# Hackerboat_Control_Board.net
KiCad netlist of a schematic drawn in EAGLE
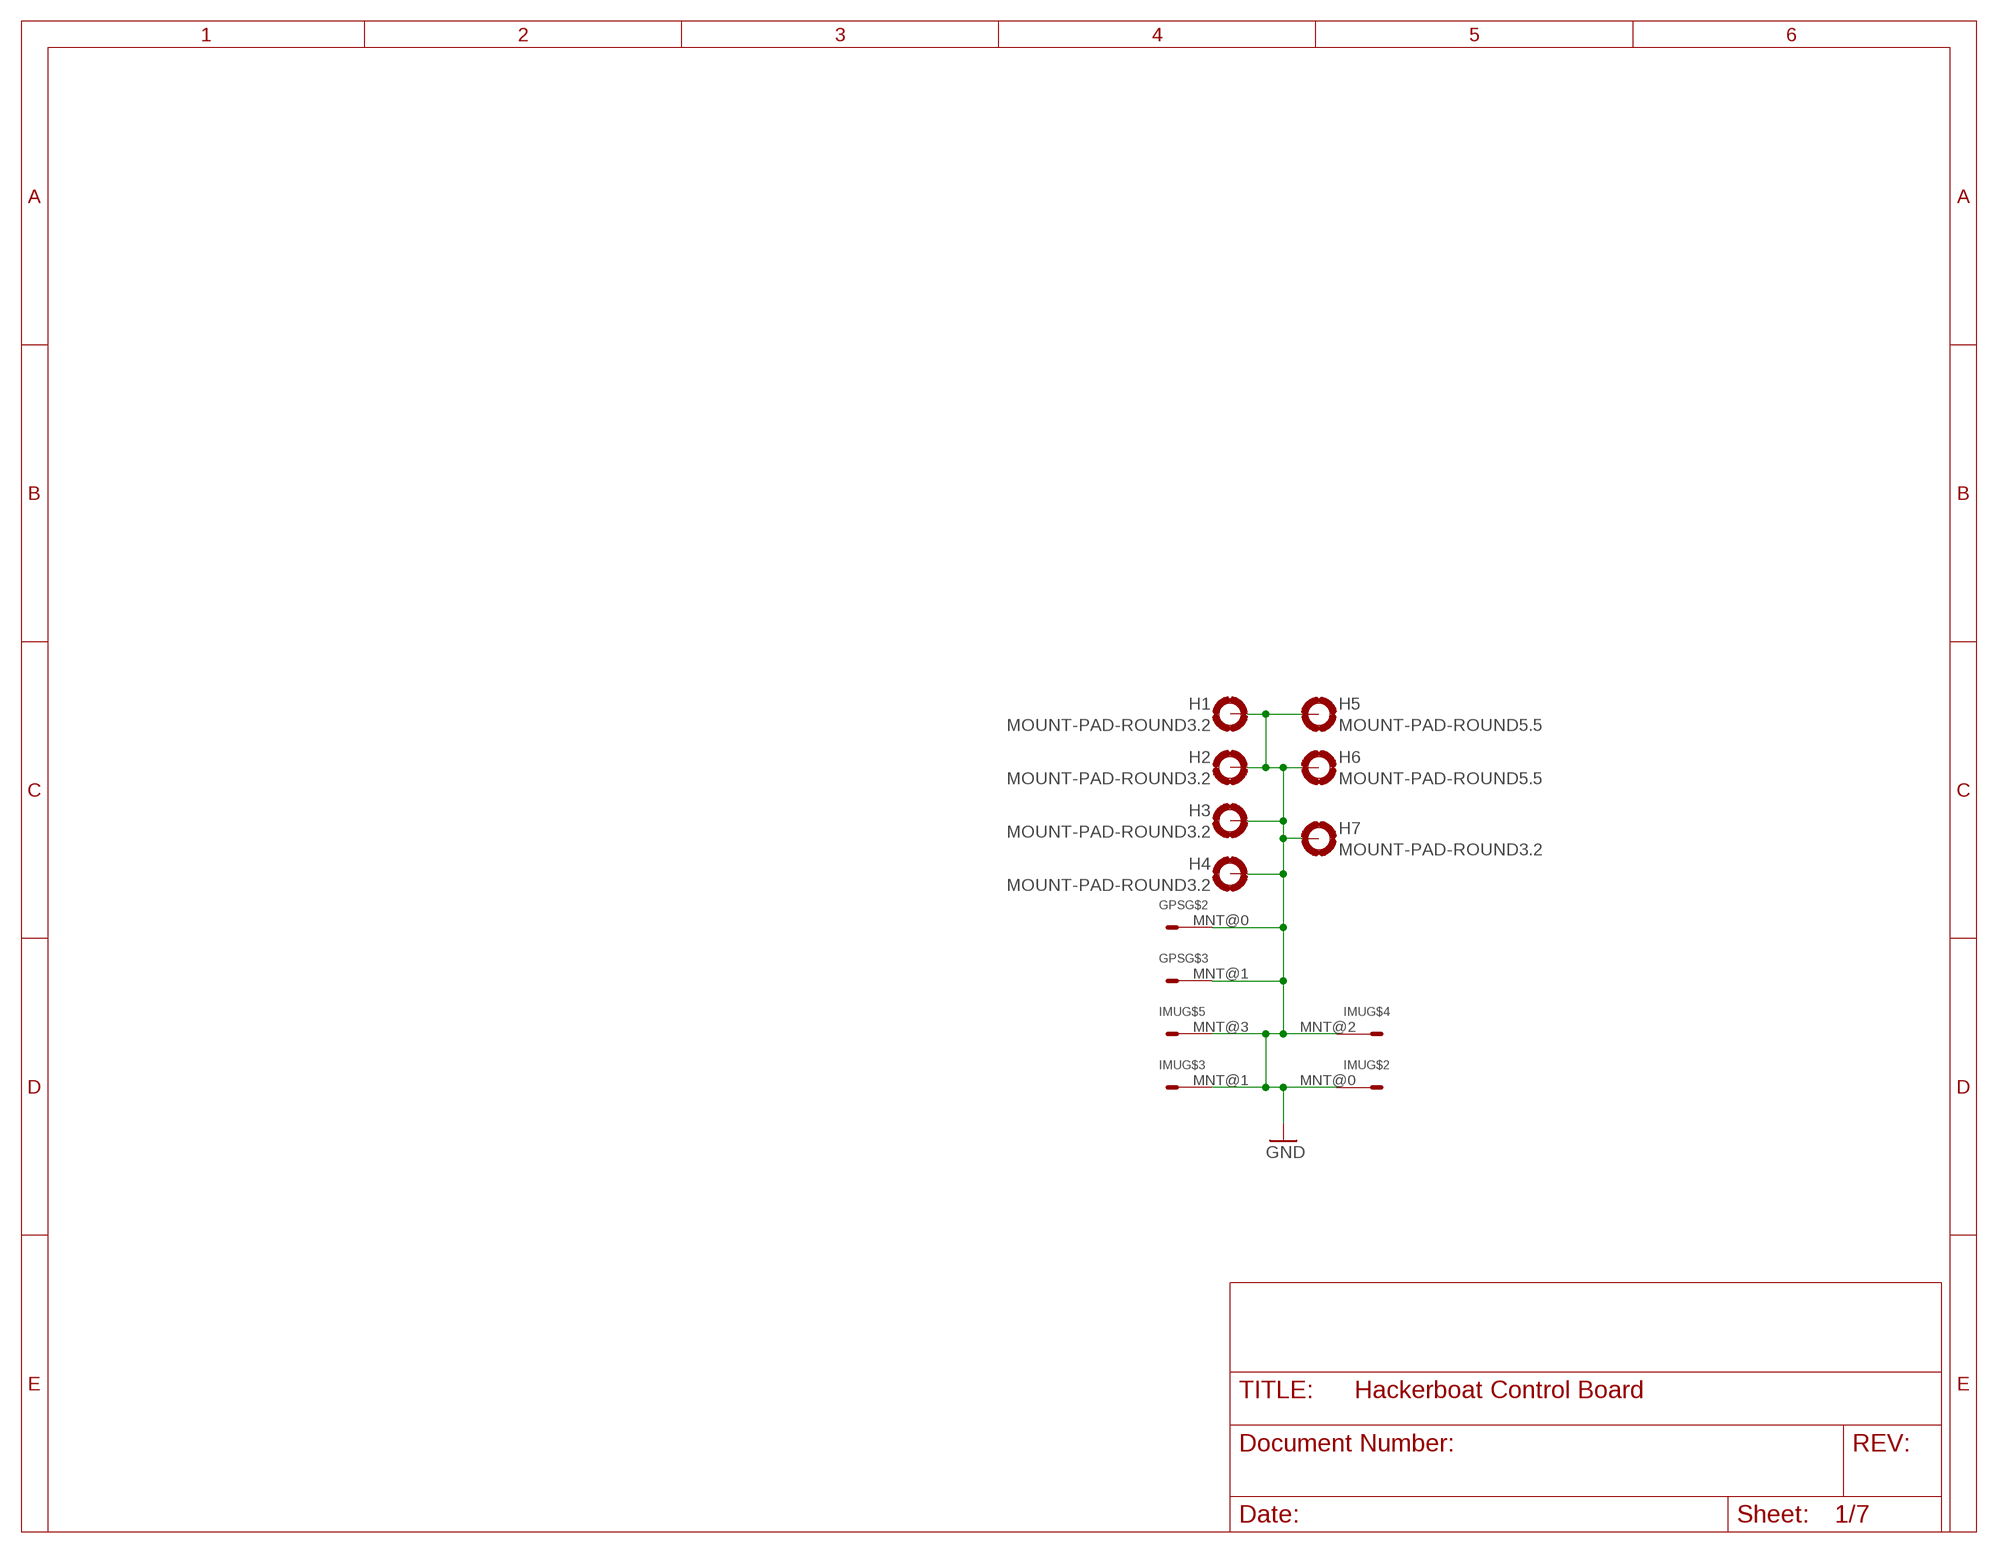
[diagram p0: schematic, sheet 1]
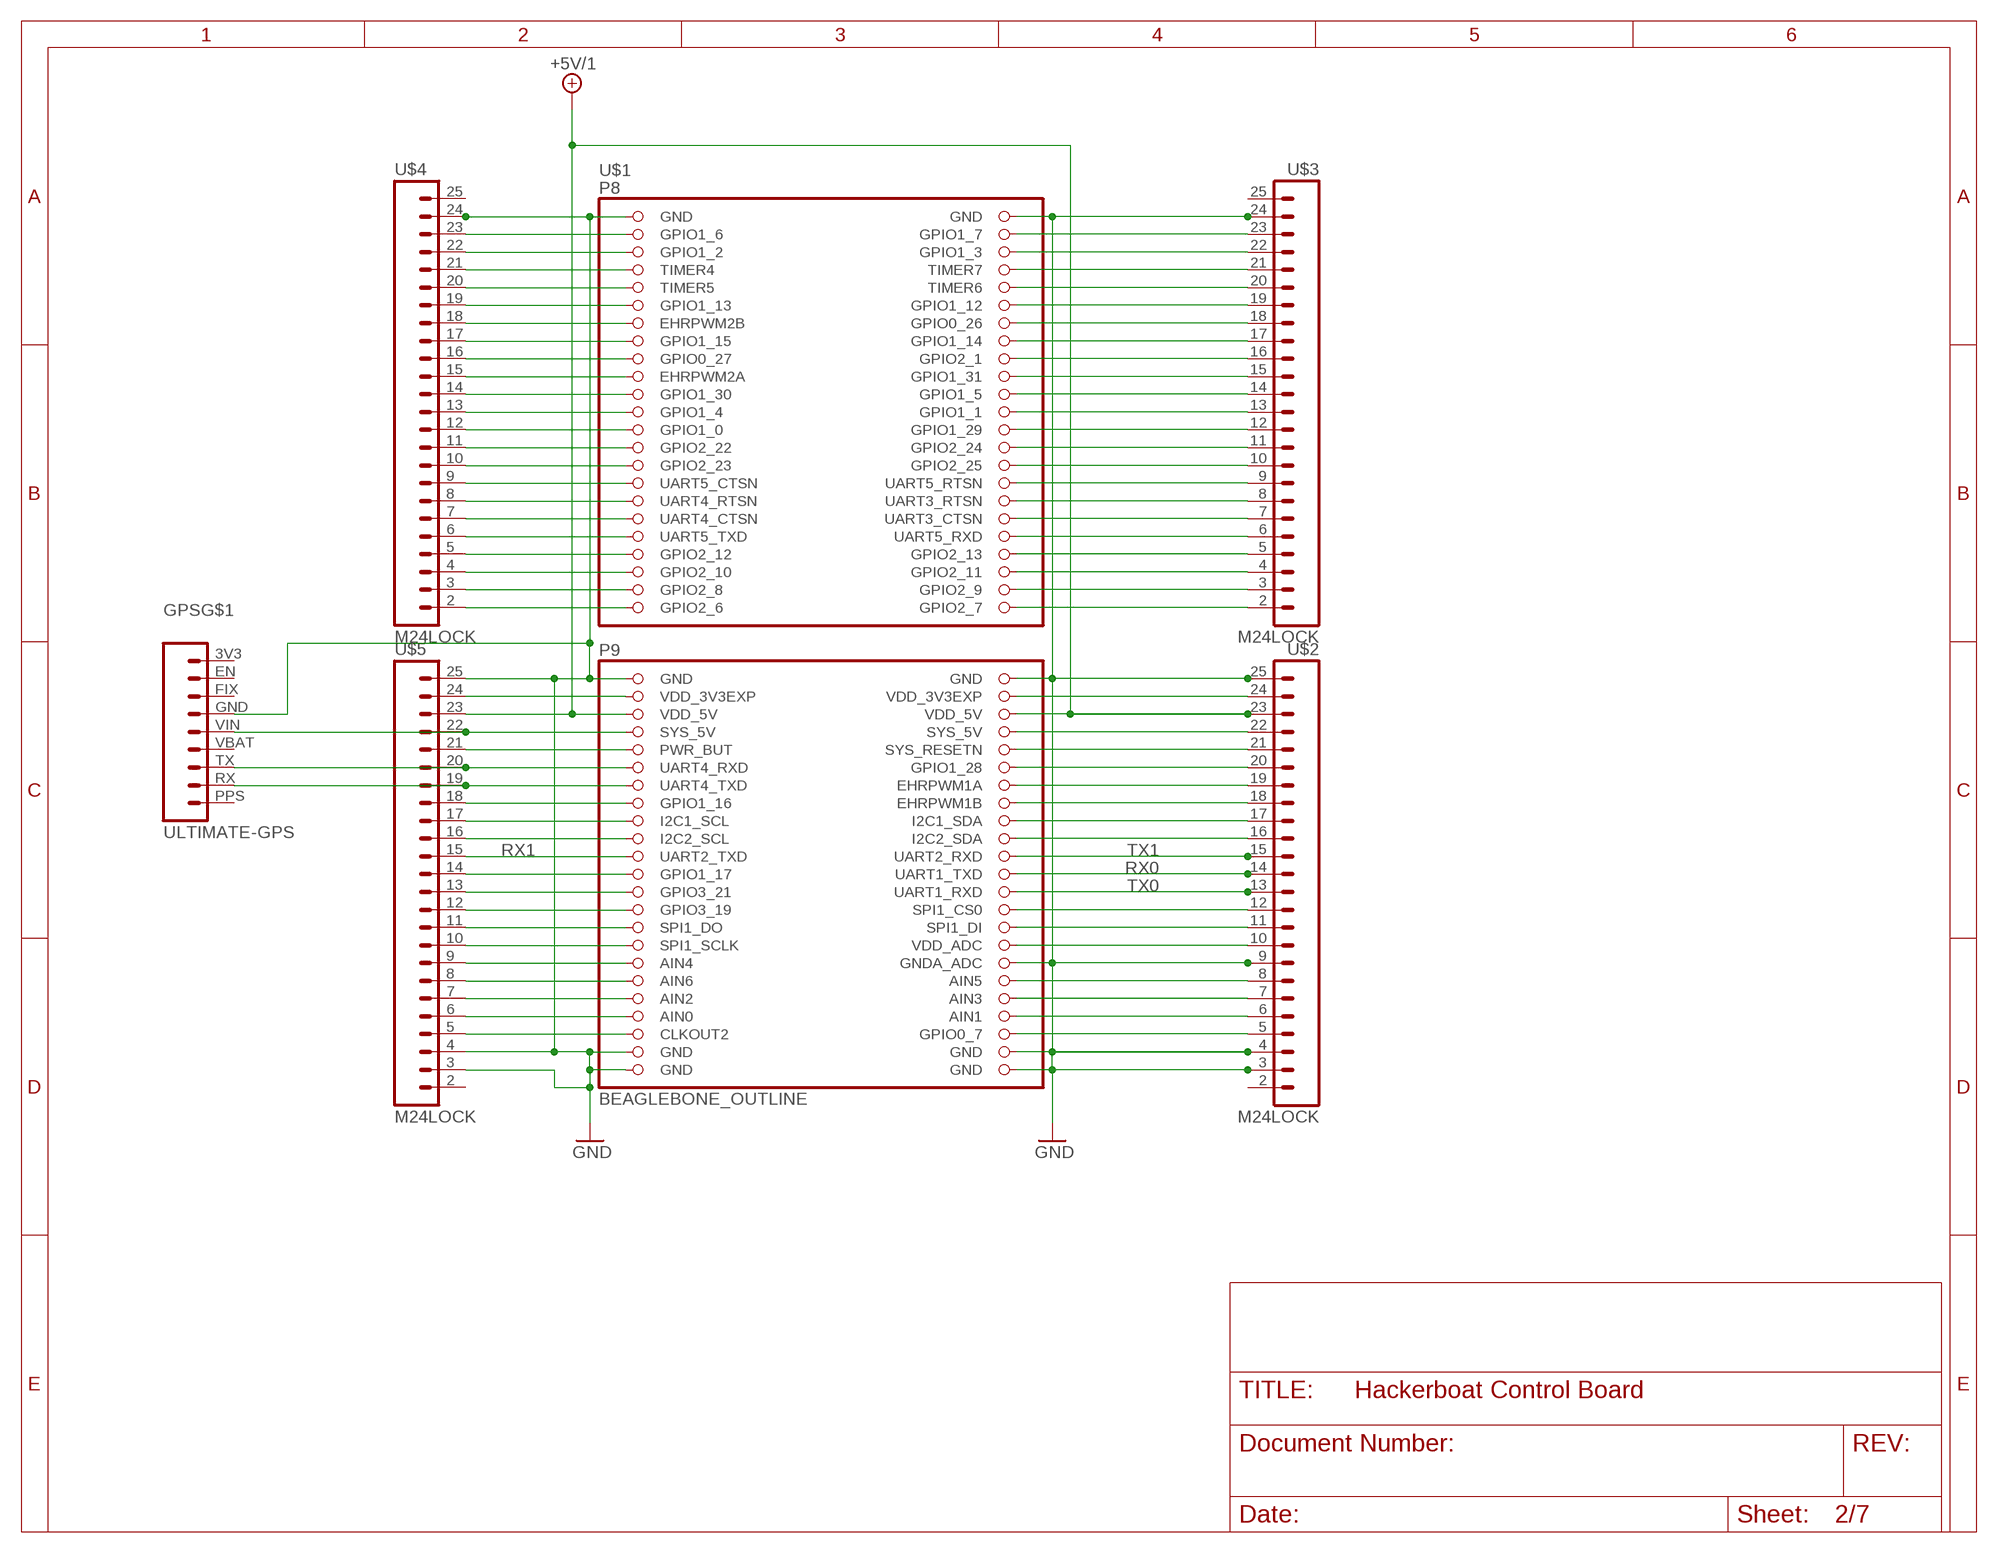
[diagram p1: schematic, sheet 2]
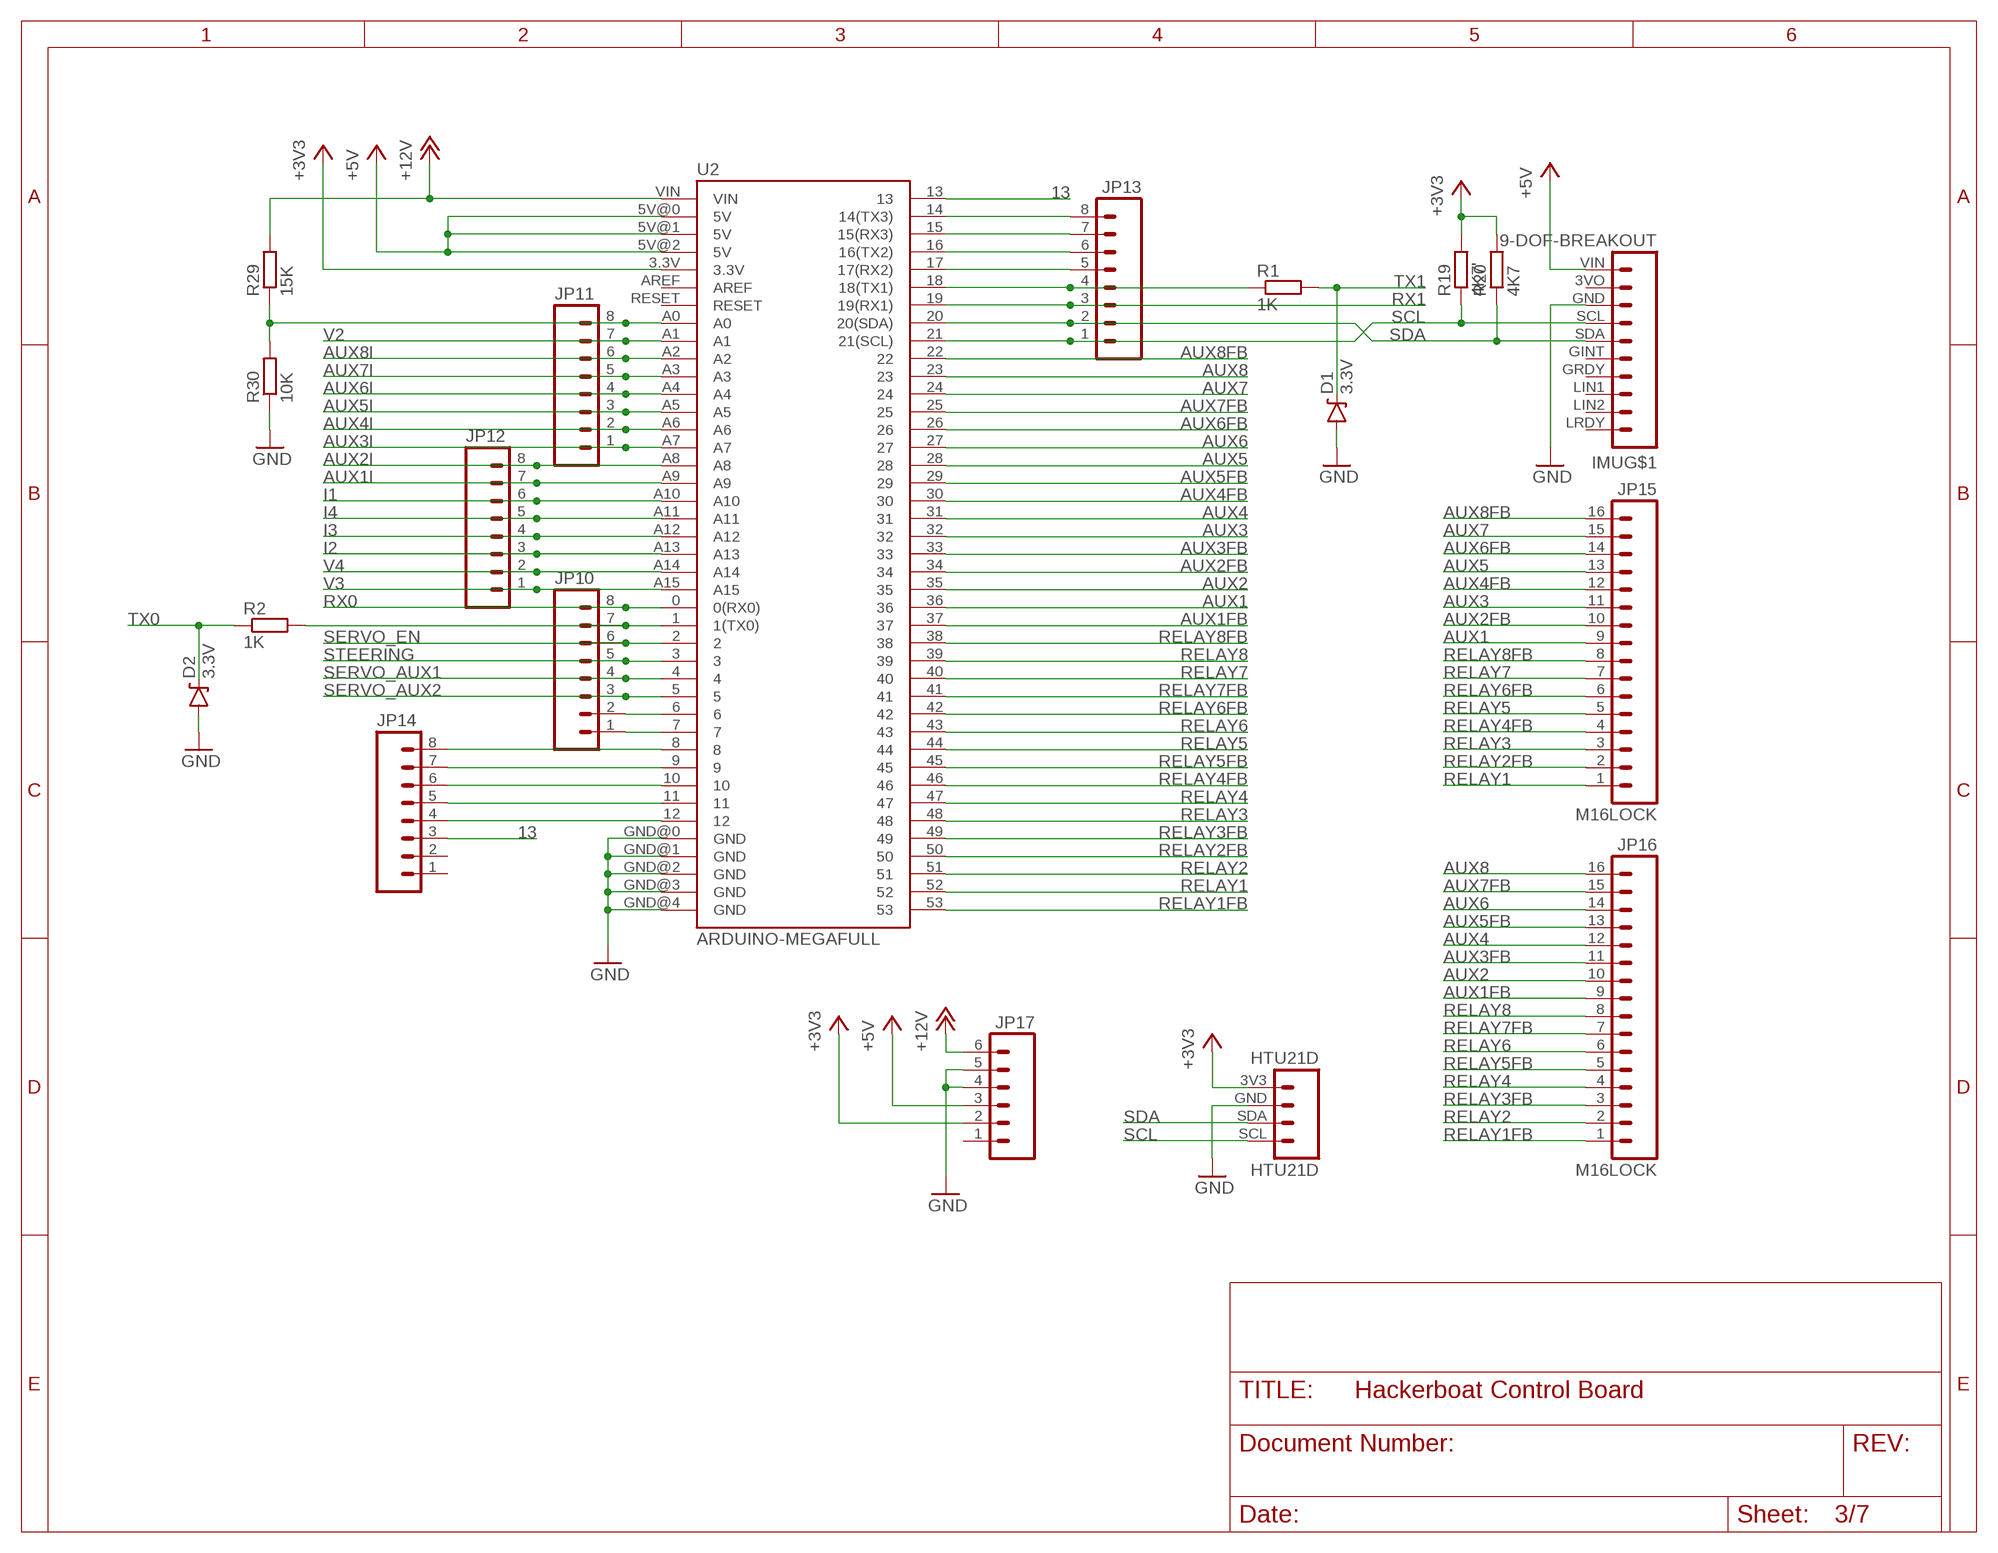
[diagram p2: schematic, sheet 3]
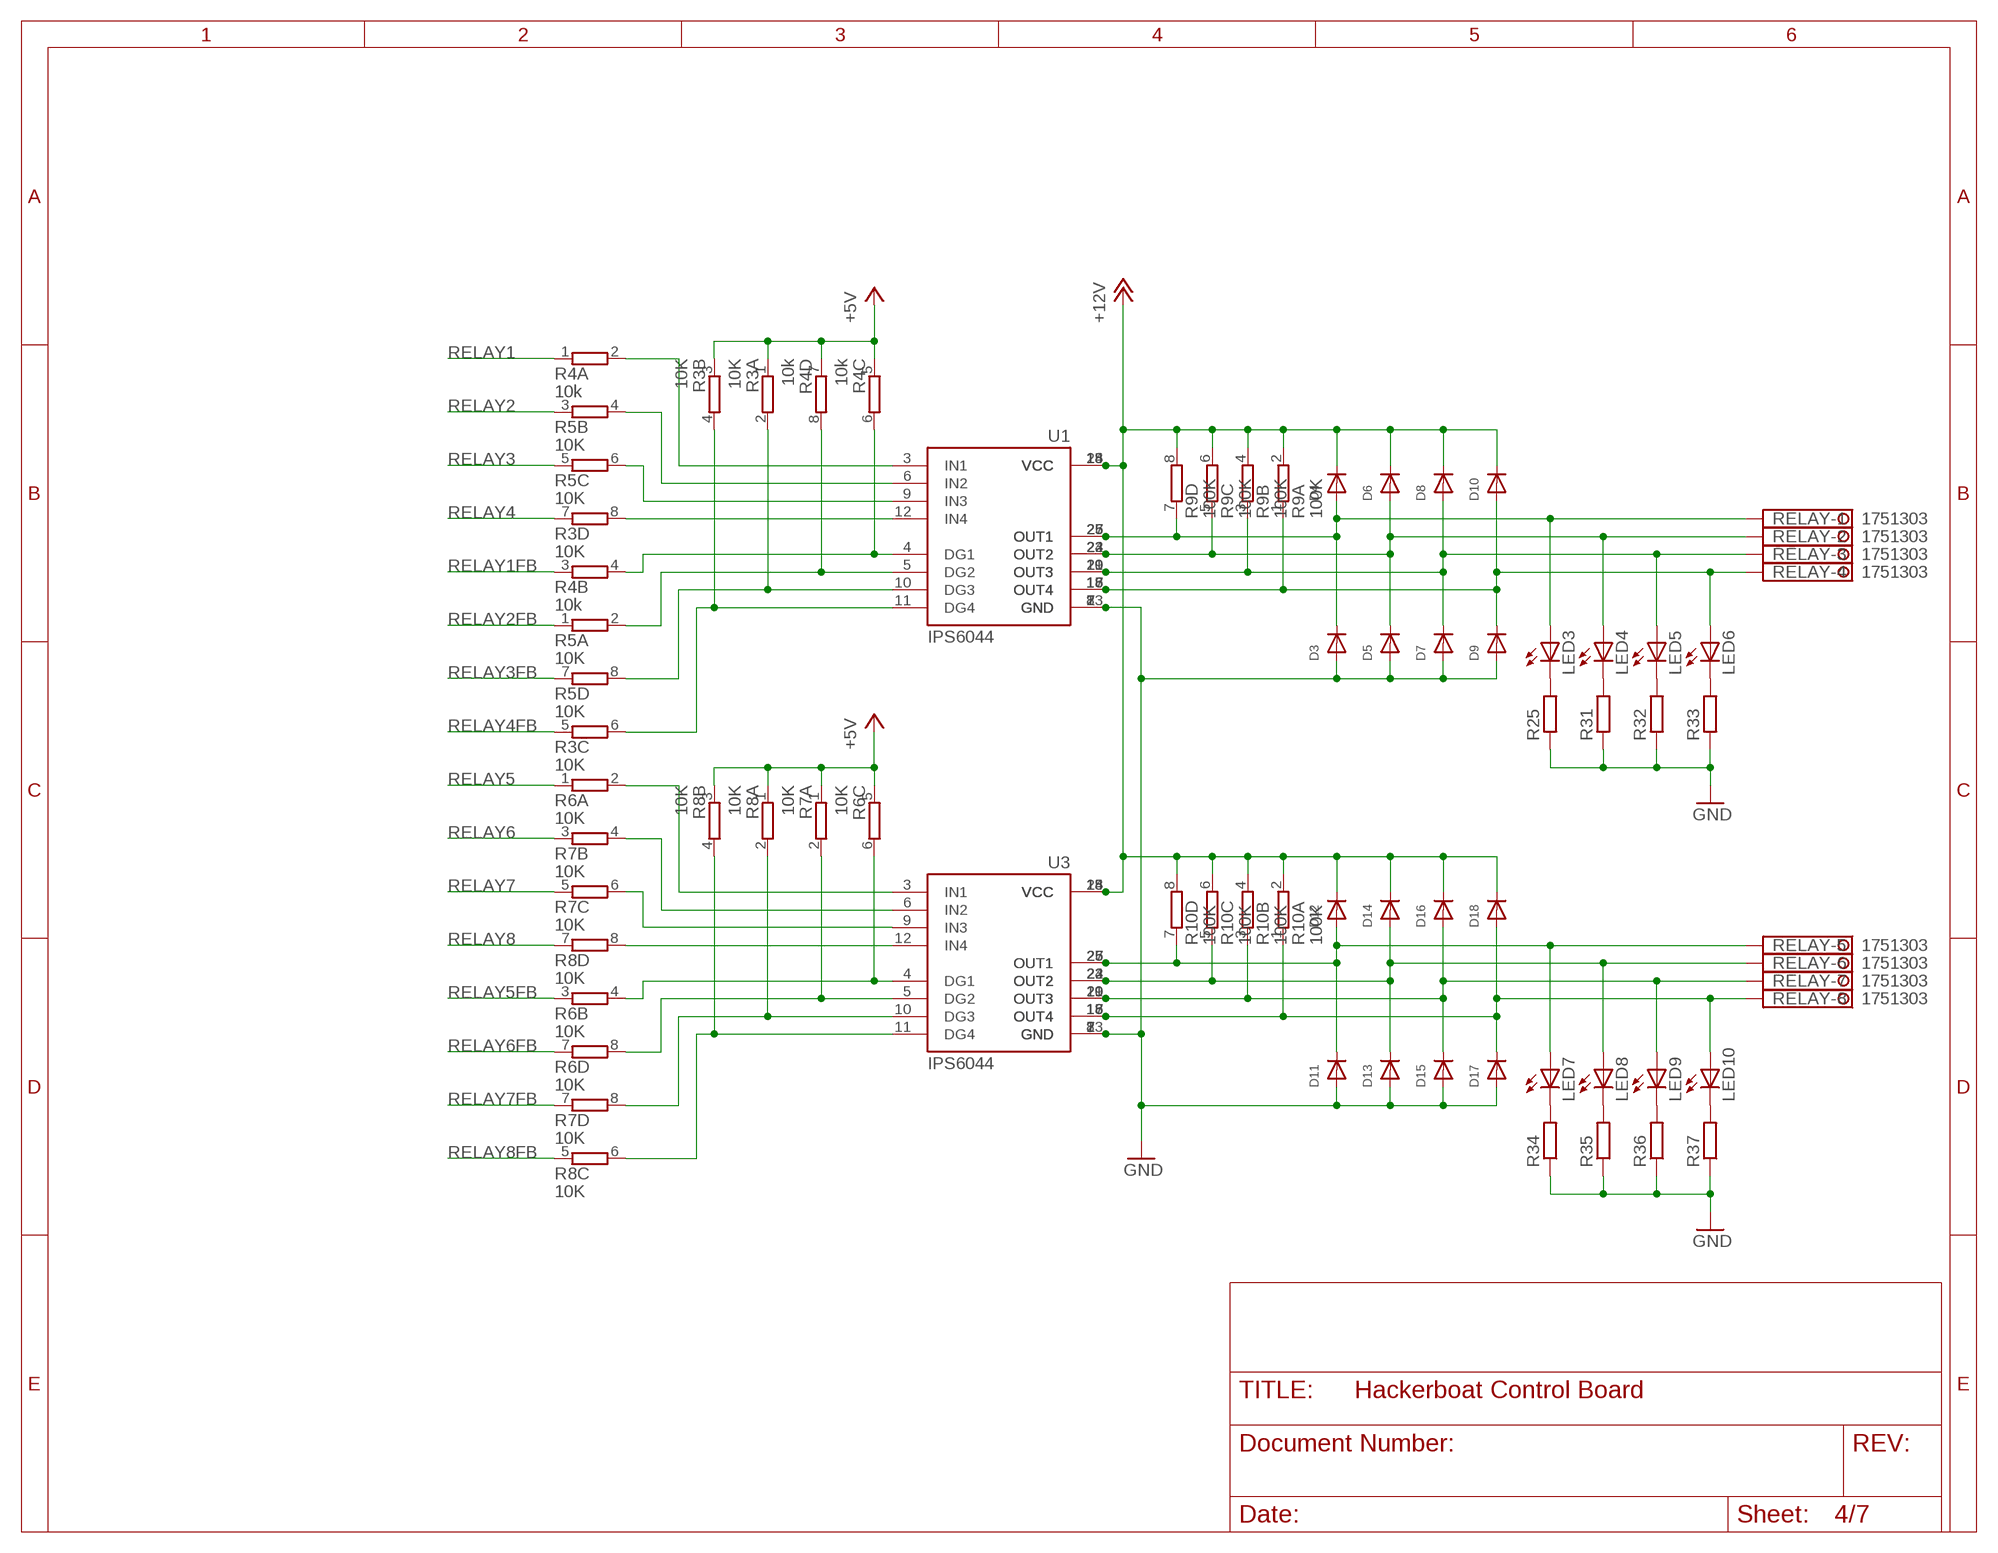
[diagram p3: schematic, sheet 4]
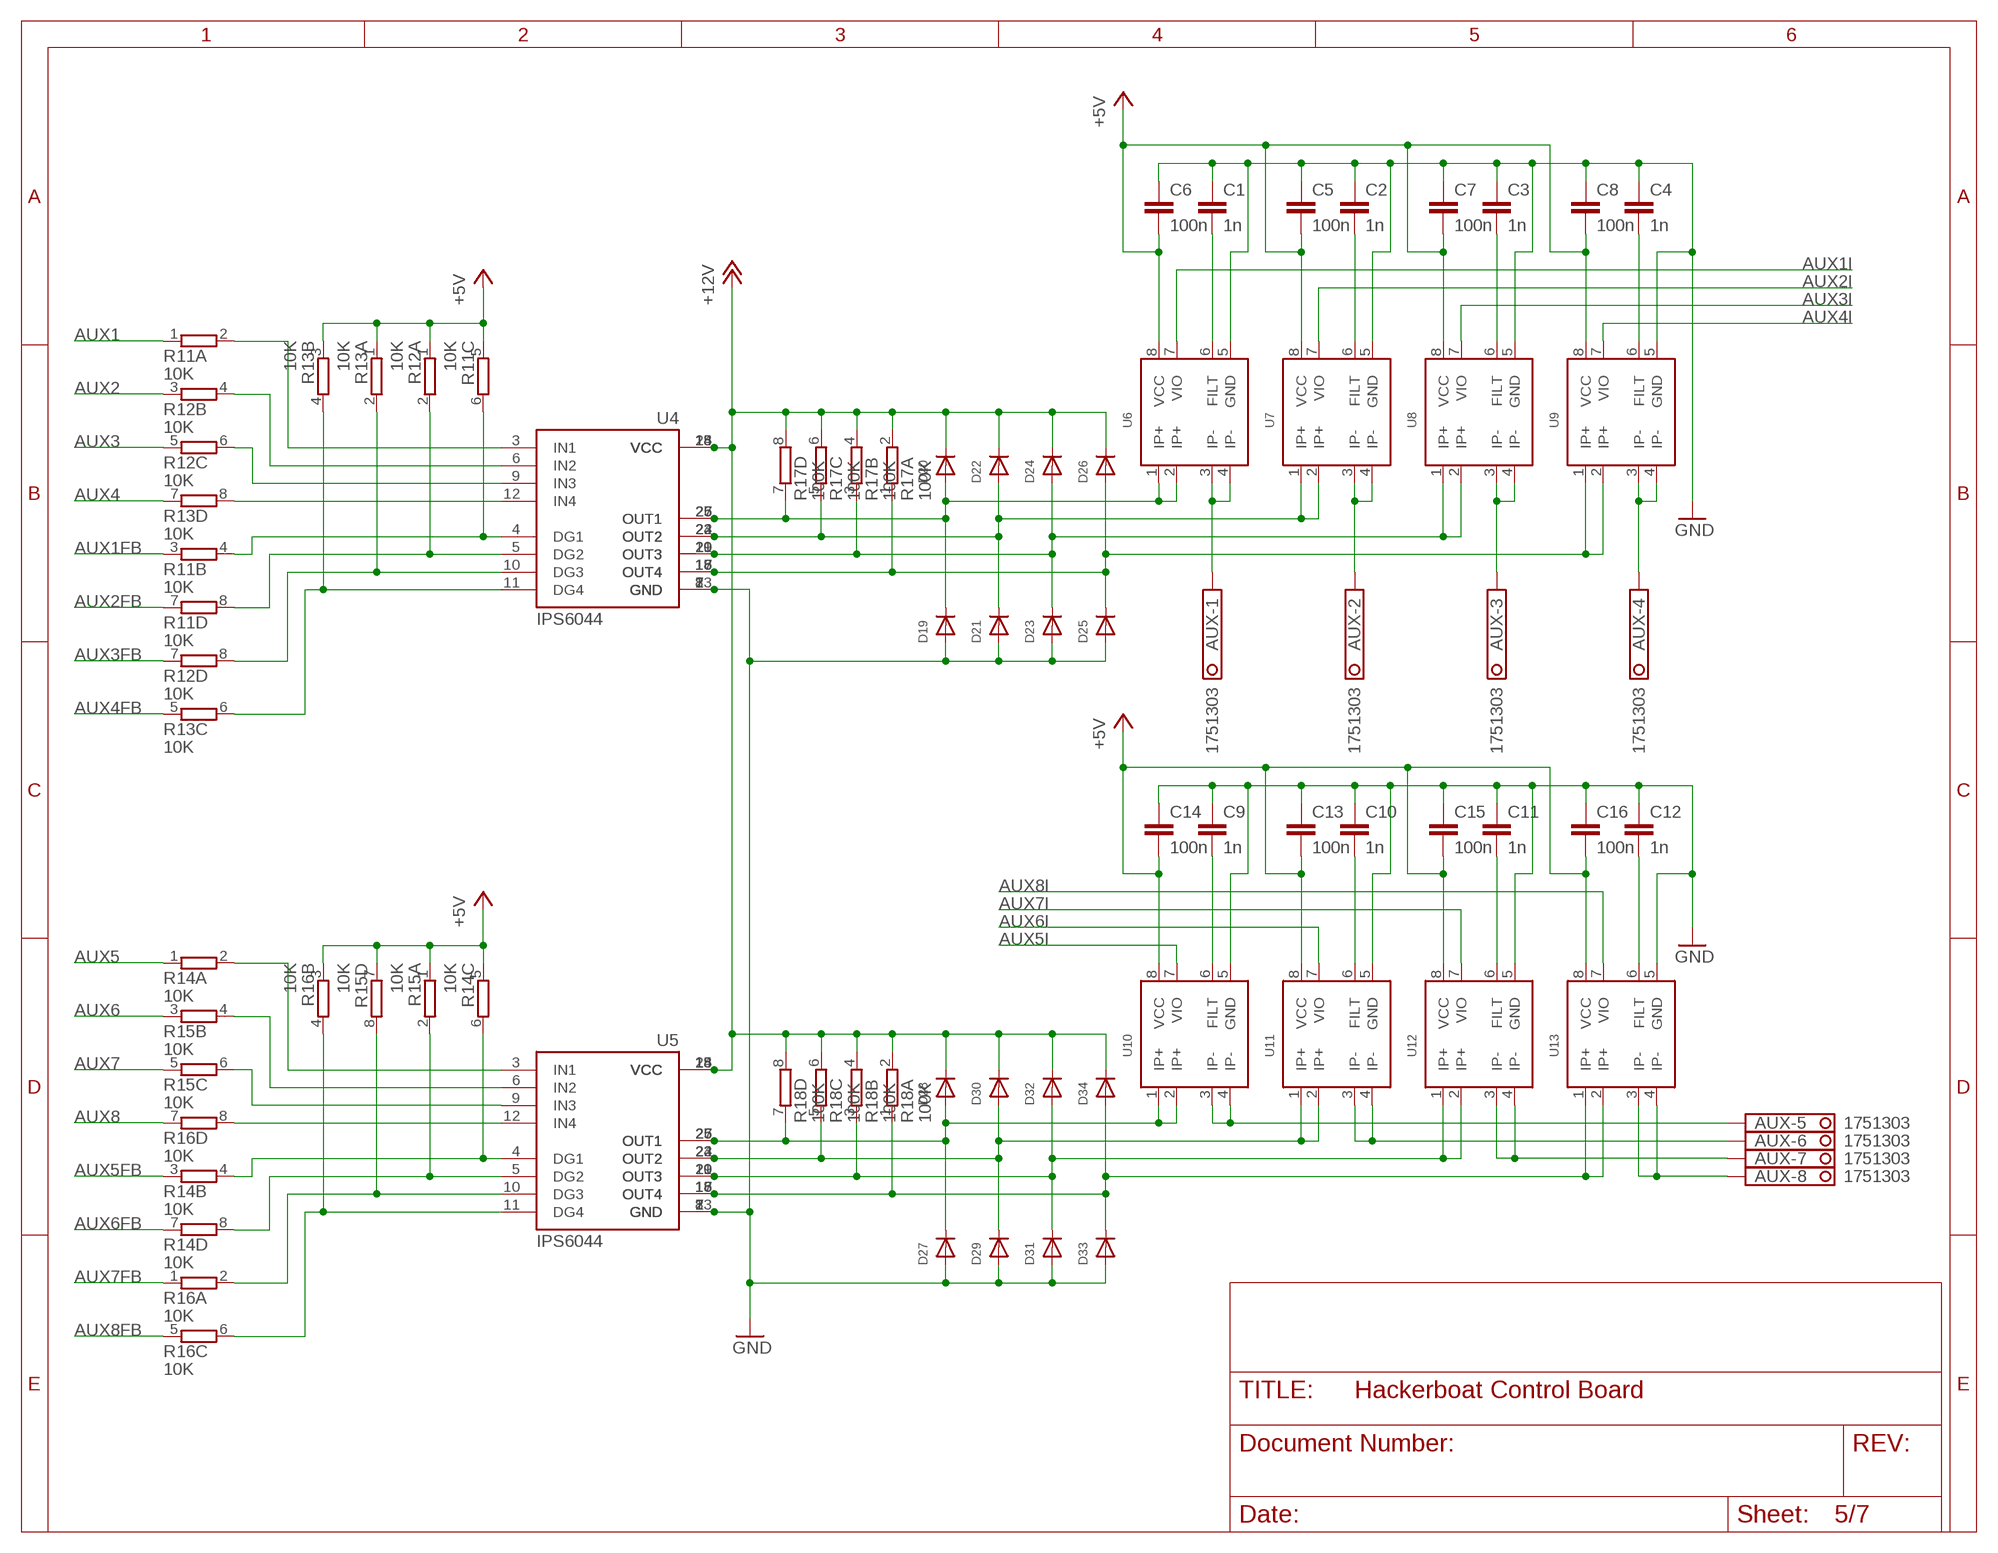
[diagram p4: schematic, sheet 5]
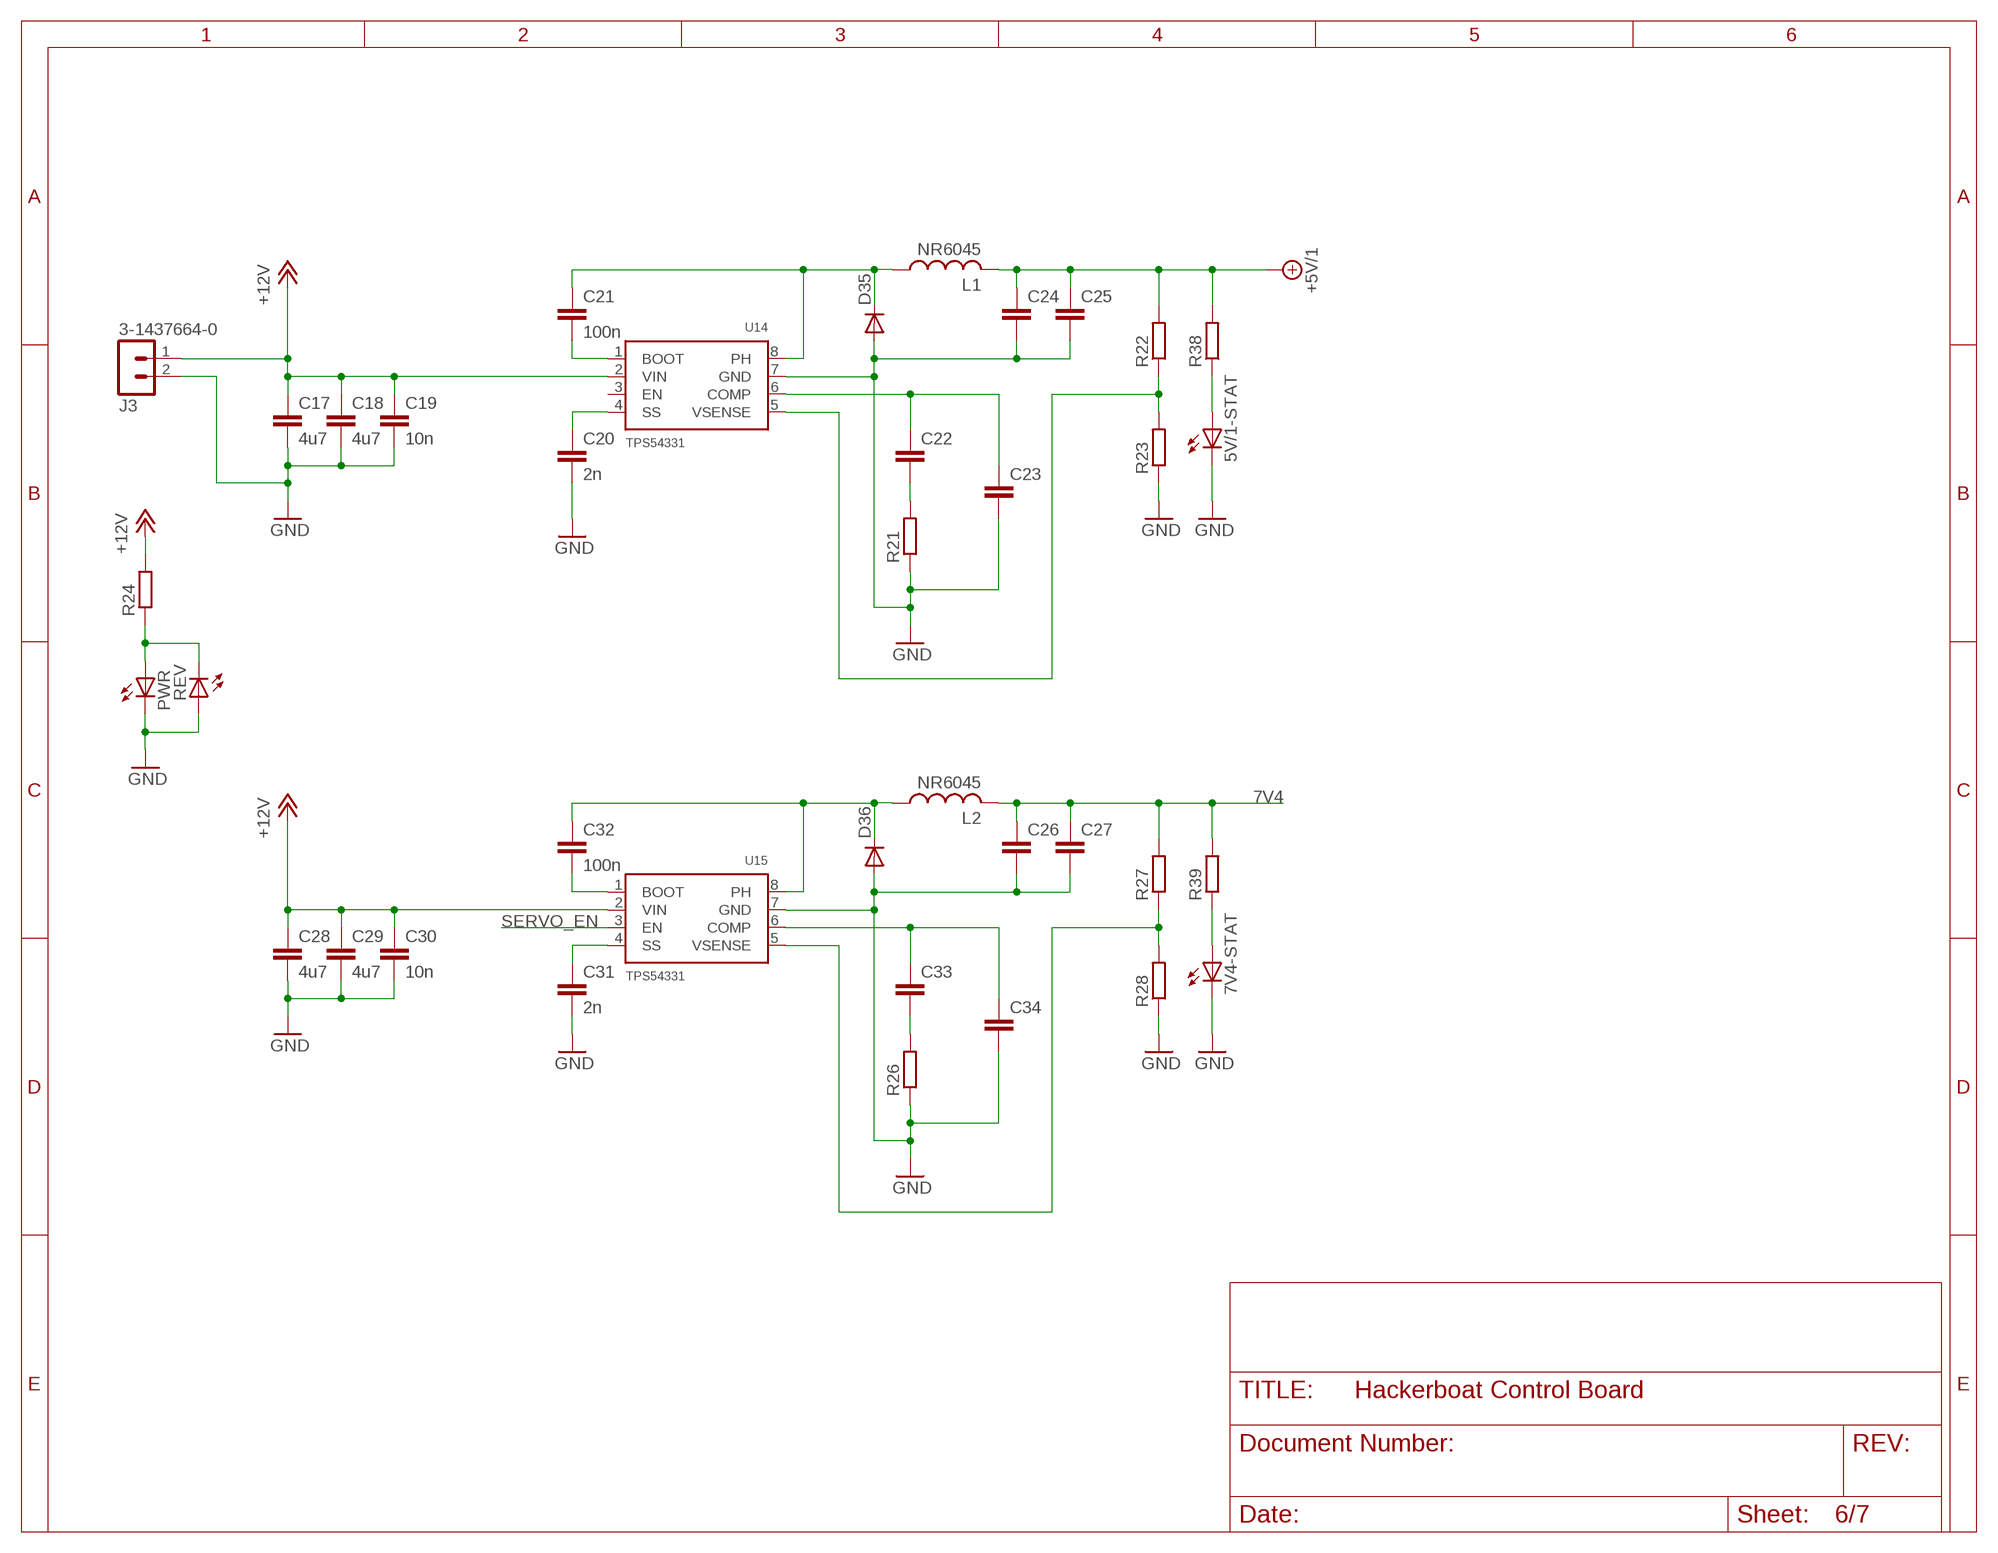
[diagram p5: schematic, sheet 6]
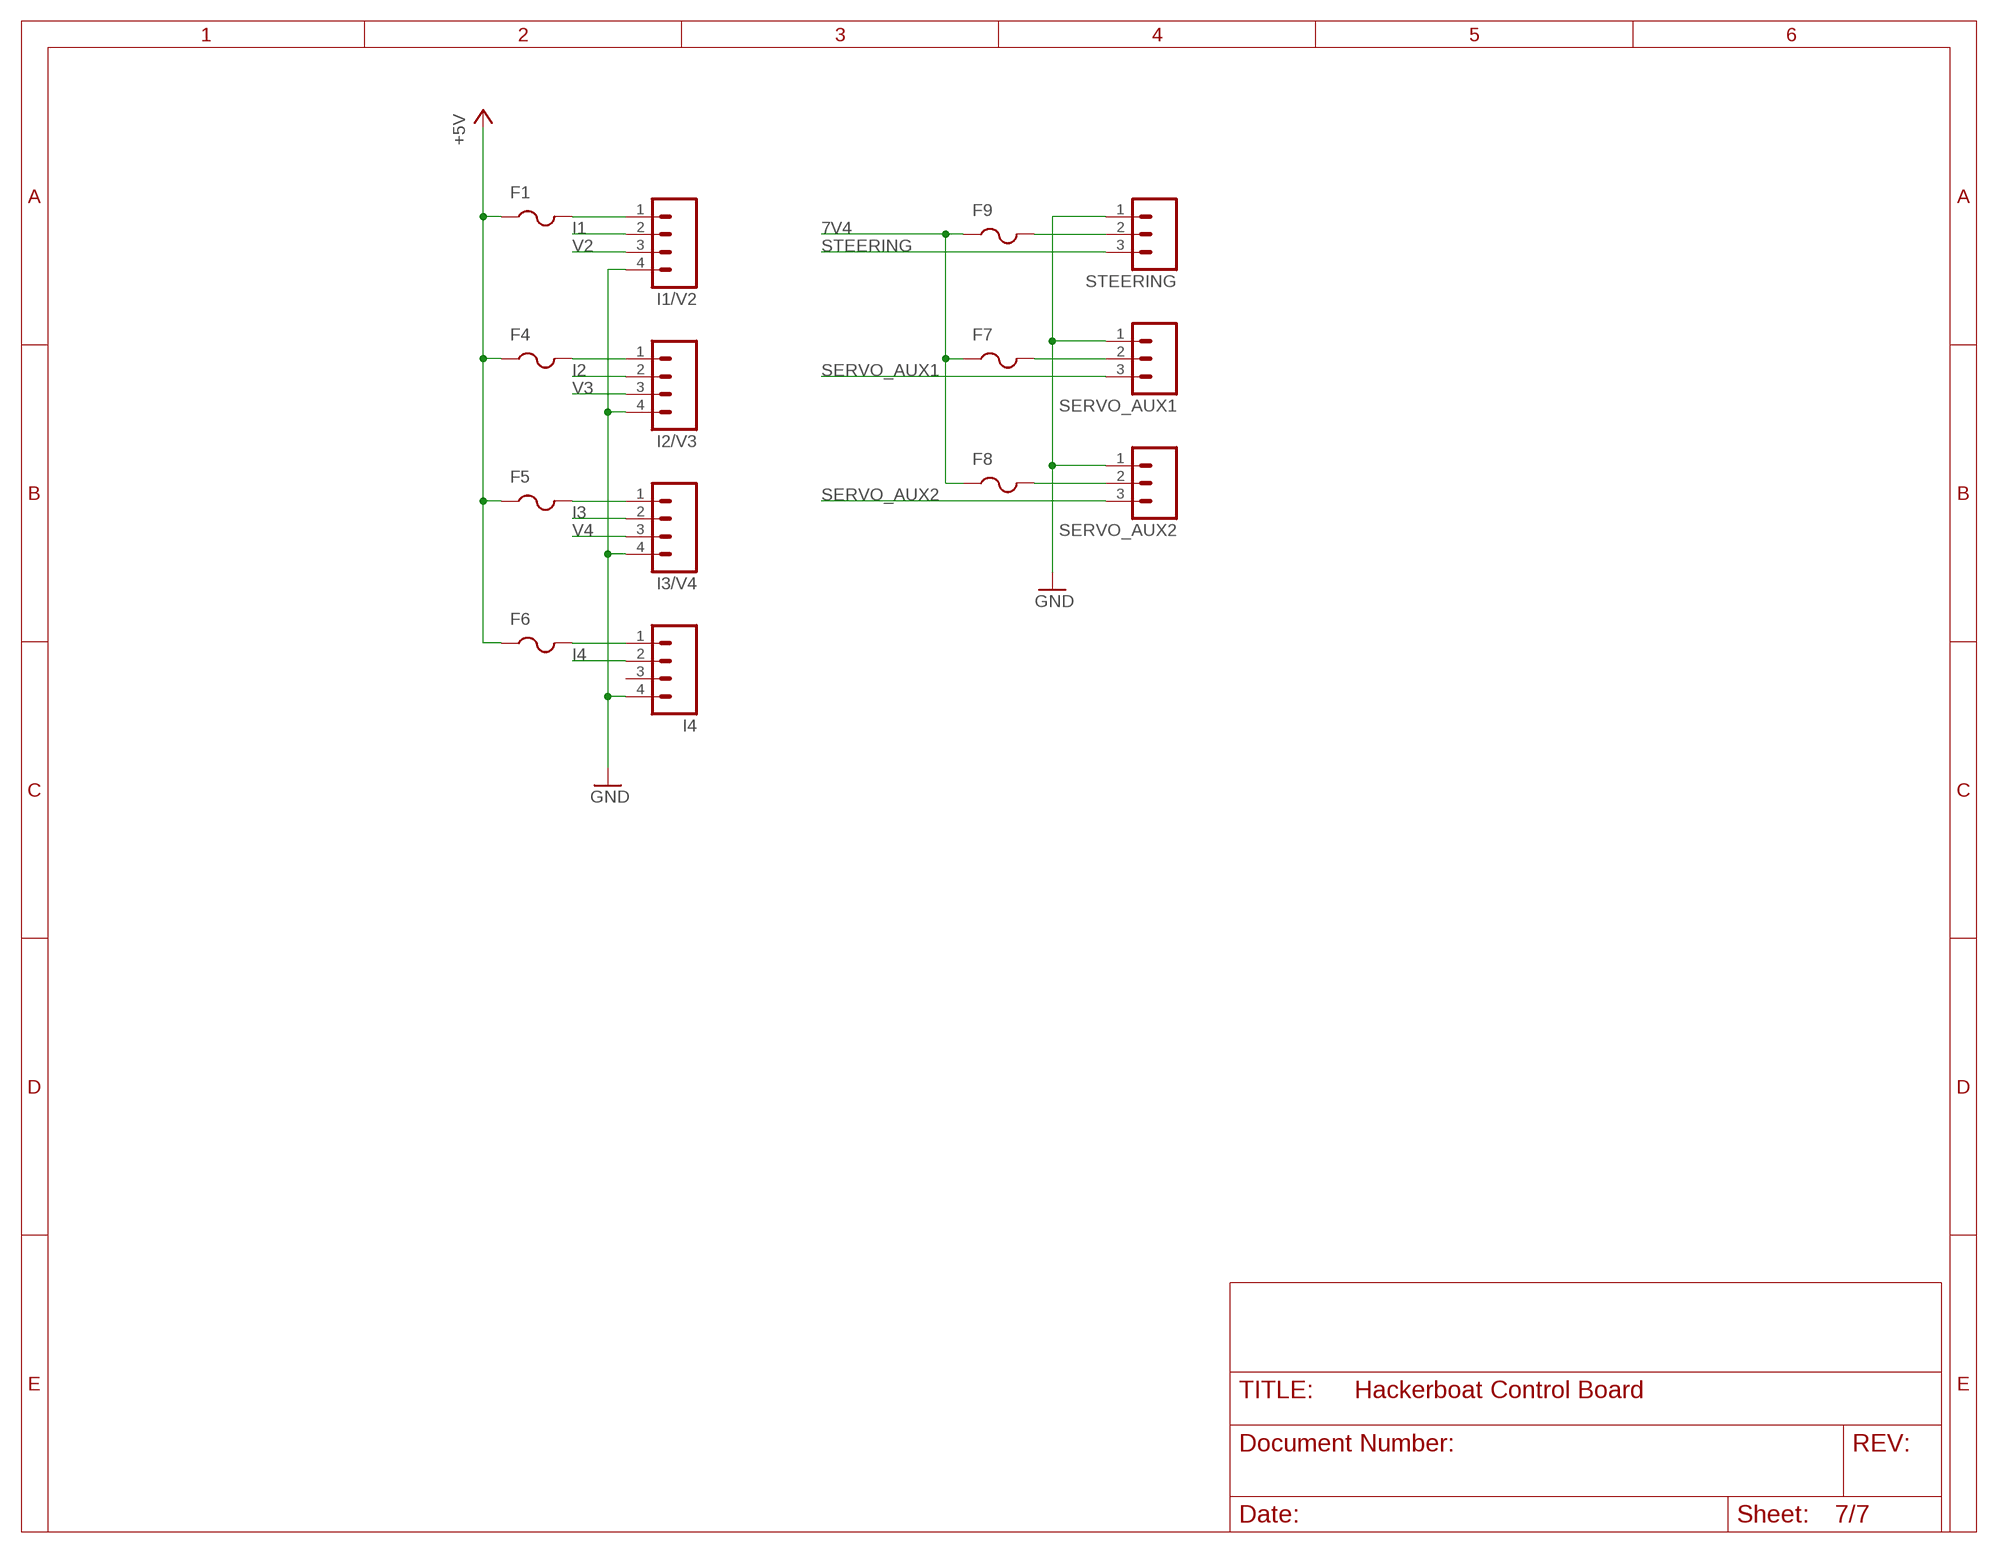
[diagram p6: schematic, sheet 7]

(export (version "E")
  (design (tool "Eeschema 10.0.6"))
  (components
    (comp (ref "F1")
      (value "PTCFUSE-1206")
      (footprint "eagle-import:R1206")
      (libsource (lib "eagle-import") (part "PTCFUSE-1206"))
    )
    (comp (ref "F4")
      (value "PTCFUSE-1206")
      (footprint "eagle-import:R1206")
      (libsource (lib "eagle-import") (part "PTCFUSE-1206"))
    )
    (comp (ref "F5")
      (value "PTCFUSE-1206")
      (footprint "eagle-import:R1206")
      (libsource (lib "eagle-import") (part "PTCFUSE-1206"))
    )
    (comp (ref "F6")
      (value "PTCFUSE-1206")
      (footprint "eagle-import:R1206")
      (libsource (lib "eagle-import") (part "PTCFUSE-1206"))
    )
    (comp (ref "F7")
      (value "PTCFUSE-1206")
      (footprint "eagle-import:R1206")
      (libsource (lib "eagle-import") (part "PTCFUSE-1206"))
    )
    (comp (ref "F8")
      (value "PTCFUSE-1206")
      (footprint "eagle-import:R1206")
      (libsource (lib "eagle-import") (part "PTCFUSE-1206"))
    )
    (comp (ref "F9")
      (value "PTCFUSE-1206")
      (footprint "eagle-import:R1206")
      (libsource (lib "eagle-import") (part "PTCFUSE-1206"))
    )
    (comp (ref "I1/V2")
      (value "M04LOCK_LONGPADS")
      (footprint "eagle-import:1X04_LOCK_LONGPADS")
      (libsource (lib "eagle-import") (part "M04LOCK_LONGPADS"))
    )
    (comp (ref "I2/V3")
      (value "M04LOCK_LONGPADS")
      (footprint "eagle-import:1X04_LOCK_LONGPADS")
      (libsource (lib "eagle-import") (part "M04LOCK_LONGPADS"))
    )
    (comp (ref "I3/V4")
      (value "M04LOCK_LONGPADS")
      (footprint "eagle-import:1X04_LOCK_LONGPADS")
      (libsource (lib "eagle-import") (part "M04LOCK_LONGPADS"))
    )
    (comp (ref "I4")
      (value "M04LOCK_LONGPADS")
      (footprint "eagle-import:1X04_LOCK_LONGPADS")
      (libsource (lib "eagle-import") (part "M04LOCK_LONGPADS"))
    )
    (comp (ref "SERVO_AUX1")
      (value "M03LOCK_LONGPADS")
      (footprint "eagle-import:1X03_LOCK_LONGPADS")
      (libsource (lib "eagle-import") (part "M03LOCK_LONGPADS"))
    )
    (comp (ref "SERVO_AUX2")
      (value "M03LOCK_LONGPADS")
      (footprint "eagle-import:1X03_LOCK_LONGPADS")
      (libsource (lib "eagle-import") (part "M03LOCK_LONGPADS"))
    )
    (comp (ref "STEERING")
      (value "M03LOCK_LONGPADS")
      (footprint "eagle-import:1X03_LOCK_LONGPADS")
      (libsource (lib "eagle-import") (part "M03LOCK_LONGPADS"))
    )
    (comp (ref "5V/1-STAT")
      (value "LEDCHIPLED_0805")
      (footprint "eagle-import:CHIPLED_0805")
      (libsource (lib "eagle-import") (part "LEDCHIPLED_0805"))
    )
    (comp (ref "7V4-STAT")
      (value "LEDCHIPLED_0805")
      (footprint "eagle-import:CHIPLED_0805")
      (libsource (lib "eagle-import") (part "LEDCHIPLED_0805"))
    )
    (comp (ref "C17")
      (value "4u7")
      (footprint "eagle-import:C1210")
      (libsource (lib "eagle-import") (part "C-EUC1210"))
    )
    (comp (ref "C18")
      (value "4u7")
      (footprint "eagle-import:C1210")
      (libsource (lib "eagle-import") (part "C-EUC1210"))
    )
    (comp (ref "C19")
      (value "10n")
      (footprint "eagle-import:C0603")
      (libsource (lib "eagle-import") (part "C-EUC0603"))
    )
    (comp (ref "C20")
      (value "2n")
      (footprint "eagle-import:C0603")
      (libsource (lib "eagle-import") (part "C-EUC0603"))
    )
    (comp (ref "C21")
      (value "100n")
      (footprint "eagle-import:C0603")
      (libsource (lib "eagle-import") (part "C-EUC0603"))
    )
    (comp (ref "C22")
      (value "C-EUC0603")
      (footprint "eagle-import:C0603")
      (libsource (lib "eagle-import") (part "C-EUC0603"))
    )
    (comp (ref "C23")
      (value "C-EUC0603")
      (footprint "eagle-import:C0603")
      (libsource (lib "eagle-import") (part "C-EUC0603"))
    )
    (comp (ref "C24")
      (value "C-EUC1210")
      (footprint "eagle-import:C1210")
      (libsource (lib "eagle-import") (part "C-EUC1210"))
    )
    (comp (ref "C25")
      (value "C-EUC1210")
      (footprint "eagle-import:C1210")
      (libsource (lib "eagle-import") (part "C-EUC1210"))
    )
    (comp (ref "C26")
      (value "C-EUC1210")
      (footprint "eagle-import:C1210")
      (libsource (lib "eagle-import") (part "C-EUC1210"))
    )
    (comp (ref "C27")
      (value "C-EUC1210")
      (footprint "eagle-import:C1210")
      (libsource (lib "eagle-import") (part "C-EUC1210"))
    )
    (comp (ref "C28")
      (value "4u7")
      (footprint "eagle-import:C1210")
      (libsource (lib "eagle-import") (part "C-EUC1210"))
    )
    (comp (ref "C29")
      (value "4u7")
      (footprint "eagle-import:C1210")
      (libsource (lib "eagle-import") (part "C-EUC1210"))
    )
    (comp (ref "C30")
      (value "10n")
      (footprint "eagle-import:C0603")
      (libsource (lib "eagle-import") (part "C-EUC0603"))
    )
    (comp (ref "C31")
      (value "2n")
      (footprint "eagle-import:C0603")
      (libsource (lib "eagle-import") (part "C-EUC0603"))
    )
    (comp (ref "C32")
      (value "100n")
      (footprint "eagle-import:C0603")
      (libsource (lib "eagle-import") (part "C-EUC0603"))
    )
    (comp (ref "C33")
      (value "C-EUC0603")
      (footprint "eagle-import:C0603")
      (libsource (lib "eagle-import") (part "C-EUC0603"))
    )
    (comp (ref "C34")
      (value "C-EUC0603")
      (footprint "eagle-import:C0603")
      (libsource (lib "eagle-import") (part "C-EUC0603"))
    )
    (comp (ref "D35")
      (value "SPARKFUN_DIODESMA")
      (footprint "eagle-import:SPARKFUN_SMA-DIODE")
      (libsource (lib "eagle-import") (part "SPARKFUN_DIODESMA"))
    )
    (comp (ref "D36")
      (value "SPARKFUN_DIODESMA")
      (footprint "eagle-import:SPARKFUN_SMA-DIODE")
      (libsource (lib "eagle-import") (part "SPARKFUN_DIODESMA"))
    )
    (comp (ref "J3")
      (value "3-1437664-0")
      (footprint "eagle-import:CONN-2")
      (libsource (lib "eagle-import") (part "3-1437664-0"))
    )
    (comp (ref "L1")
      (value "NR6045")
      (footprint "eagle-import:NR60XX")
      (libsource (lib "eagle-import") (part "NR6045"))
    )
    (comp (ref "L2")
      (value "NR6045")
      (footprint "eagle-import:NR60XX")
      (libsource (lib "eagle-import") (part "NR6045"))
    )
    (comp (ref "PWR")
      (value "LEDCHIPLED_0805")
      (footprint "eagle-import:CHIPLED_0805")
      (libsource (lib "eagle-import") (part "LEDCHIPLED_0805"))
    )
    (comp (ref "R21")
      (value "R-EU_R0603")
      (footprint "eagle-import:R0603")
      (libsource (lib "eagle-import") (part "R-EU_R0603"))
    )
    (comp (ref "R22")
      (value "R-EU_R0603")
      (footprint "eagle-import:R0603")
      (libsource (lib "eagle-import") (part "R-EU_R0603"))
    )
    (comp (ref "R23")
      (value "R-EU_R0603")
      (footprint "eagle-import:R0603")
      (libsource (lib "eagle-import") (part "R-EU_R0603"))
    )
    (comp (ref "R24")
      (value "R-EU_R0603")
      (footprint "eagle-import:R0603")
      (libsource (lib "eagle-import") (part "R-EU_R0603"))
    )
    (comp (ref "R26")
      (value "R-EU_R0603")
      (footprint "eagle-import:R0603")
      (libsource (lib "eagle-import") (part "R-EU_R0603"))
    )
    (comp (ref "R27")
      (value "R-EU_R0603")
      (footprint "eagle-import:R0603")
      (libsource (lib "eagle-import") (part "R-EU_R0603"))
    )
    (comp (ref "R28")
      (value "R-EU_R0603")
      (footprint "eagle-import:R0603")
      (libsource (lib "eagle-import") (part "R-EU_R0603"))
    )
    (comp (ref "R38")
      (value "R-EU_R0603")
      (footprint "eagle-import:R0603")
      (libsource (lib "eagle-import") (part "R-EU_R0603"))
    )
    (comp (ref "R39")
      (value "R-EU_R0603")
      (footprint "eagle-import:R0603")
      (libsource (lib "eagle-import") (part "R-EU_R0603"))
    )
    (comp (ref "REV")
      (value "LEDCHIPLED_0805")
      (footprint "eagle-import:CHIPLED_0805")
      (libsource (lib "eagle-import") (part "LEDCHIPLED_0805"))
    )
    (comp (ref "U14")
      (value "TPS54331")
      (footprint "eagle-import:SO08")
      (libsource (lib "eagle-import") (part "TPS54331"))
    )
    (comp (ref "U15")
      (value "TPS54331")
      (footprint "eagle-import:SO08")
      (libsource (lib "eagle-import") (part "TPS54331"))
    )
    (comp (ref "D1")
      (value "3.3V")
      (footprint "eagle-import:SOD-323")
      (libsource (lib "eagle-import") (part "DIODE-ZENER3.3V"))
    )
    (comp (ref "D2")
      (value "3.3V")
      (footprint "eagle-import:SOD-323")
      (libsource (lib "eagle-import") (part "DIODE-ZENER3.3V"))
    )
    (comp (ref "HTU21D")
      (value "HTU21D")
      (footprint "eagle-import:HTU21D")
      (libsource (lib "eagle-import") (part "HTU21D"))
    )
    (comp (ref "IMU")
      (value "9-DOF-BREAKOUT")
      (footprint "eagle-import:9-DOF-BREAKOUT")
      (libsource (lib "eagle-import") (part "9-DOF-BREAKOUT"))
    )
    (comp (ref "JP10")
      (value "M08LOCK")
      (footprint "eagle-import:1X08_LOCK")
      (libsource (lib "eagle-import") (part "M08LOCK"))
    )
    (comp (ref "JP11")
      (value "M08LOCK")
      (footprint "eagle-import:1X08_LOCK")
      (libsource (lib "eagle-import") (part "M08LOCK"))
    )
    (comp (ref "JP12")
      (value "M08LOCK")
      (footprint "eagle-import:1X08_LOCK")
      (libsource (lib "eagle-import") (part "M08LOCK"))
    )
    (comp (ref "JP13")
      (value "M08LOCK")
      (footprint "eagle-import:1X08_LOCK")
      (libsource (lib "eagle-import") (part "M08LOCK"))
    )
    (comp (ref "JP14")
      (value "M08LOCK")
      (footprint "eagle-import:1X08_LOCK")
      (libsource (lib "eagle-import") (part "M08LOCK"))
    )
    (comp (ref "JP15")
      (value "M16LOCK")
      (footprint "eagle-import:1X16_LOCK")
      (libsource (lib "eagle-import") (part "M16LOCK"))
    )
    (comp (ref "JP16")
      (value "M16LOCK")
      (footprint "eagle-import:1X16_LOCK")
      (libsource (lib "eagle-import") (part "M16LOCK"))
    )
    (comp (ref "JP17")
      (value "M06LOCK")
      (footprint "eagle-import:1X06_LOCK")
      (libsource (lib "eagle-import") (part "M06LOCK"))
    )
    (comp (ref "R1")
      (value "1K")
      (footprint "eagle-import:R0603")
      (libsource (lib "eagle-import") (part "R-EU_R0603"))
    )
    (comp (ref "R2")
      (value "1K")
      (footprint "eagle-import:R0603")
      (libsource (lib "eagle-import") (part "R-EU_R0603"))
    )
    (comp (ref "R19")
      (value "4K7'")
      (footprint "eagle-import:R0603")
      (libsource (lib "eagle-import") (part "R-EU_R0603"))
    )
    (comp (ref "R20")
      (value "4K7")
      (footprint "eagle-import:R0603")
      (libsource (lib "eagle-import") (part "R-EU_R0603"))
    )
    (comp (ref "R29")
      (value "15K")
      (footprint "eagle-import:R0603")
      (libsource (lib "eagle-import") (part "R-EU_R0603"))
    )
    (comp (ref "R30")
      (value "10K")
      (footprint "eagle-import:R0603")
      (libsource (lib "eagle-import") (part "R-EU_R0603"))
    )
    (comp (ref "U2")
      (value "ARDUINO-MEGAFULL")
      (footprint "eagle-import:ARDUINO_MEGA")
      (libsource (lib "eagle-import") (part "ARDUINO-MEGAFULL"))
    )
    (comp (ref "D3")
      (value "DIODESOD-123")
      (footprint "eagle-import:SOD-123")
      (libsource (lib "eagle-import") (part "DIODESOD-123"))
    )
    (comp (ref "D4")
      (value "DIODESOD-123")
      (footprint "eagle-import:SOD-123")
      (libsource (lib "eagle-import") (part "DIODESOD-123"))
    )
    (comp (ref "D5")
      (value "DIODESOD-123")
      (footprint "eagle-import:SOD-123")
      (libsource (lib "eagle-import") (part "DIODESOD-123"))
    )
    (comp (ref "D6")
      (value "DIODESOD-123")
      (footprint "eagle-import:SOD-123")
      (libsource (lib "eagle-import") (part "DIODESOD-123"))
    )
    (comp (ref "D7")
      (value "DIODESOD-123")
      (footprint "eagle-import:SOD-123")
      (libsource (lib "eagle-import") (part "DIODESOD-123"))
    )
    (comp (ref "D8")
      (value "DIODESOD-123")
      (footprint "eagle-import:SOD-123")
      (libsource (lib "eagle-import") (part "DIODESOD-123"))
    )
    (comp (ref "D9")
      (value "DIODESOD-123")
      (footprint "eagle-import:SOD-123")
      (libsource (lib "eagle-import") (part "DIODESOD-123"))
    )
    (comp (ref "D10")
      (value "DIODESOD-123")
      (footprint "eagle-import:SOD-123")
      (libsource (lib "eagle-import") (part "DIODESOD-123"))
    )
    (comp (ref "D11")
      (value "DIODESOD-123")
      (footprint "eagle-import:SOD-123")
      (libsource (lib "eagle-import") (part "DIODESOD-123"))
    )
    (comp (ref "D12")
      (value "DIODESOD-123")
      (footprint "eagle-import:SOD-123")
      (libsource (lib "eagle-import") (part "DIODESOD-123"))
    )
    (comp (ref "D13")
      (value "DIODESOD-123")
      (footprint "eagle-import:SOD-123")
      (libsource (lib "eagle-import") (part "DIODESOD-123"))
    )
    (comp (ref "D14")
      (value "DIODESOD-123")
      (footprint "eagle-import:SOD-123")
      (libsource (lib "eagle-import") (part "DIODESOD-123"))
    )
    (comp (ref "D15")
      (value "DIODESOD-123")
      (footprint "eagle-import:SOD-123")
      (libsource (lib "eagle-import") (part "DIODESOD-123"))
    )
    (comp (ref "D16")
      (value "DIODESOD-123")
      (footprint "eagle-import:SOD-123")
      (libsource (lib "eagle-import") (part "DIODESOD-123"))
    )
    (comp (ref "D17")
      (value "DIODESOD-123")
      (footprint "eagle-import:SOD-123")
      (libsource (lib "eagle-import") (part "DIODESOD-123"))
    )
    (comp (ref "D18")
      (value "DIODESOD-123")
      (footprint "eagle-import:SOD-123")
      (libsource (lib "eagle-import") (part "DIODESOD-123"))
    )
    (comp (ref "LED3")
      (value "LEDCHIPLED_0805")
      (footprint "eagle-import:CHIPLED_0805")
      (libsource (lib "eagle-import") (part "LEDCHIPLED_0805"))
    )
    (comp (ref "LED4")
      (value "LEDCHIPLED_0805")
      (footprint "eagle-import:CHIPLED_0805")
      (libsource (lib "eagle-import") (part "LEDCHIPLED_0805"))
    )
    (comp (ref "LED5")
      (value "LEDCHIPLED_0805")
      (footprint "eagle-import:CHIPLED_0805")
      (libsource (lib "eagle-import") (part "LEDCHIPLED_0805"))
    )
    (comp (ref "LED6")
      (value "LEDCHIPLED_0805")
      (footprint "eagle-import:CHIPLED_0805")
      (libsource (lib "eagle-import") (part "LEDCHIPLED_0805"))
    )
    (comp (ref "LED7")
      (value "LEDCHIPLED_0805")
      (footprint "eagle-import:CHIPLED_0805")
      (libsource (lib "eagle-import") (part "LEDCHIPLED_0805"))
    )
    (comp (ref "LED8")
      (value "LEDCHIPLED_0805")
      (footprint "eagle-import:CHIPLED_0805")
      (libsource (lib "eagle-import") (part "LEDCHIPLED_0805"))
    )
    (comp (ref "LED9")
      (value "LEDCHIPLED_0805")
      (footprint "eagle-import:CHIPLED_0805")
      (libsource (lib "eagle-import") (part "LEDCHIPLED_0805"))
    )
    (comp (ref "LED10")
      (value "LEDCHIPLED_0805")
      (footprint "eagle-import:CHIPLED_0805")
      (libsource (lib "eagle-import") (part "LEDCHIPLED_0805"))
    )
    (comp (ref "R3")
      (value "10K")
      (footprint "eagle-import:CTS742C083-RES")
      (libsource (lib "eagle-import") (part "4R-NCTS742C083"))
    )
    (comp (ref "R4")
      (value "10k")
      (footprint "eagle-import:CTS742C083-RES")
      (libsource (lib "eagle-import") (part "4R-NCTS742C083"))
    )
    (comp (ref "R5")
      (value "10K")
      (footprint "eagle-import:CTS742C083-RES")
      (libsource (lib "eagle-import") (part "4R-NCTS742C083"))
    )
    (comp (ref "R6")
      (value "10K")
      (footprint "eagle-import:CTS742C083-RES")
      (libsource (lib "eagle-import") (part "4R-NCTS742C083"))
    )
    (comp (ref "R7")
      (value "10K")
      (footprint "eagle-import:CTS742C083-RES")
      (libsource (lib "eagle-import") (part "4R-NCTS742C083"))
    )
    (comp (ref "R8")
      (value "10K")
      (footprint "eagle-import:CTS742C083-RES")
      (libsource (lib "eagle-import") (part "4R-NCTS742C083"))
    )
    (comp (ref "R9")
      (value "100K")
      (footprint "eagle-import:CTS742C083-RES")
      (libsource (lib "eagle-import") (part "4R-NCTS742C083"))
    )
    (comp (ref "R10")
      (value "100K")
      (footprint "eagle-import:CTS742C083-RES")
      (libsource (lib "eagle-import") (part "4R-NCTS742C083"))
    )
    (comp (ref "R25")
      (value "R-EU_R0603")
      (footprint "eagle-import:R0603")
      (libsource (lib "eagle-import") (part "R-EU_R0603"))
    )
    (comp (ref "R31")
      (value "R-EU_R0603")
      (footprint "eagle-import:R0603")
      (libsource (lib "eagle-import") (part "R-EU_R0603"))
    )
    (comp (ref "R32")
      (value "R-EU_R0603")
      (footprint "eagle-import:R0603")
      (libsource (lib "eagle-import") (part "R-EU_R0603"))
    )
    (comp (ref "R33")
      (value "R-EU_R0603")
      (footprint "eagle-import:R0603")
      (libsource (lib "eagle-import") (part "R-EU_R0603"))
    )
    (comp (ref "R34")
      (value "R-EU_R0603")
      (footprint "eagle-import:R0603")
      (libsource (lib "eagle-import") (part "R-EU_R0603"))
    )
    (comp (ref "R35")
      (value "R-EU_R0603")
      (footprint "eagle-import:R0603")
      (libsource (lib "eagle-import") (part "R-EU_R0603"))
    )
    (comp (ref "R36")
      (value "R-EU_R0603")
      (footprint "eagle-import:R0603")
      (libsource (lib "eagle-import") (part "R-EU_R0603"))
    )
    (comp (ref "R37")
      (value "R-EU_R0603")
      (footprint "eagle-import:R0603")
      (libsource (lib "eagle-import") (part "R-EU_R0603"))
    )
    (comp (ref "RELAY")
      (value "1751303")
      (footprint "eagle-import:1751303")
      (libsource (lib "eagle-import") (part "1751303"))
    )
    (comp (ref "U1")
      (value "IPS6044")
      (footprint "eagle-import:SO-28L")
      (libsource (lib "eagle-import") (part "IPS6044"))
    )
    (comp (ref "U3")
      (value "IPS6044")
      (footprint "eagle-import:SO-28L")
      (libsource (lib "eagle-import") (part "IPS6044"))
    )
    (comp (ref "GPS")
      (value "ULTIMATE-GPS")
      (footprint "eagle-import:ULTIMATE-GPS")
      (libsource (lib "eagle-import") (part "ULTIMATE-GPS"))
    )
    (comp (ref "U$1")
      (value "BEAGLEBONE_OUTLINE")
      (footprint "eagle-import:BEAGLEBONE_SHIELD")
      (libsource (lib "eagle-import") (part "BEAGLEBONE_OUTLINE"))
    )
    (comp (ref "U$2")
      (value "M24LOCK")
      (footprint "eagle-import:1X24_LOCK")
      (libsource (lib "eagle-import") (part "M24LOCK"))
    )
    (comp (ref "U$3")
      (value "M24LOCK")
      (footprint "eagle-import:1X24_LOCK")
      (libsource (lib "eagle-import") (part "M24LOCK"))
    )
    (comp (ref "U$4")
      (value "M24LOCK")
      (footprint "eagle-import:1X24_LOCK")
      (libsource (lib "eagle-import") (part "M24LOCK"))
    )
    (comp (ref "U$5")
      (value "M24LOCK")
      (footprint "eagle-import:1X24_LOCK")
      (libsource (lib "eagle-import") (part "M24LOCK"))
    )
    (comp (ref "H1")
      (value "MOUNT-PAD-ROUND3.2")
      (footprint "eagle-import:3,2-PAD")
      (libsource (lib "eagle-import") (part "MOUNT-PAD-ROUND3.2"))
    )
    (comp (ref "H2")
      (value "MOUNT-PAD-ROUND3.2")
      (footprint "eagle-import:3,2-PAD")
      (libsource (lib "eagle-import") (part "MOUNT-PAD-ROUND3.2"))
    )
    (comp (ref "H3")
      (value "MOUNT-PAD-ROUND3.2")
      (footprint "eagle-import:3,2-PAD")
      (libsource (lib "eagle-import") (part "MOUNT-PAD-ROUND3.2"))
    )
    (comp (ref "H4")
      (value "MOUNT-PAD-ROUND3.2")
      (footprint "eagle-import:3,2-PAD")
      (libsource (lib "eagle-import") (part "MOUNT-PAD-ROUND3.2"))
    )
    (comp (ref "H5")
      (value "MOUNT-PAD-ROUND5.5")
      (footprint "eagle-import:5,5-PAD")
      (libsource (lib "eagle-import") (part "MOUNT-PAD-ROUND5.5"))
    )
    (comp (ref "H6")
      (value "MOUNT-PAD-ROUND5.5")
      (footprint "eagle-import:5,5-PAD")
      (libsource (lib "eagle-import") (part "MOUNT-PAD-ROUND5.5"))
    )
    (comp (ref "H7")
      (value "MOUNT-PAD-ROUND3.2")
      (footprint "eagle-import:3,2-PAD")
      (libsource (lib "eagle-import") (part "MOUNT-PAD-ROUND3.2"))
    )
    (comp (ref "AUX")
      (value "1751303")
      (footprint "eagle-import:1751303")
      (libsource (lib "eagle-import") (part "1751303"))
    )
    (comp (ref "C1")
      (value "1n")
      (footprint "eagle-import:C0603")
      (libsource (lib "eagle-import") (part "C-EUC0603"))
    )
    (comp (ref "C2")
      (value "1n")
      (footprint "eagle-import:C0603")
      (libsource (lib "eagle-import") (part "C-EUC0603"))
    )
    (comp (ref "C3")
      (value "1n")
      (footprint "eagle-import:C0603")
      (libsource (lib "eagle-import") (part "C-EUC0603"))
    )
    (comp (ref "C4")
      (value "1n")
      (footprint "eagle-import:C0603")
      (libsource (lib "eagle-import") (part "C-EUC0603"))
    )
    (comp (ref "C5")
      (value "100n")
      (footprint "eagle-import:C0603")
      (libsource (lib "eagle-import") (part "C-EUC0603"))
    )
    (comp (ref "C6")
      (value "100n")
      (footprint "eagle-import:C0603")
      (libsource (lib "eagle-import") (part "C-EUC0603"))
    )
    (comp (ref "C7")
      (value "100n")
      (footprint "eagle-import:C0603")
      (libsource (lib "eagle-import") (part "C-EUC0603"))
    )
    (comp (ref "C8")
      (value "100n")
      (footprint "eagle-import:C0603")
      (libsource (lib "eagle-import") (part "C-EUC0603"))
    )
    (comp (ref "C9")
      (value "1n")
      (footprint "eagle-import:C0603")
      (libsource (lib "eagle-import") (part "C-EUC0603"))
    )
    (comp (ref "C10")
      (value "1n")
      (footprint "eagle-import:C0603")
      (libsource (lib "eagle-import") (part "C-EUC0603"))
    )
    (comp (ref "C11")
      (value "1n")
      (footprint "eagle-import:C0603")
      (libsource (lib "eagle-import") (part "C-EUC0603"))
    )
    (comp (ref "C12")
      (value "1n")
      (footprint "eagle-import:C0603")
      (libsource (lib "eagle-import") (part "C-EUC0603"))
    )
    (comp (ref "C13")
      (value "100n")
      (footprint "eagle-import:C0603")
      (libsource (lib "eagle-import") (part "C-EUC0603"))
    )
    (comp (ref "C14")
      (value "100n")
      (footprint "eagle-import:C0603")
      (libsource (lib "eagle-import") (part "C-EUC0603"))
    )
    (comp (ref "C15")
      (value "100n")
      (footprint "eagle-import:C0603")
      (libsource (lib "eagle-import") (part "C-EUC0603"))
    )
    (comp (ref "C16")
      (value "100n")
      (footprint "eagle-import:C0603")
      (libsource (lib "eagle-import") (part "C-EUC0603"))
    )
    (comp (ref "D19")
      (value "DIODESOD-123")
      (footprint "eagle-import:SOD-123")
      (libsource (lib "eagle-import") (part "DIODESOD-123"))
    )
    (comp (ref "D20")
      (value "DIODESOD-123")
      (footprint "eagle-import:SOD-123")
      (libsource (lib "eagle-import") (part "DIODESOD-123"))
    )
    (comp (ref "D21")
      (value "DIODESOD-123")
      (footprint "eagle-import:SOD-123")
      (libsource (lib "eagle-import") (part "DIODESOD-123"))
    )
    (comp (ref "D22")
      (value "DIODESOD-123")
      (footprint "eagle-import:SOD-123")
      (libsource (lib "eagle-import") (part "DIODESOD-123"))
    )
    (comp (ref "D23")
      (value "DIODESOD-123")
      (footprint "eagle-import:SOD-123")
      (libsource (lib "eagle-import") (part "DIODESOD-123"))
    )
    (comp (ref "D24")
      (value "DIODESOD-123")
      (footprint "eagle-import:SOD-123")
      (libsource (lib "eagle-import") (part "DIODESOD-123"))
    )
    (comp (ref "D25")
      (value "DIODESOD-123")
      (footprint "eagle-import:SOD-123")
      (libsource (lib "eagle-import") (part "DIODESOD-123"))
    )
    (comp (ref "D26")
      (value "DIODESOD-123")
      (footprint "eagle-import:SOD-123")
      (libsource (lib "eagle-import") (part "DIODESOD-123"))
    )
    (comp (ref "D27")
      (value "DIODESOD-123")
      (footprint "eagle-import:SOD-123")
      (libsource (lib "eagle-import") (part "DIODESOD-123"))
    )
    (comp (ref "D28")
      (value "DIODESOD-123")
      (footprint "eagle-import:SOD-123")
      (libsource (lib "eagle-import") (part "DIODESOD-123"))
    )
    (comp (ref "D29")
      (value "DIODESOD-123")
      (footprint "eagle-import:SOD-123")
      (libsource (lib "eagle-import") (part "DIODESOD-123"))
    )
    (comp (ref "D30")
      (value "DIODESOD-123")
      (footprint "eagle-import:SOD-123")
      (libsource (lib "eagle-import") (part "DIODESOD-123"))
    )
    (comp (ref "D31")
      (value "DIODESOD-123")
      (footprint "eagle-import:SOD-123")
      (libsource (lib "eagle-import") (part "DIODESOD-123"))
    )
    (comp (ref "D32")
      (value "DIODESOD-123")
      (footprint "eagle-import:SOD-123")
      (libsource (lib "eagle-import") (part "DIODESOD-123"))
    )
    (comp (ref "D33")
      (value "DIODESOD-123")
      (footprint "eagle-import:SOD-123")
      (libsource (lib "eagle-import") (part "DIODESOD-123"))
    )
    (comp (ref "D34")
      (value "DIODESOD-123")
      (footprint "eagle-import:SOD-123")
      (libsource (lib "eagle-import") (part "DIODESOD-123"))
    )
    (comp (ref "R11")
      (value "10K")
      (footprint "eagle-import:CTS742C083-RES")
      (libsource (lib "eagle-import") (part "4R-NCTS742C083"))
    )
    (comp (ref "R12")
      (value "10K")
      (footprint "eagle-import:CTS742C083-RES")
      (libsource (lib "eagle-import") (part "4R-NCTS742C083"))
    )
    (comp (ref "R13")
      (value "10K")
      (footprint "eagle-import:CTS742C083-RES")
      (libsource (lib "eagle-import") (part "4R-NCTS742C083"))
    )
    (comp (ref "R14")
      (value "10K")
      (footprint "eagle-import:CTS742C083-RES")
      (libsource (lib "eagle-import") (part "4R-NCTS742C083"))
    )
    (comp (ref "R15")
      (value "10K")
      (footprint "eagle-import:CTS742C083-RES")
      (libsource (lib "eagle-import") (part "4R-NCTS742C083"))
    )
    (comp (ref "R16")
      (value "10K")
      (footprint "eagle-import:CTS742C083-RES")
      (libsource (lib "eagle-import") (part "4R-NCTS742C083"))
    )
    (comp (ref "R17")
      (value "100K")
      (footprint "eagle-import:CTS742C083-RES")
      (libsource (lib "eagle-import") (part "4R-NCTS742C083"))
    )
    (comp (ref "R18")
      (value "100K")
      (footprint "eagle-import:CTS742C083-RES")
      (libsource (lib "eagle-import") (part "4R-NCTS742C083"))
    )
    (comp (ref "U4")
      (value "IPS6044")
      (footprint "eagle-import:SO-28L")
      (libsource (lib "eagle-import") (part "IPS6044"))
    )
    (comp (ref "U5")
      (value "IPS6044")
      (footprint "eagle-import:SO-28L")
      (libsource (lib "eagle-import") (part "IPS6044"))
    )
    (comp (ref "U6")
      (value "ACS712")
      (footprint "eagle-import:SO08")
      (libsource (lib "eagle-import") (part "ACS712"))
    )
    (comp (ref "U7")
      (value "ACS712")
      (footprint "eagle-import:SO08")
      (libsource (lib "eagle-import") (part "ACS712"))
    )
    (comp (ref "U8")
      (value "ACS712")
      (footprint "eagle-import:SO08")
      (libsource (lib "eagle-import") (part "ACS712"))
    )
    (comp (ref "U9")
      (value "ACS712")
      (footprint "eagle-import:SO08")
      (libsource (lib "eagle-import") (part "ACS712"))
    )
    (comp (ref "U10")
      (value "ACS712")
      (footprint "eagle-import:SO08")
      (libsource (lib "eagle-import") (part "ACS712"))
    )
    (comp (ref "U11")
      (value "ACS712")
      (footprint "eagle-import:SO08")
      (libsource (lib "eagle-import") (part "ACS712"))
    )
    (comp (ref "U12")
      (value "ACS712")
      (footprint "eagle-import:SO08")
      (libsource (lib "eagle-import") (part "ACS712"))
    )
    (comp (ref "U13")
      (value "ACS712")
      (footprint "eagle-import:SO08")
      (libsource (lib "eagle-import") (part "ACS712"))
    )
  )
  (nets
    (net (code "1") (name "+3V3") (class "Default")
      (node (ref "HTU21D") (pin "3V3") (pinfunction "1_3V3") (pintype "passive"))
      (node (ref "JP17") (pin "2") (pinfunction "2_2") (pintype "passive"))
      (node (ref "R19") (pin "2") (pinfunction "2_2") (pintype "passive"))
      (node (ref "R20") (pin "2") (pinfunction "2_2") (pintype "passive"))
      (node (ref "U2") (pin "3.3V") (pinfunction "3.3V_3.3V") (pintype "bidirectional"))
    )
    (net (code "2") (name "+5V") (class "Default")
      (node (ref "C13") (pin "2") (pinfunction "2_2") (pintype "passive"))
      (node (ref "C14") (pin "2") (pinfunction "2_2") (pintype "passive"))
      (node (ref "C15") (pin "2") (pinfunction "2_2") (pintype "passive"))
      (node (ref "C16") (pin "2") (pinfunction "2_2") (pintype "passive"))
      (node (ref "C5") (pin "2") (pinfunction "2_2") (pintype "passive"))
      (node (ref "C6") (pin "2") (pinfunction "2_2") (pintype "passive"))
      (node (ref "C7") (pin "2") (pinfunction "2_2") (pintype "passive"))
      (node (ref "C8") (pin "2") (pinfunction "2_2") (pintype "passive"))
      (node (ref "F1") (pin "1") (pinfunction "1_1") (pintype "passive"))
      (node (ref "F4") (pin "1") (pinfunction "1_1") (pintype "passive"))
      (node (ref "F5") (pin "1") (pinfunction "1_1") (pintype "passive"))
      (node (ref "F6") (pin "1") (pinfunction "1_1") (pintype "passive"))
      (node (ref "IMU") (pin "VIN") (pinfunction "1_VIN") (pintype "passive"))
      (node (ref "JP17") (pin "3") (pinfunction "3_3") (pintype "passive"))
      (node (ref "R11") (pin "5") (pinfunction "1_5") (pintype "passive"))
      (node (ref "R12") (pin "1") (pinfunction "1_1") (pintype "passive"))
      (node (ref "R13") (pin "1") (pinfunction "1_1") (pintype "passive"))
      (node (ref "R13") (pin "3") (pinfunction "1_3") (pintype "passive"))
      (node (ref "R14") (pin "5") (pinfunction "1_5") (pintype "passive"))
      (node (ref "R15") (pin "1") (pinfunction "1_1") (pintype "passive"))
      (node (ref "R15") (pin "7") (pinfunction "1_7") (pintype "passive"))
      (node (ref "R16") (pin "3") (pinfunction "1_3") (pintype "passive"))
      (node (ref "R3") (pin "1") (pinfunction "1_1") (pintype "passive"))
      (node (ref "R3") (pin "3") (pinfunction "1_3") (pintype "passive"))
      (node (ref "R4") (pin "5") (pinfunction "1_5") (pintype "passive"))
      (node (ref "R4") (pin "7") (pinfunction "1_7") (pintype "passive"))
      (node (ref "R6") (pin "5") (pinfunction "1_5") (pintype "passive"))
      (node (ref "R7") (pin "1") (pinfunction "1_1") (pintype "passive"))
      (node (ref "R8") (pin "1") (pinfunction "1_1") (pintype "passive"))
      (node (ref "R8") (pin "3") (pinfunction "1_3") (pintype "passive"))
      (node (ref "U10") (pin "8") (pinfunction "VCC_8") (pintype "bidirectional"))
      (node (ref "U11") (pin "8") (pinfunction "VCC_8") (pintype "bidirectional"))
      (node (ref "U12") (pin "8") (pinfunction "VCC_8") (pintype "bidirectional"))
      (node (ref "U13") (pin "8") (pinfunction "VCC_8") (pintype "bidirectional"))
      (node (ref "U2") (pin "5V@0") (pinfunction "5V_5V@0") (pintype "bidirectional"))
      (node (ref "U2") (pin "5V@1") (pinfunction "5V_5V@1") (pintype "bidirectional"))
      (node (ref "U2") (pin "5V@2") (pinfunction "5V_5V@2") (pintype "bidirectional"))
      (node (ref "U6") (pin "8") (pinfunction "VCC_8") (pintype "bidirectional"))
      (node (ref "U7") (pin "8") (pinfunction "VCC_8") (pintype "bidirectional"))
      (node (ref "U8") (pin "8") (pinfunction "VCC_8") (pintype "bidirectional"))
      (node (ref "U9") (pin "8") (pinfunction "VCC_8") (pintype "bidirectional"))
    )
    (net (code "3") (name "+5V{slash}1") (class "Default")
      (node (ref "C24") (pin "1") (pinfunction "1_1") (pintype "passive"))
      (node (ref "C25") (pin "1") (pinfunction "1_1") (pintype "passive"))
      (node (ref "L1") (pin "2") (pinfunction "2_2") (pintype "passive"))
      (node (ref "R22") (pin "2") (pinfunction "2_2") (pintype "passive"))
      (node (ref "R38") (pin "2") (pinfunction "2_2") (pintype "passive"))
      (node (ref "U$1") (pin "51") (pinfunction "VDD_5V_51") (pintype "power_in"))
      (node (ref "U$1") (pin "52") (pinfunction "VDD_5V_52") (pintype "power_in"))
      (node (ref "U$2") (pin "23") (pinfunction "23_23") (pintype "passive"))
      (node (ref "U$5") (pin "23") (pinfunction "23_23") (pintype "passive"))
    )
    (net (code "4") (name "+12V") (class "Default")
      (node (ref "C17") (pin "1") (pinfunction "1_1") (pintype "passive"))
      (node (ref "C18") (pin "1") (pinfunction "1_1") (pintype "passive"))
      (node (ref "C19") (pin "1") (pinfunction "1_1") (pintype "passive"))
      (node (ref "C28") (pin "1") (pinfunction "1_1") (pintype "passive"))
      (node (ref "C29") (pin "1") (pinfunction "1_1") (pintype "passive"))
      (node (ref "C30") (pin "1") (pinfunction "1_1") (pintype "passive"))
      (node (ref "D10") (pin "C") (pinfunction "C_C") (pintype "passive"))
      (node (ref "D12") (pin "C") (pinfunction "C_C") (pintype "passive"))
      (node (ref "D14") (pin "C") (pinfunction "C_C") (pintype "passive"))
      (node (ref "D16") (pin "C") (pinfunction "C_C") (pintype "passive"))
      (node (ref "D18") (pin "C") (pinfunction "C_C") (pintype "passive"))
      (node (ref "D20") (pin "C") (pinfunction "C_C") (pintype "passive"))
      (node (ref "D22") (pin "C") (pinfunction "C_C") (pintype "passive"))
      (node (ref "D24") (pin "C") (pinfunction "C_C") (pintype "passive"))
      (node (ref "D26") (pin "C") (pinfunction "C_C") (pintype "passive"))
      (node (ref "D28") (pin "C") (pinfunction "C_C") (pintype "passive"))
      (node (ref "D30") (pin "C") (pinfunction "C_C") (pintype "passive"))
      (node (ref "D32") (pin "C") (pinfunction "C_C") (pintype "passive"))
      (node (ref "D34") (pin "C") (pinfunction "C_C") (pintype "passive"))
      (node (ref "D4") (pin "C") (pinfunction "C_C") (pintype "passive"))
      (node (ref "D6") (pin "C") (pinfunction "C_C") (pintype "passive"))
      (node (ref "D8") (pin "C") (pinfunction "C_C") (pintype "passive"))
      (node (ref "J3") (pin "1") (pinfunction "1_1") (pintype "passive"))
      (node (ref "JP17") (pin "6") (pinfunction "6_6") (pintype "passive"))
      (node (ref "R10") (pin "2") (pinfunction "2_2") (pintype "passive"))
      (node (ref "R10") (pin "4") (pinfunction "2_4") (pintype "passive"))
      (node (ref "R10") (pin "6") (pinfunction "2_6") (pintype "passive"))
      (node (ref "R10") (pin "8") (pinfunction "2_8") (pintype "passive"))
      (node (ref "R17") (pin "2") (pinfunction "2_2") (pintype "passive"))
      (node (ref "R17") (pin "4") (pinfunction "2_4") (pintype "passive"))
      (node (ref "R17") (pin "6") (pinfunction "2_6") (pintype "passive"))
      (node (ref "R17") (pin "8") (pinfunction "2_8") (pintype "passive"))
      (node (ref "R18") (pin "2") (pinfunction "2_2") (pintype "passive"))
      (node (ref "R18") (pin "4") (pinfunction "2_4") (pintype "passive"))
      (node (ref "R18") (pin "6") (pinfunction "2_6") (pintype "passive"))
      (node (ref "R18") (pin "8") (pinfunction "2_8") (pintype "passive"))
      (node (ref "R24") (pin "2") (pinfunction "2_2") (pintype "passive"))
      (node (ref "R29") (pin "2") (pinfunction "2_2") (pintype "passive"))
      (node (ref "R9") (pin "2") (pinfunction "2_2") (pintype "passive"))
      (node (ref "R9") (pin "4") (pinfunction "2_4") (pintype "passive"))
      (node (ref "R9") (pin "6") (pinfunction "2_6") (pintype "passive"))
      (node (ref "R9") (pin "8") (pinfunction "2_8") (pintype "passive"))
      (node (ref "U1") (pin "1") (pinfunction "VCC_1") (pintype "bidirectional"))
      (node (ref "U1") (pin "14") (pinfunction "VCC_14") (pintype "bidirectional"))
      (node (ref "U1") (pin "15") (pinfunction "VCC_15") (pintype "bidirectional"))
      (node (ref "U1") (pin "28") (pinfunction "VCC_28") (pintype "bidirectional"))
      (node (ref "U14") (pin "2") (pinfunction "VIN_2") (pintype "bidirectional"))
      (node (ref "U15") (pin "2") (pinfunction "VIN_2") (pintype "bidirectional"))
      (node (ref "U2") (pin "VIN") (pinfunction "VIN_VIN") (pintype "bidirectional"))
      (node (ref "U3") (pin "1") (pinfunction "VCC_1") (pintype "bidirectional"))
      (node (ref "U3") (pin "14") (pinfunction "VCC_14") (pintype "bidirectional"))
      (node (ref "U3") (pin "15") (pinfunction "VCC_15") (pintype "bidirectional"))
      (node (ref "U3") (pin "28") (pinfunction "VCC_28") (pintype "bidirectional"))
      (node (ref "U4") (pin "1") (pinfunction "VCC_1") (pintype "bidirectional"))
      (node (ref "U4") (pin "14") (pinfunction "VCC_14") (pintype "bidirectional"))
      (node (ref "U4") (pin "15") (pinfunction "VCC_15") (pintype "bidirectional"))
      (node (ref "U4") (pin "28") (pinfunction "VCC_28") (pintype "bidirectional"))
      (node (ref "U5") (pin "1") (pinfunction "VCC_1") (pintype "bidirectional"))
      (node (ref "U5") (pin "14") (pinfunction "VCC_14") (pintype "bidirectional"))
      (node (ref "U5") (pin "15") (pinfunction "VCC_15") (pintype "bidirectional"))
      (node (ref "U5") (pin "28") (pinfunction "VCC_28") (pintype "bidirectional"))
    )
    (net (code "5") (name "7V4") (class "Default")
      (node (ref "C26") (pin "1") (pinfunction "1_1") (pintype "passive"))
      (node (ref "C27") (pin "1") (pinfunction "1_1") (pintype "passive"))
      (node (ref "F7") (pin "1") (pinfunction "1_1") (pintype "passive"))
      (node (ref "F8") (pin "1") (pinfunction "1_1") (pintype "passive"))
      (node (ref "F9") (pin "1") (pinfunction "1_1") (pintype "passive"))
      (node (ref "L2") (pin "2") (pinfunction "2_2") (pintype "passive"))
      (node (ref "R27") (pin "2") (pinfunction "2_2") (pintype "passive"))
      (node (ref "R39") (pin "2") (pinfunction "2_2") (pintype "passive"))
    )
    (net (code "6") (name "13") (class "Default")
      (node (ref "JP14") (pin "3") (pinfunction "3_3") (pintype "passive"))
      (node (ref "U2") (pin "13") (pinfunction "13_13") (pintype "bidirectional"))
    )
    (net (code "7") (name "AUX1") (class "Default")
      (node (ref "JP15") (pin "9") (pinfunction "9_9") (pintype "passive"))
      (node (ref "R11") (pin "1") (pinfunction "1_1") (pintype "passive"))
      (node (ref "U2") (pin "36") (pinfunction "36_36") (pintype "bidirectional"))
    )
    (net (code "8") (name "AUX1FB") (class "Default")
      (node (ref "JP16") (pin "9") (pinfunction "9_9") (pintype "passive"))
      (node (ref "R11") (pin "3") (pinfunction "1_3") (pintype "passive"))
      (node (ref "U2") (pin "37") (pinfunction "37_37") (pintype "bidirectional"))
    )
    (net (code "9") (name "AUX1I") (class "Default")
      (node (ref "JP12") (pin "7") (pinfunction "7_7") (pintype "passive"))
      (node (ref "U2") (pin "A9") (pinfunction "A9_A9") (pintype "bidirectional"))
      (node (ref "U6") (pin "7") (pinfunction "VIO_7") (pintype "bidirectional"))
    )
    (net (code "10") (name "AUX2") (class "Default")
      (node (ref "JP16") (pin "10") (pinfunction "10_10") (pintype "passive"))
      (node (ref "R12") (pin "3") (pinfunction "1_3") (pintype "passive"))
      (node (ref "U2") (pin "35") (pinfunction "35_35") (pintype "bidirectional"))
    )
    (net (code "11") (name "AUX2FB") (class "Default")
      (node (ref "JP15") (pin "10") (pinfunction "10_10") (pintype "passive"))
      (node (ref "R11") (pin "7") (pinfunction "1_7") (pintype "passive"))
      (node (ref "U2") (pin "34") (pinfunction "34_34") (pintype "bidirectional"))
    )
    (net (code "12") (name "AUX2I") (class "Default")
      (node (ref "JP12") (pin "8") (pinfunction "8_8") (pintype "passive"))
      (node (ref "U2") (pin "A8") (pinfunction "A8_A8") (pintype "bidirectional"))
      (node (ref "U7") (pin "7") (pinfunction "VIO_7") (pintype "bidirectional"))
    )
    (net (code "13") (name "AUX3") (class "Default")
      (node (ref "JP15") (pin "11") (pinfunction "11_11") (pintype "passive"))
      (node (ref "R12") (pin "5") (pinfunction "1_5") (pintype "passive"))
      (node (ref "U2") (pin "32") (pinfunction "32_32") (pintype "bidirectional"))
    )
    (net (code "14") (name "AUX3FB") (class "Default")
      (node (ref "JP16") (pin "11") (pinfunction "11_11") (pintype "passive"))
      (node (ref "R12") (pin "7") (pinfunction "1_7") (pintype "passive"))
      (node (ref "U2") (pin "33") (pinfunction "33_33") (pintype "bidirectional"))
    )
    (net (code "15") (name "AUX3I") (class "Default")
      (node (ref "JP11") (pin "1") (pinfunction "1_1") (pintype "passive"))
      (node (ref "U2") (pin "A7") (pinfunction "A7_A7") (pintype "bidirectional"))
      (node (ref "U8") (pin "7") (pinfunction "VIO_7") (pintype "bidirectional"))
    )
    (net (code "16") (name "AUX4") (class "Default")
      (node (ref "JP16") (pin "12") (pinfunction "12_12") (pintype "passive"))
      (node (ref "R13") (pin "7") (pinfunction "1_7") (pintype "passive"))
      (node (ref "U2") (pin "31") (pinfunction "31_31") (pintype "bidirectional"))
    )
    (net (code "17") (name "AUX4FB") (class "Default")
      (node (ref "JP15") (pin "12") (pinfunction "12_12") (pintype "passive"))
      (node (ref "R13") (pin "5") (pinfunction "1_5") (pintype "passive"))
      (node (ref "U2") (pin "30") (pinfunction "30_30") (pintype "bidirectional"))
    )
    (net (code "18") (name "AUX4I") (class "Default")
      (node (ref "JP11") (pin "2") (pinfunction "2_2") (pintype "passive"))
      (node (ref "U2") (pin "A6") (pinfunction "A6_A6") (pintype "bidirectional"))
      (node (ref "U9") (pin "7") (pinfunction "VIO_7") (pintype "bidirectional"))
    )
    (net (code "19") (name "AUX5") (class "Default")
      (node (ref "JP15") (pin "13") (pinfunction "13_13") (pintype "passive"))
      (node (ref "R14") (pin "1") (pinfunction "1_1") (pintype "passive"))
      (node (ref "U2") (pin "28") (pinfunction "28_28") (pintype "bidirectional"))
    )
    (net (code "20") (name "AUX5FB") (class "Default")
      (node (ref "JP16") (pin "13") (pinfunction "13_13") (pintype "passive"))
      (node (ref "R14") (pin "3") (pinfunction "1_3") (pintype "passive"))
      (node (ref "U2") (pin "29") (pinfunction "29_29") (pintype "bidirectional"))
    )
    (net (code "21") (name "AUX5I") (class "Default")
      (node (ref "JP11") (pin "3") (pinfunction "3_3") (pintype "passive"))
      (node (ref "U10") (pin "7") (pinfunction "VIO_7") (pintype "bidirectional"))
      (node (ref "U2") (pin "A5") (pinfunction "A5_A5") (pintype "bidirectional"))
    )
    (net (code "22") (name "AUX6") (class "Default")
      (node (ref "JP16") (pin "14") (pinfunction "14_14") (pintype "passive"))
      (node (ref "R15") (pin "3") (pinfunction "1_3") (pintype "passive"))
      (node (ref "U2") (pin "27") (pinfunction "27_27") (pintype "bidirectional"))
    )
    (net (code "23") (name "AUX6FB") (class "Default")
      (node (ref "JP15") (pin "14") (pinfunction "14_14") (pintype "passive"))
      (node (ref "R14") (pin "7") (pinfunction "1_7") (pintype "passive"))
      (node (ref "U2") (pin "26") (pinfunction "26_26") (pintype "bidirectional"))
    )
    (net (code "24") (name "AUX6I") (class "Default")
      (node (ref "JP11") (pin "4") (pinfunction "4_4") (pintype "passive"))
      (node (ref "U11") (pin "7") (pinfunction "VIO_7") (pintype "bidirectional"))
      (node (ref "U2") (pin "A4") (pinfunction "A4_A4") (pintype "bidirectional"))
    )
    (net (code "25") (name "AUX7") (class "Default")
      (node (ref "JP15") (pin "15") (pinfunction "15_15") (pintype "passive"))
      (node (ref "R15") (pin "5") (pinfunction "1_5") (pintype "passive"))
      (node (ref "U2") (pin "24") (pinfunction "24_24") (pintype "bidirectional"))
    )
    (net (code "26") (name "AUX7FB") (class "Default")
      (node (ref "JP16") (pin "15") (pinfunction "15_15") (pintype "passive"))
      (node (ref "R16") (pin "1") (pinfunction "1_1") (pintype "passive"))
      (node (ref "U2") (pin "25") (pinfunction "25_25") (pintype "bidirectional"))
    )
    (net (code "27") (name "AUX7I") (class "Default")
      (node (ref "JP11") (pin "5") (pinfunction "5_5") (pintype "passive"))
      (node (ref "U12") (pin "7") (pinfunction "VIO_7") (pintype "bidirectional"))
      (node (ref "U2") (pin "A3") (pinfunction "A3_A3") (pintype "bidirectional"))
    )
    (net (code "28") (name "AUX8") (class "Default")
      (node (ref "JP16") (pin "16") (pinfunction "16_16") (pintype "passive"))
      (node (ref "R16") (pin "7") (pinfunction "1_7") (pintype "passive"))
      (node (ref "U2") (pin "23") (pinfunction "23_23") (pintype "bidirectional"))
    )
    (net (code "29") (name "AUX8FB") (class "Default")
      (node (ref "JP15") (pin "16") (pinfunction "16_16") (pintype "passive"))
      (node (ref "R16") (pin "5") (pinfunction "1_5") (pintype "passive"))
      (node (ref "U2") (pin "22") (pinfunction "22_22") (pintype "bidirectional"))
    )
    (net (code "30") (name "AUX8I") (class "Default")
      (node (ref "JP11") (pin "6") (pinfunction "6_6") (pintype "passive"))
      (node (ref "U13") (pin "7") (pinfunction "VIO_7") (pintype "bidirectional"))
      (node (ref "U2") (pin "A2") (pinfunction "A2_A2") (pintype "bidirectional"))
    )
    (net (code "31") (name "GND") (class "Default")
      (node (ref "5V/1-STAT") (pin "C") (pinfunction "C_C") (pintype "passive"))
      (node (ref "7V4-STAT") (pin "C") (pinfunction "C_C") (pintype "passive"))
      (node (ref "C1") (pin "1") (pinfunction "1_1") (pintype "passive"))
      (node (ref "C10") (pin "1") (pinfunction "1_1") (pintype "passive"))
      (node (ref "C11") (pin "1") (pinfunction "1_1") (pintype "passive"))
      (node (ref "C12") (pin "1") (pinfunction "1_1") (pintype "passive"))
      (node (ref "C13") (pin "1") (pinfunction "1_1") (pintype "passive"))
      (node (ref "C14") (pin "1") (pinfunction "1_1") (pintype "passive"))
      (node (ref "C15") (pin "1") (pinfunction "1_1") (pintype "passive"))
      (node (ref "C16") (pin "1") (pinfunction "1_1") (pintype "passive"))
      (node (ref "C17") (pin "2") (pinfunction "2_2") (pintype "passive"))
      (node (ref "C18") (pin "2") (pinfunction "2_2") (pintype "passive"))
      (node (ref "C19") (pin "2") (pinfunction "2_2") (pintype "passive"))
      (node (ref "C2") (pin "1") (pinfunction "1_1") (pintype "passive"))
      (node (ref "C20") (pin "2") (pinfunction "2_2") (pintype "passive"))
      (node (ref "C23") (pin "2") (pinfunction "2_2") (pintype "passive"))
      (node (ref "C24") (pin "2") (pinfunction "2_2") (pintype "passive"))
      (node (ref "C25") (pin "2") (pinfunction "2_2") (pintype "passive"))
      (node (ref "C26") (pin "2") (pinfunction "2_2") (pintype "passive"))
      (node (ref "C27") (pin "2") (pinfunction "2_2") (pintype "passive"))
      (node (ref "C28") (pin "2") (pinfunction "2_2") (pintype "passive"))
      (node (ref "C29") (pin "2") (pinfunction "2_2") (pintype "passive"))
      (node (ref "C3") (pin "1") (pinfunction "1_1") (pintype "passive"))
      (node (ref "C30") (pin "2") (pinfunction "2_2") (pintype "passive"))
      (node (ref "C31") (pin "2") (pinfunction "2_2") (pintype "passive"))
      (node (ref "C34") (pin "2") (pinfunction "2_2") (pintype "passive"))
      (node (ref "C4") (pin "1") (pinfunction "1_1") (pintype "passive"))
      (node (ref "C5") (pin "1") (pinfunction "1_1") (pintype "passive"))
      (node (ref "C6") (pin "1") (pinfunction "1_1") (pintype "passive"))
      (node (ref "C7") (pin "1") (pinfunction "1_1") (pintype "passive"))
      (node (ref "C8") (pin "1") (pinfunction "1_1") (pintype "passive"))
      (node (ref "C9") (pin "1") (pinfunction "1_1") (pintype "passive"))
      (node (ref "D1") (pin "A") (pinfunction "A_A") (pintype "passive"))
      (node (ref "D11") (pin "A") (pinfunction "A_A") (pintype "passive"))
      (node (ref "D13") (pin "A") (pinfunction "A_A") (pintype "passive"))
      (node (ref "D15") (pin "A") (pinfunction "A_A") (pintype "passive"))
      (node (ref "D17") (pin "A") (pinfunction "A_A") (pintype "passive"))
      (node (ref "D19") (pin "A") (pinfunction "A_A") (pintype "passive"))
      (node (ref "D2") (pin "A") (pinfunction "A_A") (pintype "passive"))
      (node (ref "D21") (pin "A") (pinfunction "A_A") (pintype "passive"))
      (node (ref "D23") (pin "A") (pinfunction "A_A") (pintype "passive"))
      (node (ref "D25") (pin "A") (pinfunction "A_A") (pintype "passive"))
      (node (ref "D27") (pin "A") (pinfunction "A_A") (pintype "passive"))
      (node (ref "D29") (pin "A") (pinfunction "A_A") (pintype "passive"))
      (node (ref "D3") (pin "A") (pinfunction "A_A") (pintype "passive"))
      (node (ref "D31") (pin "A") (pinfunction "A_A") (pintype "passive"))
      (node (ref "D33") (pin "A") (pinfunction "A_A") (pintype "passive"))
      (node (ref "D35") (pin "A") (pinfunction "A_A") (pintype "passive"))
      (node (ref "D36") (pin "A") (pinfunction "A_A") (pintype "passive"))
      (node (ref "D5") (pin "A") (pinfunction "A_A") (pintype "passive"))
      (node (ref "D7") (pin "A") (pinfunction "A_A") (pintype "passive"))
      (node (ref "D9") (pin "A") (pinfunction "A_A") (pintype "passive"))
      (node (ref "GPS") (pin "GND") (pinfunction "6_GND") (pintype "passive"))
      (node (ref "GPS") (pin "MNT@0") (pinfunction "9_MNT@0") (pintype "passive"))
      (node (ref "GPS") (pin "MNT@1") (pinfunction "9_MNT@1") (pintype "passive"))
      (node (ref "H1") (pin "B3,2") (pinfunction "MOUNT_B3,2") (pintype "passive"))
      (node (ref "H2") (pin "B3,2") (pinfunction "MOUNT_B3,2") (pintype "passive"))
      (node (ref "H3") (pin "B3,2") (pinfunction "MOUNT_B3,2") (pintype "passive"))
      (node (ref "H4") (pin "B3,2") (pinfunction "MOUNT_B3,2") (pintype "passive"))
      (node (ref "H5") (pin "B5,5") (pinfunction "MOUNT_B5,5") (pintype "passive"))
      (node (ref "H6") (pin "B5,5") (pinfunction "MOUNT_B5,5") (pintype "passive"))
      (node (ref "H7") (pin "B3,2") (pinfunction "MOUNT_B3,2") (pintype "passive"))
      (node (ref "HTU21D") (pin "GND") (pinfunction "2_GND") (pintype "passive"))
      (node (ref "I1/V2") (pin "4") (pinfunction "4_4") (pintype "passive"))
      (node (ref "I2/V3") (pin "4") (pinfunction "4_4") (pintype "passive"))
      (node (ref "I3/V4") (pin "4") (pinfunction "4_4") (pintype "passive"))
      (node (ref "I4") (pin "4") (pinfunction "4_4") (pintype "passive"))
      (node (ref "IMU") (pin "GND") (pinfunction "3_GND") (pintype "passive"))
      (node (ref "IMU") (pin "MNT@0") (pinfunction "9_MNT@0") (pintype "passive"))
      (node (ref "IMU") (pin "MNT@1") (pinfunction "9_MNT@1") (pintype "passive"))
      (node (ref "IMU") (pin "MNT@2") (pinfunction "9_MNT@2") (pintype "passive"))
      (node (ref "IMU") (pin "MNT@3") (pinfunction "9_MNT@3") (pintype "passive"))
      (node (ref "J3") (pin "2") (pinfunction "2_2") (pintype "passive"))
      (node (ref "JP17") (pin "4") (pinfunction "4_4") (pintype "passive"))
      (node (ref "JP17") (pin "5") (pinfunction "5_5") (pintype "passive"))
      (node (ref "PWR") (pin "C") (pinfunction "C_C") (pintype "passive"))
      (node (ref "R21") (pin "1") (pinfunction "1_1") (pintype "passive"))
      (node (ref "R23") (pin "1") (pinfunction "1_1") (pintype "passive"))
      (node (ref "R25") (pin "1") (pinfunction "1_1") (pintype "passive"))
      (node (ref "R26") (pin "1") (pinfunction "1_1") (pintype "passive"))
      (node (ref "R28") (pin "1") (pinfunction "1_1") (pintype "passive"))
      (node (ref "R30") (pin "1") (pinfunction "1_1") (pintype "passive"))
      (node (ref "R31") (pin "1") (pinfunction "1_1") (pintype "passive"))
      (node (ref "R32") (pin "1") (pinfunction "1_1") (pintype "passive"))
      (node (ref "R33") (pin "1") (pinfunction "1_1") (pintype "passive"))
      (node (ref "R34") (pin "1") (pinfunction "1_1") (pintype "passive"))
      (node (ref "R35") (pin "1") (pinfunction "1_1") (pintype "passive"))
      (node (ref "R36") (pin "1") (pinfunction "1_1") (pintype "passive"))
      (node (ref "R37") (pin "1") (pinfunction "1_1") (pintype "passive"))
      (node (ref "REV") (pin "A") (pinfunction "A_A") (pintype "passive"))
      (node (ref "SERVO_AUX1") (pin "1") (pinfunction "1_1") (pintype "passive"))
      (node (ref "SERVO_AUX2") (pin "1") (pinfunction "1_1") (pintype "passive"))
      (node (ref "STEERING") (pin "1") (pinfunction "1_1") (pintype "passive"))
      (node (ref "U$1") (pin "1") (pinfunction "GND_1") (pintype "power_in"))
      (node (ref "U$1") (pin "2") (pinfunction "GND_2") (pintype "power_in"))
      (node (ref "U$1") (pin "47") (pinfunction "GND_47") (pintype "power_in"))
      (node (ref "U$1") (pin "48") (pinfunction "GND_48") (pintype "power_in"))
      (node (ref "U$1") (pin "80") (pinfunction "GNDA_ADC_80") (pintype "passive"))
      (node (ref "U$1") (pin "89") (pinfunction "GND_89") (pintype "power_in"))
      (node (ref "U$1") (pin "90") (pinfunction "GND_90") (pintype "power_in"))
      (node (ref "U$1") (pin "91") (pinfunction "GND_91") (pintype "power_in"))
      (node (ref "U$1") (pin "92") (pinfunction "GND_92") (pintype "power_in"))
      (node (ref "U$2") (pin "25") (pinfunction "25_25") (pintype "passive"))
      (node (ref "U$2") (pin "3") (pinfunction "3_3") (pintype "passive"))
      (node (ref "U$2") (pin "4") (pinfunction "4_4") (pintype "passive"))
      (node (ref "U$2") (pin "9") (pinfunction "9_9") (pintype "passive"))
      (node (ref "U$3") (pin "24") (pinfunction "24_24") (pintype "passive"))
      (node (ref "U$4") (pin "24") (pinfunction "24_24") (pintype "passive"))
      (node (ref "U$5") (pin "25") (pinfunction "25_25") (pintype "passive"))
      (node (ref "U$5") (pin "3") (pinfunction "3_3") (pintype "passive"))
      (node (ref "U$5") (pin "4") (pinfunction "4_4") (pintype "passive"))
      (node (ref "U1") (pin "13") (pinfunction "GND_13") (pintype "bidirectional"))
      (node (ref "U1") (pin "2") (pinfunction "GND_2") (pintype "bidirectional"))
      (node (ref "U1") (pin "7") (pinfunction "GND_7") (pintype "bidirectional"))
      (node (ref "U1") (pin "8") (pinfunction "GND_8") (pintype "bidirectional"))
      (node (ref "U10") (pin "5") (pinfunction "GND_5") (pintype "bidirectional"))
      (node (ref "U11") (pin "5") (pinfunction "GND_5") (pintype "bidirectional"))
      (node (ref "U12") (pin "5") (pinfunction "GND_5") (pintype "bidirectional"))
      (node (ref "U13") (pin "5") (pinfunction "GND_5") (pintype "bidirectional"))
      (node (ref "U14") (pin "7") (pinfunction "GND_7") (pintype "bidirectional"))
      (node (ref "U15") (pin "7") (pinfunction "GND_7") (pintype "bidirectional"))
      (node (ref "U2") (pin "GND@0") (pinfunction "GND_GND@0") (pintype "bidirectional"))
      (node (ref "U2") (pin "GND@1") (pinfunction "GND_GND@1") (pintype "bidirectional"))
      (node (ref "U2") (pin "GND@2") (pinfunction "GND_GND@2") (pintype "bidirectional"))
      (node (ref "U2") (pin "GND@3") (pinfunction "GND_GND@3") (pintype "bidirectional"))
      (node (ref "U2") (pin "GND@4") (pinfunction "GND_GND@4") (pintype "bidirectional"))
      (node (ref "U3") (pin "13") (pinfunction "GND_13") (pintype "bidirectional"))
      (node (ref "U3") (pin "2") (pinfunction "GND_2") (pintype "bidirectional"))
      (node (ref "U3") (pin "7") (pinfunction "GND_7") (pintype "bidirectional"))
      (node (ref "U3") (pin "8") (pinfunction "GND_8") (pintype "bidirectional"))
      (node (ref "U4") (pin "13") (pinfunction "GND_13") (pintype "bidirectional"))
      (node (ref "U4") (pin "2") (pinfunction "GND_2") (pintype "bidirectional"))
      (node (ref "U4") (pin "7") (pinfunction "GND_7") (pintype "bidirectional"))
      (node (ref "U4") (pin "8") (pinfunction "GND_8") (pintype "bidirectional"))
      (node (ref "U5") (pin "13") (pinfunction "GND_13") (pintype "bidirectional"))
      (node (ref "U5") (pin "2") (pinfunction "GND_2") (pintype "bidirectional"))
      (node (ref "U5") (pin "7") (pinfunction "GND_7") (pintype "bidirectional"))
      (node (ref "U5") (pin "8") (pinfunction "GND_8") (pintype "bidirectional"))
      (node (ref "U6") (pin "5") (pinfunction "GND_5") (pintype "bidirectional"))
      (node (ref "U7") (pin "5") (pinfunction "GND_5") (pintype "bidirectional"))
      (node (ref "U8") (pin "5") (pinfunction "GND_5") (pintype "bidirectional"))
      (node (ref "U9") (pin "5") (pinfunction "GND_5") (pintype "bidirectional"))
    )
    (net (code "32") (name "I1") (class "Default")
      (node (ref "I1/V2") (pin "2") (pinfunction "2_2") (pintype "passive"))
      (node (ref "JP12") (pin "6") (pinfunction "6_6") (pintype "passive"))
      (node (ref "U2") (pin "A10") (pinfunction "A10_A10") (pintype "bidirectional"))
    )
    (net (code "33") (name "I2") (class "Default")
      (node (ref "I2/V3") (pin "2") (pinfunction "2_2") (pintype "passive"))
      (node (ref "JP12") (pin "3") (pinfunction "3_3") (pintype "passive"))
      (node (ref "U2") (pin "A13") (pinfunction "A13_A13") (pintype "bidirectional"))
    )
    (net (code "34") (name "I3") (class "Default")
      (node (ref "I3/V4") (pin "2") (pinfunction "2_2") (pintype "passive"))
      (node (ref "JP12") (pin "4") (pinfunction "4_4") (pintype "passive"))
      (node (ref "U2") (pin "A12") (pinfunction "A12_A12") (pintype "bidirectional"))
    )
    (net (code "35") (name "I4") (class "Default")
      (node (ref "I4") (pin "2") (pinfunction "2_2") (pintype "passive"))
      (node (ref "JP12") (pin "5") (pinfunction "5_5") (pintype "passive"))
      (node (ref "U2") (pin "A11") (pinfunction "A11_A11") (pintype "bidirectional"))
    )
    (net (code "36") (name "Net-(5V/1-STAT-PadA)") (class "Default")
      (node (ref "5V/1-STAT") (pin "A") (pinfunction "A_A") (pintype "passive"))
      (node (ref "R38") (pin "1") (pinfunction "1_1") (pintype "passive"))
    )
    (net (code "37") (name "Net-(7V4-STAT-PadA)") (class "Default")
      (node (ref "7V4-STAT") (pin "A") (pinfunction "A_A") (pintype "passive"))
      (node (ref "R39") (pin "1") (pinfunction "1_1") (pintype "passive"))
    )
    (net (code "38") (name "Net-(AUXA-K)") (class "Default")
      (node (ref "AUX") (pin "1") (pinfunction "K_1") (pintype "passive"))
      (node (ref "U6") (pin "3") (pinfunction "IP-_3") (pintype "bidirectional"))
      (node (ref "U6") (pin "4") (pinfunction "IP-_4") (pintype "bidirectional"))
    )
    (net (code "39") (name "Net-(AUXB-K)") (class "Default")
      (node (ref "AUX") (pin "2") (pinfunction "K_2") (pintype "passive"))
      (node (ref "U7") (pin "3") (pinfunction "IP-_3") (pintype "bidirectional"))
      (node (ref "U7") (pin "4") (pinfunction "IP-_4") (pintype "bidirectional"))
    )
    (net (code "40") (name "Net-(AUXC-K)") (class "Default")
      (node (ref "AUX") (pin "3") (pinfunction "K_3") (pintype "passive"))
      (node (ref "U8") (pin "3") (pinfunction "IP-_3") (pintype "bidirectional"))
      (node (ref "U8") (pin "4") (pinfunction "IP-_4") (pintype "bidirectional"))
    )
    (net (code "41") (name "Net-(AUXD-K)") (class "Default")
      (node (ref "AUX") (pin "4") (pinfunction "K_4") (pintype "passive"))
      (node (ref "U9") (pin "3") (pinfunction "IP-_3") (pintype "bidirectional"))
      (node (ref "U9") (pin "4") (pinfunction "IP-_4") (pintype "bidirectional"))
    )
    (net (code "42") (name "Net-(AUXE-K)") (class "Default")
      (node (ref "AUX") (pin "5") (pinfunction "K_5") (pintype "passive"))
      (node (ref "U10") (pin "3") (pinfunction "IP-_3") (pintype "bidirectional"))
      (node (ref "U10") (pin "4") (pinfunction "IP-_4") (pintype "bidirectional"))
    )
    (net (code "43") (name "Net-(AUXF-K)") (class "Default")
      (node (ref "AUX") (pin "6") (pinfunction "K_6") (pintype "passive"))
      (node (ref "U11") (pin "3") (pinfunction "IP-_3") (pintype "bidirectional"))
      (node (ref "U11") (pin "4") (pinfunction "IP-_4") (pintype "bidirectional"))
    )
    (net (code "44") (name "Net-(AUXG-K)") (class "Default")
      (node (ref "AUX") (pin "7") (pinfunction "K_7") (pintype "passive"))
      (node (ref "U12") (pin "3") (pinfunction "IP-_3") (pintype "bidirectional"))
      (node (ref "U12") (pin "4") (pinfunction "IP-_4") (pintype "bidirectional"))
    )
    (net (code "45") (name "Net-(AUXH-K)") (class "Default")
      (node (ref "AUX") (pin "8") (pinfunction "K_8") (pintype "passive"))
      (node (ref "U13") (pin "3") (pinfunction "IP-_3") (pintype "bidirectional"))
      (node (ref "U13") (pin "4") (pinfunction "IP-_4") (pintype "bidirectional"))
    )
    (net (code "46") (name "Net-(C22-Pad2)") (class "Default")
      (node (ref "C22") (pin "2") (pinfunction "2_2") (pintype "passive"))
      (node (ref "R21") (pin "2") (pinfunction "2_2") (pintype "passive"))
    )
    (net (code "47") (name "Net-(C33-Pad2)") (class "Default")
      (node (ref "C33") (pin "2") (pinfunction "2_2") (pintype "passive"))
      (node (ref "R26") (pin "2") (pinfunction "2_2") (pintype "passive"))
    )
    (net (code "48") (name "Net-(D25-PadC)") (class "Default")
      (node (ref "D25") (pin "C") (pinfunction "C_C") (pintype "passive"))
      (node (ref "D26") (pin "A") (pinfunction "A_A") (pintype "passive"))
      (node (ref "R17") (pin "1") (pinfunction "1_1") (pintype "passive"))
      (node (ref "U4") (pin "16") (pinfunction "OUT4_16") (pintype "bidirectional"))
      (node (ref "U4") (pin "17") (pinfunction "OUT4_17") (pintype "bidirectional"))
      (node (ref "U4") (pin "18") (pinfunction "OUT4_18") (pintype "bidirectional"))
      (node (ref "U9") (pin "1") (pinfunction "IP+_1") (pintype "bidirectional"))
      (node (ref "U9") (pin "2") (pinfunction "IP+_2") (pintype "bidirectional"))
    )
    (net (code "49") (name "Net-(D33-PadC)") (class "Default")
      (node (ref "D33") (pin "C") (pinfunction "C_C") (pintype "passive"))
      (node (ref "D34") (pin "A") (pinfunction "A_A") (pintype "passive"))
      (node (ref "R18") (pin "1") (pinfunction "1_1") (pintype "passive"))
      (node (ref "U13") (pin "1") (pinfunction "IP+_1") (pintype "bidirectional"))
      (node (ref "U13") (pin "2") (pinfunction "IP+_2") (pintype "bidirectional"))
      (node (ref "U5") (pin "16") (pinfunction "OUT4_16") (pintype "bidirectional"))
      (node (ref "U5") (pin "17") (pinfunction "OUT4_17") (pintype "bidirectional"))
      (node (ref "U5") (pin "18") (pinfunction "OUT4_18") (pintype "bidirectional"))
    )
    (net (code "50") (name "Net-(F1-Pad2)") (class "Default")
      (node (ref "F1") (pin "2") (pinfunction "2_2") (pintype "passive"))
      (node (ref "I1/V2") (pin "1") (pinfunction "1_1") (pintype "passive"))
    )
    (net (code "51") (name "Net-(F4-Pad2)") (class "Default")
      (node (ref "F4") (pin "2") (pinfunction "2_2") (pintype "passive"))
      (node (ref "I2/V3") (pin "1") (pinfunction "1_1") (pintype "passive"))
    )
    (net (code "52") (name "Net-(F5-Pad2)") (class "Default")
      (node (ref "F5") (pin "2") (pinfunction "2_2") (pintype "passive"))
      (node (ref "I3/V4") (pin "1") (pinfunction "1_1") (pintype "passive"))
    )
    (net (code "53") (name "Net-(F6-Pad2)") (class "Default")
      (node (ref "F6") (pin "2") (pinfunction "2_2") (pintype "passive"))
      (node (ref "I4") (pin "1") (pinfunction "1_1") (pintype "passive"))
    )
    (net (code "54") (name "Net-(F7-Pad2)") (class "Default")
      (node (ref "F7") (pin "2") (pinfunction "2_2") (pintype "passive"))
      (node (ref "SERVO_AUX1") (pin "2") (pinfunction "2_2") (pintype "passive"))
    )
    (net (code "55") (name "Net-(F8-Pad2)") (class "Default")
      (node (ref "F8") (pin "2") (pinfunction "2_2") (pintype "passive"))
      (node (ref "SERVO_AUX2") (pin "2") (pinfunction "2_2") (pintype "passive"))
    )
    (net (code "56") (name "Net-(F9-Pad2)") (class "Default")
      (node (ref "F9") (pin "2") (pinfunction "2_2") (pintype "passive"))
      (node (ref "STEERING") (pin "2") (pinfunction "2_2") (pintype "passive"))
    )
    (net (code "57") (name "Net-(GPSA-2)") (class "Default")
      (node (ref "GPS") (pin "RX") (pinfunction "2_RX") (pintype "passive"))
      (node (ref "U$1") (pin "59") (pinfunction "UART4_TXD_59") (pintype "passive"))
      (node (ref "U$5") (pin "19") (pinfunction "19_19") (pintype "passive"))
    )
    (net (code "58") (name "Net-(GPSA-3)") (class "Default")
      (node (ref "GPS") (pin "TX") (pinfunction "3_TX") (pintype "passive"))
      (node (ref "U$1") (pin "57") (pinfunction "UART4_RXD_57") (pintype "passive"))
      (node (ref "U$5") (pin "20") (pinfunction "20_20") (pintype "passive"))
    )
    (net (code "59") (name "Net-(GPSA-5)") (class "Default")
      (node (ref "GPS") (pin "VIN") (pinfunction "5_VIN") (pintype "passive"))
      (node (ref "U$1") (pin "53") (pinfunction "SYS_5V_53") (pintype "power_in"))
      (node (ref "U$5") (pin "22") (pinfunction "22_22") (pintype "passive"))
    )
    (net (code "60") (name "Net-(JP10-Pad1)") (class "Default")
      (node (ref "JP10") (pin "1") (pinfunction "1_1") (pintype "passive"))
      (node (ref "U2") (pin "7") (pinfunction "7_7") (pintype "bidirectional"))
    )
    (net (code "61") (name "Net-(JP10-Pad2)") (class "Default")
      (node (ref "JP10") (pin "2") (pinfunction "2_2") (pintype "passive"))
      (node (ref "U2") (pin "6") (pinfunction "6_6") (pintype "bidirectional"))
    )
    (net (code "62") (name "Net-(JP11-Pad8)") (class "Default")
      (node (ref "JP11") (pin "8") (pinfunction "8_8") (pintype "passive"))
      (node (ref "R29") (pin "1") (pinfunction "1_1") (pintype "passive"))
      (node (ref "R30") (pin "2") (pinfunction "2_2") (pintype "passive"))
      (node (ref "U2") (pin "A0") (pinfunction "A0_A0") (pintype "bidirectional"))
    )
    (net (code "63") (name "Net-(JP14-Pad4)") (class "Default")
      (node (ref "JP14") (pin "4") (pinfunction "4_4") (pintype "passive"))
      (node (ref "U2") (pin "12") (pinfunction "12_12") (pintype "bidirectional"))
    )
    (net (code "64") (name "Net-(JP14-Pad5)") (class "Default")
      (node (ref "JP14") (pin "5") (pinfunction "5_5") (pintype "passive"))
      (node (ref "U2") (pin "11") (pinfunction "11_11") (pintype "bidirectional"))
    )
    (net (code "65") (name "Net-(JP14-Pad6)") (class "Default")
      (node (ref "JP14") (pin "6") (pinfunction "6_6") (pintype "passive"))
      (node (ref "U2") (pin "10") (pinfunction "10_10") (pintype "bidirectional"))
    )
    (net (code "66") (name "Net-(JP14-Pad7)") (class "Default")
      (node (ref "JP14") (pin "7") (pinfunction "7_7") (pintype "passive"))
      (node (ref "U2") (pin "9") (pinfunction "9_9") (pintype "bidirectional"))
    )
    (net (code "67") (name "Net-(JP14-Pad8)") (class "Default")
      (node (ref "JP14") (pin "8") (pinfunction "8_8") (pintype "passive"))
      (node (ref "U2") (pin "8") (pinfunction "8_8") (pintype "bidirectional"))
    )
    (net (code "68") (name "Net-(LED3-PadC)") (class "Default")
      (node (ref "LED3") (pin "C") (pinfunction "C_C") (pintype "passive"))
      (node (ref "R25") (pin "2") (pinfunction "2_2") (pintype "passive"))
    )
    (net (code "69") (name "Net-(LED4-PadC)") (class "Default")
      (node (ref "LED4") (pin "C") (pinfunction "C_C") (pintype "passive"))
      (node (ref "R31") (pin "2") (pinfunction "2_2") (pintype "passive"))
    )
    (net (code "70") (name "Net-(LED5-PadC)") (class "Default")
      (node (ref "LED5") (pin "C") (pinfunction "C_C") (pintype "passive"))
      (node (ref "R32") (pin "2") (pinfunction "2_2") (pintype "passive"))
    )
    (net (code "71") (name "Net-(LED6-PadC)") (class "Default")
      (node (ref "LED6") (pin "C") (pinfunction "C_C") (pintype "passive"))
      (node (ref "R33") (pin "2") (pinfunction "2_2") (pintype "passive"))
    )
    (net (code "72") (name "Net-(LED7-PadC)") (class "Default")
      (node (ref "LED7") (pin "C") (pinfunction "C_C") (pintype "passive"))
      (node (ref "R34") (pin "2") (pinfunction "2_2") (pintype "passive"))
    )
    (net (code "73") (name "Net-(LED8-PadC)") (class "Default")
      (node (ref "LED8") (pin "C") (pinfunction "C_C") (pintype "passive"))
      (node (ref "R35") (pin "2") (pinfunction "2_2") (pintype "passive"))
    )
    (net (code "74") (name "Net-(LED9-PadC)") (class "Default")
      (node (ref "LED9") (pin "C") (pinfunction "C_C") (pintype "passive"))
      (node (ref "R36") (pin "2") (pinfunction "2_2") (pintype "passive"))
    )
    (net (code "75") (name "Net-(LED10-PadC)") (class "Default")
      (node (ref "LED10") (pin "C") (pinfunction "C_C") (pintype "passive"))
      (node (ref "R37") (pin "2") (pinfunction "2_2") (pintype "passive"))
    )
    (net (code "76") (name "Net-(PWR-PadA)") (class "Default")
      (node (ref "PWR") (pin "A") (pinfunction "A_A") (pintype "passive"))
      (node (ref "R24") (pin "1") (pinfunction "1_1") (pintype "passive"))
      (node (ref "REV") (pin "C") (pinfunction "C_C") (pintype "passive"))
    )
    (net (code "77") (name "Net-(R3B-2)") (class "Default")
      (node (ref "R3") (pin "4") (pinfunction "2_4") (pintype "passive"))
      (node (ref "R3") (pin "6") (pinfunction "2_6") (pintype "passive"))
      (node (ref "U1") (pin "11") (pinfunction "DG4_11") (pintype "bidirectional"))
    )
    (net (code "78") (name "Net-(R3D-2)") (class "Default")
      (node (ref "R3") (pin "8") (pinfunction "2_8") (pintype "passive"))
      (node (ref "U1") (pin "12") (pinfunction "IN4_12") (pintype "bidirectional"))
    )
    (net (code "79") (name "Net-(R4B-2)") (class "Default")
      (node (ref "R4") (pin "4") (pinfunction "2_4") (pintype "passive"))
      (node (ref "R4") (pin "6") (pinfunction "2_6") (pintype "passive"))
      (node (ref "U1") (pin "4") (pinfunction "DG1_4") (pintype "bidirectional"))
    )
    (net (code "80") (name "Net-(R4D-2)") (class "Default")
      (node (ref "R4") (pin "8") (pinfunction "2_8") (pintype "passive"))
      (node (ref "R5") (pin "2") (pinfunction "2_2") (pintype "passive"))
      (node (ref "U1") (pin "5") (pinfunction "DG2_5") (pintype "bidirectional"))
    )
    (net (code "81") (name "Net-(R5B-2)") (class "Default")
      (node (ref "R5") (pin "4") (pinfunction "2_4") (pintype "passive"))
      (node (ref "U1") (pin "6") (pinfunction "IN2_6") (pintype "bidirectional"))
    )
    (net (code "82") (name "Net-(R5C-2)") (class "Default")
      (node (ref "R5") (pin "6") (pinfunction "2_6") (pintype "passive"))
      (node (ref "U1") (pin "9") (pinfunction "IN3_9") (pintype "bidirectional"))
    )
    (net (code "83") (name "Net-(R5D-2)") (class "Default")
      (node (ref "R3") (pin "2") (pinfunction "2_2") (pintype "passive"))
      (node (ref "R5") (pin "8") (pinfunction "2_8") (pintype "passive"))
      (node (ref "U1") (pin "10") (pinfunction "DG3_10") (pintype "bidirectional"))
    )
    (net (code "84") (name "Net-(R6B-2)") (class "Default")
      (node (ref "R6") (pin "4") (pinfunction "2_4") (pintype "passive"))
      (node (ref "R6") (pin "6") (pinfunction "2_6") (pintype "passive"))
      (node (ref "U3") (pin "4") (pinfunction "DG1_4") (pintype "bidirectional"))
    )
    (net (code "85") (name "Net-(R6D-2)") (class "Default")
      (node (ref "R6") (pin "8") (pinfunction "2_8") (pintype "passive"))
      (node (ref "R7") (pin "2") (pinfunction "2_2") (pintype "passive"))
      (node (ref "U3") (pin "5") (pinfunction "DG2_5") (pintype "bidirectional"))
    )
    (net (code "86") (name "Net-(R7B-2)") (class "Default")
      (node (ref "R7") (pin "4") (pinfunction "2_4") (pintype "passive"))
      (node (ref "U3") (pin "6") (pinfunction "IN2_6") (pintype "bidirectional"))
    )
    (net (code "87") (name "Net-(R7C-2)") (class "Default")
      (node (ref "R7") (pin "6") (pinfunction "2_6") (pintype "passive"))
      (node (ref "U3") (pin "9") (pinfunction "IN3_9") (pintype "bidirectional"))
    )
    (net (code "88") (name "Net-(R7D-2)") (class "Default")
      (node (ref "R7") (pin "8") (pinfunction "2_8") (pintype "passive"))
      (node (ref "R8") (pin "2") (pinfunction "2_2") (pintype "passive"))
      (node (ref "U3") (pin "10") (pinfunction "DG3_10") (pintype "bidirectional"))
    )
    (net (code "89") (name "Net-(R8B-2)") (class "Default")
      (node (ref "R8") (pin "4") (pinfunction "2_4") (pintype "passive"))
      (node (ref "R8") (pin "6") (pinfunction "2_6") (pintype "passive"))
      (node (ref "U3") (pin "11") (pinfunction "DG4_11") (pintype "bidirectional"))
    )
    (net (code "90") (name "Net-(R8D-2)") (class "Default")
      (node (ref "R8") (pin "8") (pinfunction "2_8") (pintype "passive"))
      (node (ref "U3") (pin "12") (pinfunction "IN4_12") (pintype "bidirectional"))
    )
    (net (code "91") (name "Net-(R9B-1)") (class "Default")
      (node (ref "D7") (pin "C") (pinfunction "C_C") (pintype "passive"))
      (node (ref "D8") (pin "A") (pinfunction "A_A") (pintype "passive"))
      (node (ref "LED5") (pin "A") (pinfunction "A_A") (pintype "passive"))
      (node (ref "R9") (pin "3") (pinfunction "1_3") (pintype "passive"))
      (node (ref "RELAY") (pin "3") (pinfunction "K_3") (pintype "passive"))
      (node (ref "U1") (pin "19") (pinfunction "OUT3_19") (pintype "bidirectional"))
      (node (ref "U1") (pin "20") (pinfunction "OUT3_20") (pintype "bidirectional"))
      (node (ref "U1") (pin "21") (pinfunction "OUT3_21") (pintype "bidirectional"))
    )
    (net (code "92") (name "Net-(R9C-1)") (class "Default")
      (node (ref "D5") (pin "C") (pinfunction "C_C") (pintype "passive"))
      (node (ref "D6") (pin "A") (pinfunction "A_A") (pintype "passive"))
      (node (ref "LED4") (pin "A") (pinfunction "A_A") (pintype "passive"))
      (node (ref "R9") (pin "5") (pinfunction "1_5") (pintype "passive"))
      (node (ref "RELAY") (pin "2") (pinfunction "K_2") (pintype "passive"))
      (node (ref "U1") (pin "22") (pinfunction "OUT2_22") (pintype "bidirectional"))
      (node (ref "U1") (pin "23") (pinfunction "OUT2_23") (pintype "bidirectional"))
      (node (ref "U1") (pin "24") (pinfunction "OUT2_24") (pintype "bidirectional"))
    )
    (net (code "93") (name "Net-(R9D-1)") (class "Default")
      (node (ref "D3") (pin "C") (pinfunction "C_C") (pintype "passive"))
      (node (ref "D4") (pin "A") (pinfunction "A_A") (pintype "passive"))
      (node (ref "LED3") (pin "A") (pinfunction "A_A") (pintype "passive"))
      (node (ref "R9") (pin "7") (pinfunction "1_7") (pintype "passive"))
      (node (ref "RELAY") (pin "1") (pinfunction "K_1") (pintype "passive"))
      (node (ref "U1") (pin "25") (pinfunction "OUT1_25") (pintype "bidirectional"))
      (node (ref "U1") (pin "26") (pinfunction "OUT1_26") (pintype "bidirectional"))
      (node (ref "U1") (pin "27") (pinfunction "OUT1_27") (pintype "bidirectional"))
    )
    (net (code "94") (name "Net-(R10B-1)") (class "Default")
      (node (ref "D15") (pin "C") (pinfunction "C_C") (pintype "passive"))
      (node (ref "D16") (pin "A") (pinfunction "A_A") (pintype "passive"))
      (node (ref "LED9") (pin "A") (pinfunction "A_A") (pintype "passive"))
      (node (ref "R10") (pin "3") (pinfunction "1_3") (pintype "passive"))
      (node (ref "RELAY") (pin "7") (pinfunction "K_7") (pintype "passive"))
      (node (ref "U3") (pin "19") (pinfunction "OUT3_19") (pintype "bidirectional"))
      (node (ref "U3") (pin "20") (pinfunction "OUT3_20") (pintype "bidirectional"))
      (node (ref "U3") (pin "21") (pinfunction "OUT3_21") (pintype "bidirectional"))
    )
    (net (code "95") (name "Net-(R10C-1)") (class "Default")
      (node (ref "D13") (pin "C") (pinfunction "C_C") (pintype "passive"))
      (node (ref "D14") (pin "A") (pinfunction "A_A") (pintype "passive"))
      (node (ref "LED8") (pin "A") (pinfunction "A_A") (pintype "passive"))
      (node (ref "R10") (pin "5") (pinfunction "1_5") (pintype "passive"))
      (node (ref "RELAY") (pin "6") (pinfunction "K_6") (pintype "passive"))
      (node (ref "U3") (pin "22") (pinfunction "OUT2_22") (pintype "bidirectional"))
      (node (ref "U3") (pin "23") (pinfunction "OUT2_23") (pintype "bidirectional"))
      (node (ref "U3") (pin "24") (pinfunction "OUT2_24") (pintype "bidirectional"))
    )
    (net (code "96") (name "Net-(R10D-1)") (class "Default")
      (node (ref "D11") (pin "C") (pinfunction "C_C") (pintype "passive"))
      (node (ref "D12") (pin "A") (pinfunction "A_A") (pintype "passive"))
      (node (ref "LED7") (pin "A") (pinfunction "A_A") (pintype "passive"))
      (node (ref "R10") (pin "7") (pinfunction "1_7") (pintype "passive"))
      (node (ref "RELAY") (pin "5") (pinfunction "K_5") (pintype "passive"))
      (node (ref "U3") (pin "25") (pinfunction "OUT1_25") (pintype "bidirectional"))
      (node (ref "U3") (pin "26") (pinfunction "OUT1_26") (pintype "bidirectional"))
      (node (ref "U3") (pin "27") (pinfunction "OUT1_27") (pintype "bidirectional"))
    )
    (net (code "97") (name "Net-(R11B-2)") (class "Default")
      (node (ref "R11") (pin "4") (pinfunction "2_4") (pintype "passive"))
      (node (ref "R11") (pin "6") (pinfunction "2_6") (pintype "passive"))
      (node (ref "U4") (pin "4") (pinfunction "DG1_4") (pintype "bidirectional"))
    )
    (net (code "98") (name "Net-(R11D-2)") (class "Default")
      (node (ref "R11") (pin "8") (pinfunction "2_8") (pintype "passive"))
      (node (ref "R12") (pin "2") (pinfunction "2_2") (pintype "passive"))
      (node (ref "U4") (pin "5") (pinfunction "DG2_5") (pintype "bidirectional"))
    )
    (net (code "99") (name "Net-(R12B-2)") (class "Default")
      (node (ref "R12") (pin "4") (pinfunction "2_4") (pintype "passive"))
      (node (ref "U4") (pin "6") (pinfunction "IN2_6") (pintype "bidirectional"))
    )
    (net (code "100") (name "Net-(R12C-2)") (class "Default")
      (node (ref "R12") (pin "6") (pinfunction "2_6") (pintype "passive"))
      (node (ref "U4") (pin "9") (pinfunction "IN3_9") (pintype "bidirectional"))
    )
    (net (code "101") (name "Net-(R12D-2)") (class "Default")
      (node (ref "R12") (pin "8") (pinfunction "2_8") (pintype "passive"))
      (node (ref "R13") (pin "2") (pinfunction "2_2") (pintype "passive"))
      (node (ref "U4") (pin "10") (pinfunction "DG3_10") (pintype "bidirectional"))
    )
    (net (code "102") (name "Net-(R13B-2)") (class "Default")
      (node (ref "R13") (pin "4") (pinfunction "2_4") (pintype "passive"))
      (node (ref "R13") (pin "6") (pinfunction "2_6") (pintype "passive"))
      (node (ref "U4") (pin "11") (pinfunction "DG4_11") (pintype "bidirectional"))
    )
    (net (code "103") (name "Net-(R13D-2)") (class "Default")
      (node (ref "R13") (pin "8") (pinfunction "2_8") (pintype "passive"))
      (node (ref "U4") (pin "12") (pinfunction "IN4_12") (pintype "bidirectional"))
    )
    (net (code "104") (name "Net-(R14B-2)") (class "Default")
      (node (ref "R14") (pin "4") (pinfunction "2_4") (pintype "passive"))
      (node (ref "R14") (pin "6") (pinfunction "2_6") (pintype "passive"))
      (node (ref "U5") (pin "4") (pinfunction "DG1_4") (pintype "bidirectional"))
    )
    (net (code "105") (name "Net-(R14D-2)") (class "Default")
      (node (ref "R14") (pin "8") (pinfunction "2_8") (pintype "passive"))
      (node (ref "R15") (pin "2") (pinfunction "2_2") (pintype "passive"))
      (node (ref "U5") (pin "5") (pinfunction "DG2_5") (pintype "bidirectional"))
    )
    (net (code "106") (name "Net-(R15B-2)") (class "Default")
      (node (ref "R15") (pin "4") (pinfunction "2_4") (pintype "passive"))
      (node (ref "U5") (pin "6") (pinfunction "IN2_6") (pintype "bidirectional"))
    )
    (net (code "107") (name "Net-(R15C-2)") (class "Default")
      (node (ref "R15") (pin "6") (pinfunction "2_6") (pintype "passive"))
      (node (ref "U5") (pin "9") (pinfunction "IN3_9") (pintype "bidirectional"))
    )
    (net (code "108") (name "Net-(R15D-2)") (class "Default")
      (node (ref "R15") (pin "8") (pinfunction "2_8") (pintype "passive"))
      (node (ref "R16") (pin "2") (pinfunction "2_2") (pintype "passive"))
      (node (ref "U5") (pin "10") (pinfunction "DG3_10") (pintype "bidirectional"))
    )
    (net (code "109") (name "Net-(R16B-2)") (class "Default")
      (node (ref "R16") (pin "4") (pinfunction "2_4") (pintype "passive"))
      (node (ref "R16") (pin "6") (pinfunction "2_6") (pintype "passive"))
      (node (ref "U5") (pin "11") (pinfunction "DG4_11") (pintype "bidirectional"))
    )
    (net (code "110") (name "Net-(R16D-2)") (class "Default")
      (node (ref "R16") (pin "8") (pinfunction "2_8") (pintype "passive"))
      (node (ref "U5") (pin "12") (pinfunction "IN4_12") (pintype "bidirectional"))
    )
    (net (code "111") (name "Net-(R17B-1)") (class "Default")
      (node (ref "D23") (pin "C") (pinfunction "C_C") (pintype "passive"))
      (node (ref "D24") (pin "A") (pinfunction "A_A") (pintype "passive"))
      (node (ref "R17") (pin "3") (pinfunction "1_3") (pintype "passive"))
      (node (ref "U4") (pin "19") (pinfunction "OUT3_19") (pintype "bidirectional"))
      (node (ref "U4") (pin "20") (pinfunction "OUT3_20") (pintype "bidirectional"))
      (node (ref "U4") (pin "21") (pinfunction "OUT3_21") (pintype "bidirectional"))
      (node (ref "U8") (pin "1") (pinfunction "IP+_1") (pintype "bidirectional"))
      (node (ref "U8") (pin "2") (pinfunction "IP+_2") (pintype "bidirectional"))
    )
    (net (code "112") (name "Net-(R17C-1)") (class "Default")
      (node (ref "D21") (pin "C") (pinfunction "C_C") (pintype "passive"))
      (node (ref "D22") (pin "A") (pinfunction "A_A") (pintype "passive"))
      (node (ref "R17") (pin "5") (pinfunction "1_5") (pintype "passive"))
      (node (ref "U4") (pin "22") (pinfunction "OUT2_22") (pintype "bidirectional"))
      (node (ref "U4") (pin "23") (pinfunction "OUT2_23") (pintype "bidirectional"))
      (node (ref "U4") (pin "24") (pinfunction "OUT2_24") (pintype "bidirectional"))
      (node (ref "U7") (pin "1") (pinfunction "IP+_1") (pintype "bidirectional"))
      (node (ref "U7") (pin "2") (pinfunction "IP+_2") (pintype "bidirectional"))
    )
    (net (code "113") (name "Net-(R17D-1)") (class "Default")
      (node (ref "D19") (pin "C") (pinfunction "C_C") (pintype "passive"))
      (node (ref "D20") (pin "A") (pinfunction "A_A") (pintype "passive"))
      (node (ref "R17") (pin "7") (pinfunction "1_7") (pintype "passive"))
      (node (ref "U4") (pin "25") (pinfunction "OUT1_25") (pintype "bidirectional"))
      (node (ref "U4") (pin "26") (pinfunction "OUT1_26") (pintype "bidirectional"))
      (node (ref "U4") (pin "27") (pinfunction "OUT1_27") (pintype "bidirectional"))
      (node (ref "U6") (pin "1") (pinfunction "IP+_1") (pintype "bidirectional"))
      (node (ref "U6") (pin "2") (pinfunction "IP+_2") (pintype "bidirectional"))
    )
    (net (code "114") (name "Net-(R18B-1)") (class "Default")
      (node (ref "D31") (pin "C") (pinfunction "C_C") (pintype "passive"))
      (node (ref "D32") (pin "A") (pinfunction "A_A") (pintype "passive"))
      (node (ref "R18") (pin "3") (pinfunction "1_3") (pintype "passive"))
      (node (ref "U12") (pin "1") (pinfunction "IP+_1") (pintype "bidirectional"))
      (node (ref "U12") (pin "2") (pinfunction "IP+_2") (pintype "bidirectional"))
      (node (ref "U5") (pin "19") (pinfunction "OUT3_19") (pintype "bidirectional"))
      (node (ref "U5") (pin "20") (pinfunction "OUT3_20") (pintype "bidirectional"))
      (node (ref "U5") (pin "21") (pinfunction "OUT3_21") (pintype "bidirectional"))
    )
    (net (code "115") (name "Net-(R18C-1)") (class "Default")
      (node (ref "D29") (pin "C") (pinfunction "C_C") (pintype "passive"))
      (node (ref "D30") (pin "A") (pinfunction "A_A") (pintype "passive"))
      (node (ref "R18") (pin "5") (pinfunction "1_5") (pintype "passive"))
      (node (ref "U11") (pin "1") (pinfunction "IP+_1") (pintype "bidirectional"))
      (node (ref "U11") (pin "2") (pinfunction "IP+_2") (pintype "bidirectional"))
      (node (ref "U5") (pin "22") (pinfunction "OUT2_22") (pintype "bidirectional"))
      (node (ref "U5") (pin "23") (pinfunction "OUT2_23") (pintype "bidirectional"))
      (node (ref "U5") (pin "24") (pinfunction "OUT2_24") (pintype "bidirectional"))
    )
    (net (code "116") (name "Net-(R18D-1)") (class "Default")
      (node (ref "D27") (pin "C") (pinfunction "C_C") (pintype "passive"))
      (node (ref "D28") (pin "A") (pinfunction "A_A") (pintype "passive"))
      (node (ref "R18") (pin "7") (pinfunction "1_7") (pintype "passive"))
      (node (ref "U10") (pin "1") (pinfunction "IP+_1") (pintype "bidirectional"))
      (node (ref "U10") (pin "2") (pinfunction "IP+_2") (pintype "bidirectional"))
      (node (ref "U5") (pin "25") (pinfunction "OUT1_25") (pintype "bidirectional"))
      (node (ref "U5") (pin "26") (pinfunction "OUT1_26") (pintype "bidirectional"))
      (node (ref "U5") (pin "27") (pinfunction "OUT1_27") (pintype "bidirectional"))
    )
    (net (code "117") (name "Net-(RELAYD-K)") (class "Default")
      (node (ref "D10") (pin "A") (pinfunction "A_A") (pintype "passive"))
      (node (ref "D9") (pin "C") (pinfunction "C_C") (pintype "passive"))
      (node (ref "LED6") (pin "A") (pinfunction "A_A") (pintype "passive"))
      (node (ref "R9") (pin "1") (pinfunction "1_1") (pintype "passive"))
      (node (ref "RELAY") (pin "4") (pinfunction "K_4") (pintype "passive"))
      (node (ref "U1") (pin "16") (pinfunction "OUT4_16") (pintype "bidirectional"))
      (node (ref "U1") (pin "17") (pinfunction "OUT4_17") (pintype "bidirectional"))
      (node (ref "U1") (pin "18") (pinfunction "OUT4_18") (pintype "bidirectional"))
    )
    (net (code "118") (name "Net-(RELAYH-K)") (class "Default")
      (node (ref "D17") (pin "C") (pinfunction "C_C") (pintype "passive"))
      (node (ref "D18") (pin "A") (pinfunction "A_A") (pintype "passive"))
      (node (ref "LED10") (pin "A") (pinfunction "A_A") (pintype "passive"))
      (node (ref "R10") (pin "1") (pinfunction "1_1") (pintype "passive"))
      (node (ref "RELAY") (pin "8") (pinfunction "K_8") (pintype "passive"))
      (node (ref "U3") (pin "16") (pinfunction "OUT4_16") (pintype "bidirectional"))
      (node (ref "U3") (pin "17") (pinfunction "OUT4_17") (pintype "bidirectional"))
      (node (ref "U3") (pin "18") (pinfunction "OUT4_18") (pintype "bidirectional"))
    )
    (net (code "119") (name "Net-(U$1-AIN0)") (class "Default")
      (node (ref "U$1") (pin "85") (pinfunction "AIN0_85") (pintype "power_in"))
      (node (ref "U$5") (pin "6") (pinfunction "6_6") (pintype "passive"))
    )
    (net (code "120") (name "Net-(U$1-AIN1)") (class "Default")
      (node (ref "U$1") (pin "86") (pinfunction "AIN1_86") (pintype "passive"))
      (node (ref "U$2") (pin "6") (pinfunction "6_6") (pintype "passive"))
    )
    (net (code "121") (name "Net-(U$1-AIN2)") (class "Default")
      (node (ref "U$1") (pin "83") (pinfunction "AIN2_83") (pintype "passive"))
      (node (ref "U$5") (pin "7") (pinfunction "7_7") (pintype "passive"))
    )
    (net (code "122") (name "Net-(U$1-AIN3)") (class "Default")
      (node (ref "U$1") (pin "84") (pinfunction "AIN3_84") (pintype "passive"))
      (node (ref "U$2") (pin "7") (pinfunction "7_7") (pintype "passive"))
    )
    (net (code "123") (name "Net-(U$1-AIN4)") (class "Default")
      (node (ref "U$1") (pin "79") (pinfunction "AIN4_79") (pintype "passive"))
      (node (ref "U$5") (pin "9") (pinfunction "9_9") (pintype "passive"))
    )
    (net (code "124") (name "Net-(U$1-AIN5)") (class "Default")
      (node (ref "U$1") (pin "82") (pinfunction "AIN5_82") (pintype "passive"))
      (node (ref "U$2") (pin "8") (pinfunction "8_8") (pintype "passive"))
    )
    (net (code "125") (name "Net-(U$1-AIN6)") (class "Default")
      (node (ref "U$1") (pin "81") (pinfunction "AIN6_81") (pintype "passive"))
      (node (ref "U$5") (pin "8") (pinfunction "8_8") (pintype "passive"))
    )
    (net (code "126") (name "Net-(U$1-CLKOUT2)") (class "Default")
      (node (ref "U$1") (pin "87") (pinfunction "CLKOUT2_87") (pintype "input"))
      (node (ref "U$5") (pin "5") (pinfunction "5_5") (pintype "passive"))
    )
    (net (code "127") (name "Net-(U$1-EHRPWM1A)") (class "Default")
      (node (ref "U$1") (pin "60") (pinfunction "EHRPWM1A_60") (pintype "passive"))
      (node (ref "U$2") (pin "19") (pinfunction "19_19") (pintype "passive"))
    )
    (net (code "128") (name "Net-(U$1-EHRPWM1B)") (class "Default")
      (node (ref "U$1") (pin "62") (pinfunction "EHRPWM1B_62") (pintype "passive"))
      (node (ref "U$2") (pin "18") (pinfunction "18_18") (pintype "passive"))
    )
    (net (code "129") (name "Net-(U$1-EHRPWM2A)") (class "Default")
      (node (ref "U$1") (pin "19") (pinfunction "EHRPWM2A_19") (pintype "passive"))
      (node (ref "U$4") (pin "15") (pinfunction "15_15") (pintype "passive"))
    )
    (net (code "130") (name "Net-(U$1-EHRPWM2B)") (class "Default")
      (node (ref "U$1") (pin "13") (pinfunction "EHRPWM2B_13") (pintype "passive"))
      (node (ref "U$4") (pin "18") (pinfunction "18_18") (pintype "passive"))
    )
    (net (code "131") (name "Net-(U$1-GPIO0_7)") (class "Default")
      (node (ref "U$1") (pin "88") (pinfunction "GPIO0_7_88") (pintype "passive"))
      (node (ref "U$2") (pin "5") (pinfunction "5_5") (pintype "passive"))
    )
    (net (code "132") (name "Net-(U$1-GPIO0_26)") (class "Default")
      (node (ref "U$1") (pin "14") (pinfunction "GPIO0_26_14") (pintype "passive"))
      (node (ref "U$3") (pin "18") (pinfunction "18_18") (pintype "passive"))
    )
    (net (code "133") (name "Net-(U$1-GPIO0_27)") (class "Default")
      (node (ref "U$1") (pin "17") (pinfunction "GPIO0_27_17") (pintype "passive"))
      (node (ref "U$4") (pin "16") (pinfunction "16_16") (pintype "passive"))
    )
    (net (code "134") (name "Net-(U$1-GPIO1_0)") (class "Default")
      (node (ref "U$1") (pin "25") (pinfunction "GPIO1_0_25") (pintype "passive"))
      (node (ref "U$4") (pin "12") (pinfunction "12_12") (pintype "passive"))
    )
    (net (code "135") (name "Net-(U$1-GPIO1_1)") (class "Default")
      (node (ref "U$1") (pin "24") (pinfunction "GPIO1_1_24") (pintype "passive"))
      (node (ref "U$3") (pin "13") (pinfunction "13_13") (pintype "passive"))
    )
    (net (code "136") (name "Net-(U$1-GPIO1_2)") (class "Default")
      (node (ref "U$1") (pin "5") (pinfunction "GPIO1_2_5") (pintype "passive"))
      (node (ref "U$4") (pin "22") (pinfunction "22_22") (pintype "passive"))
    )
    (net (code "137") (name "Net-(U$1-GPIO1_3)") (class "Default")
      (node (ref "U$1") (pin "6") (pinfunction "GPIO1_3_6") (pintype "passive"))
      (node (ref "U$3") (pin "22") (pinfunction "22_22") (pintype "passive"))
    )
    (net (code "138") (name "Net-(U$1-GPIO1_4)") (class "Default")
      (node (ref "U$1") (pin "23") (pinfunction "GPIO1_4_23") (pintype "passive"))
      (node (ref "U$4") (pin "13") (pinfunction "13_13") (pintype "passive"))
    )
    (net (code "139") (name "Net-(U$1-GPIO1_5)") (class "Default")
      (node (ref "U$1") (pin "22") (pinfunction "GPIO1_5_22") (pintype "passive"))
      (node (ref "U$3") (pin "14") (pinfunction "14_14") (pintype "passive"))
    )
    (net (code "140") (name "Net-(U$1-GPIO1_6)") (class "Default")
      (node (ref "U$1") (pin "3") (pinfunction "GPIO1_6_3") (pintype "passive"))
      (node (ref "U$4") (pin "23") (pinfunction "23_23") (pintype "passive"))
    )
    (net (code "141") (name "Net-(U$1-GPIO1_7)") (class "Default")
      (node (ref "U$1") (pin "4") (pinfunction "GPIO1_7_4") (pintype "passive"))
      (node (ref "U$3") (pin "23") (pinfunction "23_23") (pintype "passive"))
    )
    (net (code "142") (name "Net-(U$1-GPIO1_12)") (class "Default")
      (node (ref "U$1") (pin "12") (pinfunction "GPIO1_12_12") (pintype "passive"))
      (node (ref "U$3") (pin "19") (pinfunction "19_19") (pintype "passive"))
    )
    (net (code "143") (name "Net-(U$1-GPIO1_13)") (class "Default")
      (node (ref "U$1") (pin "11") (pinfunction "GPIO1_13_11") (pintype "passive"))
      (node (ref "U$4") (pin "19") (pinfunction "19_19") (pintype "passive"))
    )
    (net (code "144") (name "Net-(U$1-GPIO1_14)") (class "Default")
      (node (ref "U$1") (pin "16") (pinfunction "GPIO1_14_16") (pintype "passive"))
      (node (ref "U$3") (pin "17") (pinfunction "17_17") (pintype "passive"))
    )
    (net (code "145") (name "Net-(U$1-GPIO1_15)") (class "Default")
      (node (ref "U$1") (pin "15") (pinfunction "GPIO1_15_15") (pintype "passive"))
      (node (ref "U$4") (pin "17") (pinfunction "17_17") (pintype "passive"))
    )
    (net (code "146") (name "Net-(U$1-GPIO1_16)") (class "Default")
      (node (ref "U$1") (pin "61") (pinfunction "GPIO1_16_61") (pintype "passive"))
      (node (ref "U$5") (pin "18") (pinfunction "18_18") (pintype "passive"))
    )
    (net (code "147") (name "Net-(U$1-GPIO1_17)") (class "Default")
      (node (ref "U$1") (pin "69") (pinfunction "GPIO1_17_69") (pintype "passive"))
      (node (ref "U$5") (pin "14") (pinfunction "14_14") (pintype "passive"))
    )
    (net (code "148") (name "Net-(U$1-GPIO1_28)") (class "Default")
      (node (ref "U$1") (pin "58") (pinfunction "GPIO1_28_58") (pintype "passive"))
      (node (ref "U$2") (pin "20") (pinfunction "20_20") (pintype "passive"))
    )
    (net (code "149") (name "Net-(U$1-GPIO1_29)") (class "Default")
      (node (ref "U$1") (pin "26") (pinfunction "GPIO1_29_26") (pintype "passive"))
      (node (ref "U$3") (pin "12") (pinfunction "12_12") (pintype "passive"))
    )
    (net (code "150") (name "Net-(U$1-GPIO1_30)") (class "Default")
      (node (ref "U$1") (pin "21") (pinfunction "GPIO1_30_21") (pintype "passive"))
      (node (ref "U$4") (pin "14") (pinfunction "14_14") (pintype "passive"))
    )
    (net (code "151") (name "Net-(U$1-GPIO1_31)") (class "Default")
      (node (ref "U$1") (pin "20") (pinfunction "GPIO1_31_20") (pintype "passive"))
      (node (ref "U$3") (pin "15") (pinfunction "15_15") (pintype "passive"))
    )
    (net (code "152") (name "Net-(U$1-GPIO2_1)") (class "Default")
      (node (ref "U$1") (pin "18") (pinfunction "GPIO2_1_18") (pintype "passive"))
      (node (ref "U$3") (pin "16") (pinfunction "16_16") (pintype "passive"))
    )
    (net (code "153") (name "Net-(U$1-GPIO2_6)") (class "Default")
      (node (ref "U$1") (pin "45") (pinfunction "GPIO2_6_45") (pintype "passive"))
      (node (ref "U$4") (pin "2") (pinfunction "2_2") (pintype "passive"))
    )
    (net (code "154") (name "Net-(U$1-GPIO2_7)") (class "Default")
      (node (ref "U$1") (pin "46") (pinfunction "GPIO2_7_46") (pintype "passive"))
      (node (ref "U$3") (pin "2") (pinfunction "2_2") (pintype "passive"))
    )
    (net (code "155") (name "Net-(U$1-GPIO2_8)") (class "Default")
      (node (ref "U$1") (pin "43") (pinfunction "GPIO2_8_43") (pintype "passive"))
      (node (ref "U$4") (pin "3") (pinfunction "3_3") (pintype "passive"))
    )
    (net (code "156") (name "Net-(U$1-GPIO2_9)") (class "Default")
      (node (ref "U$1") (pin "44") (pinfunction "GPIO2_9_44") (pintype "passive"))
      (node (ref "U$3") (pin "3") (pinfunction "3_3") (pintype "passive"))
    )
    (net (code "157") (name "Net-(U$1-GPIO2_10)") (class "Default")
      (node (ref "U$1") (pin "41") (pinfunction "GPIO2_10_41") (pintype "passive"))
      (node (ref "U$4") (pin "4") (pinfunction "4_4") (pintype "passive"))
    )
    (net (code "158") (name "Net-(U$1-GPIO2_11)") (class "Default")
      (node (ref "U$1") (pin "42") (pinfunction "GPIO2_11_42") (pintype "passive"))
      (node (ref "U$3") (pin "4") (pinfunction "4_4") (pintype "passive"))
    )
    (net (code "159") (name "Net-(U$1-GPIO2_12)") (class "Default")
      (node (ref "U$1") (pin "39") (pinfunction "GPIO2_12_39") (pintype "passive"))
      (node (ref "U$4") (pin "5") (pinfunction "5_5") (pintype "passive"))
    )
    (net (code "160") (name "Net-(U$1-GPIO2_13)") (class "Default")
      (node (ref "U$1") (pin "40") (pinfunction "GPIO2_13_40") (pintype "passive"))
      (node (ref "U$3") (pin "5") (pinfunction "5_5") (pintype "passive"))
    )
    (net (code "161") (name "Net-(U$1-GPIO2_22)") (class "Default")
      (node (ref "U$1") (pin "27") (pinfunction "GPIO2_22_27") (pintype "passive"))
      (node (ref "U$4") (pin "11") (pinfunction "11_11") (pintype "passive"))
    )
    (net (code "162") (name "Net-(U$1-GPIO2_23)") (class "Default")
      (node (ref "U$1") (pin "29") (pinfunction "GPIO2_23_29") (pintype "passive"))
      (node (ref "U$4") (pin "10") (pinfunction "10_10") (pintype "passive"))
    )
    (net (code "163") (name "Net-(U$1-GPIO2_24)") (class "Default")
      (node (ref "U$1") (pin "28") (pinfunction "GPIO2_24_28") (pintype "passive"))
      (node (ref "U$3") (pin "11") (pinfunction "11_11") (pintype "passive"))
    )
    (net (code "164") (name "Net-(U$1-GPIO2_25)") (class "Default")
      (node (ref "U$1") (pin "30") (pinfunction "GPIO2_25_30") (pintype "passive"))
      (node (ref "U$3") (pin "10") (pinfunction "10_10") (pintype "passive"))
    )
    (net (code "165") (name "Net-(U$1-GPIO3_19)") (class "Default")
      (node (ref "U$1") (pin "73") (pinfunction "GPIO3_19_73") (pintype "passive"))
      (node (ref "U$5") (pin "12") (pinfunction "12_12") (pintype "passive"))
    )
    (net (code "166") (name "Net-(U$1-GPIO3_21)") (class "Default")
      (node (ref "U$1") (pin "71") (pinfunction "GPIO3_21_71") (pintype "passive"))
      (node (ref "U$5") (pin "13") (pinfunction "13_13") (pintype "passive"))
    )
    (net (code "167") (name "Net-(U$1-I2C1_SCL)") (class "Default")
      (node (ref "U$1") (pin "63") (pinfunction "I2C1_SCL_63") (pintype "passive"))
      (node (ref "U$5") (pin "17") (pinfunction "17_17") (pintype "passive"))
    )
    (net (code "168") (name "Net-(U$1-I2C1_SDA)") (class "Default")
      (node (ref "U$1") (pin "64") (pinfunction "I2C1_SDA_64") (pintype "passive"))
      (node (ref "U$2") (pin "17") (pinfunction "17_17") (pintype "passive"))
    )
    (net (code "169") (name "Net-(U$1-I2C2_SCL)") (class "Default")
      (node (ref "U$1") (pin "65") (pinfunction "I2C2_SCL_65") (pintype "passive"))
      (node (ref "U$5") (pin "16") (pinfunction "16_16") (pintype "passive"))
    )
    (net (code "170") (name "Net-(U$1-I2C2_SDA)") (class "Default")
      (node (ref "U$1") (pin "66") (pinfunction "I2C2_SDA_66") (pintype "passive"))
      (node (ref "U$2") (pin "16") (pinfunction "16_16") (pintype "passive"))
    )
    (net (code "171") (name "Net-(U$1-PWR_BUT)") (class "Default")
      (node (ref "U$1") (pin "55") (pinfunction "PWR_BUT_55") (pintype "passive"))
      (node (ref "U$5") (pin "21") (pinfunction "21_21") (pintype "passive"))
    )
    (net (code "172") (name "Net-(U$1-SPI1_CS0)") (class "Default")
      (node (ref "U$1") (pin "74") (pinfunction "SPI1_CS0_74") (pintype "passive"))
      (node (ref "U$2") (pin "12") (pinfunction "12_12") (pintype "passive"))
    )
    (net (code "173") (name "Net-(U$1-SPI1_DI)") (class "Default")
      (node (ref "U$1") (pin "76") (pinfunction "SPI1_DI_76") (pintype "passive"))
      (node (ref "U$2") (pin "11") (pinfunction "11_11") (pintype "passive"))
    )
    (net (code "174") (name "Net-(U$1-SPI1_DO)") (class "Default")
      (node (ref "U$1") (pin "75") (pinfunction "SPI1_DO_75") (pintype "passive"))
      (node (ref "U$5") (pin "11") (pinfunction "11_11") (pintype "passive"))
    )
    (net (code "175") (name "Net-(U$1-SPI1_SCLK)") (class "Default")
      (node (ref "U$1") (pin "77") (pinfunction "SPI1_SCLK_77") (pintype "passive"))
      (node (ref "U$5") (pin "10") (pinfunction "10_10") (pintype "passive"))
    )
    (net (code "176") (name "Net-(U$1-SYS_5V-Pad54)") (class "Default")
      (node (ref "U$1") (pin "54") (pinfunction "SYS_5V_54") (pintype "passive"))
      (node (ref "U$2") (pin "22") (pinfunction "22_22") (pintype "passive"))
    )
    (net (code "177") (name "Net-(U$1-SYS_RESETN)") (class "Default")
      (node (ref "U$1") (pin "56") (pinfunction "SYS_RESETN_56") (pintype "passive"))
      (node (ref "U$2") (pin "21") (pinfunction "21_21") (pintype "passive"))
    )
    (net (code "178") (name "Net-(U$1-TIMER4)") (class "Default")
      (node (ref "U$1") (pin "7") (pinfunction "TIMER4_7") (pintype "passive"))
      (node (ref "U$4") (pin "21") (pinfunction "21_21") (pintype "passive"))
    )
    (net (code "179") (name "Net-(U$1-TIMER5)") (class "Default")
      (node (ref "U$1") (pin "9") (pinfunction "TIMER5_9") (pintype "passive"))
      (node (ref "U$4") (pin "20") (pinfunction "20_20") (pintype "passive"))
    )
    (net (code "180") (name "Net-(U$1-TIMER6)") (class "Default")
      (node (ref "U$1") (pin "10") (pinfunction "TIMER6_10") (pintype "passive"))
      (node (ref "U$3") (pin "20") (pinfunction "20_20") (pintype "passive"))
    )
    (net (code "181") (name "Net-(U$1-TIMER7)") (class "Default")
      (node (ref "U$1") (pin "8") (pinfunction "TIMER7_8") (pintype "passive"))
      (node (ref "U$3") (pin "21") (pinfunction "21_21") (pintype "passive"))
    )
    (net (code "182") (name "Net-(U$1-UART3_CTSN)") (class "Default")
      (node (ref "U$1") (pin "36") (pinfunction "UART3_CTSN_36") (pintype "passive"))
      (node (ref "U$3") (pin "7") (pinfunction "7_7") (pintype "passive"))
    )
    (net (code "183") (name "Net-(U$1-UART3_RTSN)") (class "Default")
      (node (ref "U$1") (pin "34") (pinfunction "UART3_RTSN_34") (pintype "passive"))
      (node (ref "U$3") (pin "8") (pinfunction "8_8") (pintype "passive"))
    )
    (net (code "184") (name "Net-(U$1-UART4_CTSN)") (class "Default")
      (node (ref "U$1") (pin "35") (pinfunction "UART4_CTSN_35") (pintype "passive"))
      (node (ref "U$4") (pin "7") (pinfunction "7_7") (pintype "passive"))
    )
    (net (code "185") (name "Net-(U$1-UART4_RTSN)") (class "Default")
      (node (ref "U$1") (pin "33") (pinfunction "UART4_RTSN_33") (pintype "passive"))
      (node (ref "U$4") (pin "8") (pinfunction "8_8") (pintype "passive"))
    )
    (net (code "186") (name "Net-(U$1-UART5_CTSN)") (class "Default")
      (node (ref "U$1") (pin "31") (pinfunction "UART5_CTSN_31") (pintype "passive"))
      (node (ref "U$4") (pin "9") (pinfunction "9_9") (pintype "passive"))
    )
    (net (code "187") (name "Net-(U$1-UART5_RTSN)") (class "Default")
      (node (ref "U$1") (pin "32") (pinfunction "UART5_RTSN_32") (pintype "passive"))
      (node (ref "U$3") (pin "9") (pinfunction "9_9") (pintype "passive"))
    )
    (net (code "188") (name "Net-(U$1-UART5_RXD)") (class "Default")
      (node (ref "U$1") (pin "38") (pinfunction "UART5_RXD_38") (pintype "passive"))
      (node (ref "U$3") (pin "6") (pinfunction "6_6") (pintype "passive"))
    )
    (net (code "189") (name "Net-(U$1-UART5_TXD)") (class "Default")
      (node (ref "U$1") (pin "37") (pinfunction "UART5_TXD_37") (pintype "passive"))
      (node (ref "U$4") (pin "6") (pinfunction "6_6") (pintype "passive"))
    )
    (net (code "190") (name "Net-(U$1-VDD_3V3EXP-Pad49)") (class "Default")
      (node (ref "U$1") (pin "49") (pinfunction "VDD_3V3EXP_49") (pintype "power_in"))
      (node (ref "U$5") (pin "24") (pinfunction "24_24") (pintype "passive"))
    )
    (net (code "191") (name "Net-(U$1-VDD_3V3EXP-Pad50)") (class "Default")
      (node (ref "U$1") (pin "50") (pinfunction "VDD_3V3EXP_50") (pintype "power_in"))
      (node (ref "U$2") (pin "24") (pinfunction "24_24") (pintype "passive"))
    )
    (net (code "192") (name "Net-(U$1-VDD_ADC)") (class "Default")
      (node (ref "U$1") (pin "78") (pinfunction "VDD_ADC_78") (pintype "passive"))
      (node (ref "U$2") (pin "10") (pinfunction "10_10") (pintype "passive"))
    )
    (net (code "193") (name "Net-(U1-IN1)") (class "Default")
      (node (ref "R4") (pin "2") (pinfunction "2_2") (pintype "passive"))
      (node (ref "U1") (pin "3") (pinfunction "IN1_3") (pintype "bidirectional"))
    )
    (net (code "194") (name "Net-(U2-1(TX0))") (class "Default")
      (node (ref "JP10") (pin "7") (pinfunction "7_7") (pintype "passive"))
      (node (ref "R2") (pin "2") (pinfunction "2_2") (pintype "passive"))
      (node (ref "U2") (pin "1") (pinfunction "1(TX0)_1") (pintype "bidirectional"))
    )
    (net (code "195") (name "Net-(U2-14(TX3))") (class "Default")
      (node (ref "JP13") (pin "8") (pinfunction "8_8") (pintype "passive"))
      (node (ref "U2") (pin "14") (pinfunction "14(TX3)_14") (pintype "bidirectional"))
    )
    (net (code "196") (name "Net-(U2-15(RX3))") (class "Default")
      (node (ref "JP13") (pin "7") (pinfunction "7_7") (pintype "passive"))
      (node (ref "U2") (pin "15") (pinfunction "15(RX3)_15") (pintype "bidirectional"))
    )
    (net (code "197") (name "Net-(U2-16(TX2))") (class "Default")
      (node (ref "JP13") (pin "6") (pinfunction "6_6") (pintype "passive"))
      (node (ref "U2") (pin "16") (pinfunction "16(TX2)_16") (pintype "bidirectional"))
    )
    (net (code "198") (name "Net-(U2-17(RX2))") (class "Default")
      (node (ref "JP13") (pin "5") (pinfunction "5_5") (pintype "passive"))
      (node (ref "U2") (pin "17") (pinfunction "17(RX2)_17") (pintype "bidirectional"))
    )
    (net (code "199") (name "Net-(U2-18(TX1))") (class "Default")
      (node (ref "JP13") (pin "4") (pinfunction "4_4") (pintype "passive"))
      (node (ref "R1") (pin "1") (pinfunction "1_1") (pintype "passive"))
      (node (ref "U2") (pin "18") (pinfunction "18(TX1)_18") (pintype "bidirectional"))
    )
    (net (code "200") (name "Net-(U3-IN1)") (class "Default")
      (node (ref "R6") (pin "2") (pinfunction "2_2") (pintype "passive"))
      (node (ref "U3") (pin "3") (pinfunction "IN1_3") (pintype "bidirectional"))
    )
    (net (code "201") (name "Net-(U4-IN1)") (class "Default")
      (node (ref "R11") (pin "2") (pinfunction "2_2") (pintype "passive"))
      (node (ref "U4") (pin "3") (pinfunction "IN1_3") (pintype "bidirectional"))
    )
    (net (code "202") (name "Net-(U5-IN1)") (class "Default")
      (node (ref "R14") (pin "2") (pinfunction "2_2") (pintype "passive"))
      (node (ref "U5") (pin "3") (pinfunction "IN1_3") (pintype "bidirectional"))
    )
    (net (code "203") (name "Net-(U6-FILT)") (class "Default")
      (node (ref "C1") (pin "2") (pinfunction "2_2") (pintype "passive"))
      (node (ref "U6") (pin "6") (pinfunction "FILT_6") (pintype "bidirectional"))
    )
    (net (code "204") (name "Net-(U7-FILT)") (class "Default")
      (node (ref "C2") (pin "2") (pinfunction "2_2") (pintype "passive"))
      (node (ref "U7") (pin "6") (pinfunction "FILT_6") (pintype "bidirectional"))
    )
    (net (code "205") (name "Net-(U8-FILT)") (class "Default")
      (node (ref "C3") (pin "2") (pinfunction "2_2") (pintype "passive"))
      (node (ref "U8") (pin "6") (pinfunction "FILT_6") (pintype "bidirectional"))
    )
    (net (code "206") (name "Net-(U9-FILT)") (class "Default")
      (node (ref "C4") (pin "2") (pinfunction "2_2") (pintype "passive"))
      (node (ref "U9") (pin "6") (pinfunction "FILT_6") (pintype "bidirectional"))
    )
    (net (code "207") (name "Net-(U10-FILT)") (class "Default")
      (node (ref "C9") (pin "2") (pinfunction "2_2") (pintype "passive"))
      (node (ref "U10") (pin "6") (pinfunction "FILT_6") (pintype "bidirectional"))
    )
    (net (code "208") (name "Net-(U11-FILT)") (class "Default")
      (node (ref "C10") (pin "2") (pinfunction "2_2") (pintype "passive"))
      (node (ref "U11") (pin "6") (pinfunction "FILT_6") (pintype "bidirectional"))
    )
    (net (code "209") (name "Net-(U12-FILT)") (class "Default")
      (node (ref "C11") (pin "2") (pinfunction "2_2") (pintype "passive"))
      (node (ref "U12") (pin "6") (pinfunction "FILT_6") (pintype "bidirectional"))
    )
    (net (code "210") (name "Net-(U13-FILT)") (class "Default")
      (node (ref "C12") (pin "2") (pinfunction "2_2") (pintype "passive"))
      (node (ref "U13") (pin "6") (pinfunction "FILT_6") (pintype "bidirectional"))
    )
    (net (code "211") (name "Net-(U14-BOOT)") (class "Default")
      (node (ref "C21") (pin "2") (pinfunction "2_2") (pintype "passive"))
      (node (ref "U14") (pin "1") (pinfunction "BOOT_1") (pintype "bidirectional"))
    )
    (net (code "212") (name "Net-(U14-COMP)") (class "Default")
      (node (ref "C22") (pin "1") (pinfunction "1_1") (pintype "passive"))
      (node (ref "C23") (pin "1") (pinfunction "1_1") (pintype "passive"))
      (node (ref "U14") (pin "6") (pinfunction "COMP_6") (pintype "bidirectional"))
    )
    (net (code "213") (name "Net-(U14-PH)") (class "Default")
      (node (ref "C21") (pin "1") (pinfunction "1_1") (pintype "passive"))
      (node (ref "D35") (pin "C") (pinfunction "C_C") (pintype "passive"))
      (node (ref "L1") (pin "1") (pinfunction "1_1") (pintype "passive"))
      (node (ref "U14") (pin "8") (pinfunction "PH_8") (pintype "bidirectional"))
    )
    (net (code "214") (name "Net-(U14-SS)") (class "Default")
      (node (ref "C20") (pin "1") (pinfunction "1_1") (pintype "passive"))
      (node (ref "U14") (pin "4") (pinfunction "SS_4") (pintype "bidirectional"))
    )
    (net (code "215") (name "Net-(U14-VSENSE)") (class "Default")
      (node (ref "R22") (pin "1") (pinfunction "1_1") (pintype "passive"))
      (node (ref "R23") (pin "2") (pinfunction "2_2") (pintype "passive"))
      (node (ref "U14") (pin "5") (pinfunction "VSENSE_5") (pintype "bidirectional"))
    )
    (net (code "216") (name "Net-(U15-BOOT)") (class "Default")
      (node (ref "C32") (pin "2") (pinfunction "2_2") (pintype "passive"))
      (node (ref "U15") (pin "1") (pinfunction "BOOT_1") (pintype "bidirectional"))
    )
    (net (code "217") (name "Net-(U15-COMP)") (class "Default")
      (node (ref "C33") (pin "1") (pinfunction "1_1") (pintype "passive"))
      (node (ref "C34") (pin "1") (pinfunction "1_1") (pintype "passive"))
      (node (ref "U15") (pin "6") (pinfunction "COMP_6") (pintype "bidirectional"))
    )
    (net (code "218") (name "Net-(U15-PH)") (class "Default")
      (node (ref "C32") (pin "1") (pinfunction "1_1") (pintype "passive"))
      (node (ref "D36") (pin "C") (pinfunction "C_C") (pintype "passive"))
      (node (ref "L2") (pin "1") (pinfunction "1_1") (pintype "passive"))
      (node (ref "U15") (pin "8") (pinfunction "PH_8") (pintype "bidirectional"))
    )
    (net (code "219") (name "Net-(U15-SS)") (class "Default")
      (node (ref "C31") (pin "1") (pinfunction "1_1") (pintype "passive"))
      (node (ref "U15") (pin "4") (pinfunction "SS_4") (pintype "bidirectional"))
    )
    (net (code "220") (name "Net-(U15-VSENSE)") (class "Default")
      (node (ref "R27") (pin "1") (pinfunction "1_1") (pintype "passive"))
      (node (ref "R28") (pin "2") (pinfunction "2_2") (pintype "passive"))
      (node (ref "U15") (pin "5") (pinfunction "VSENSE_5") (pintype "bidirectional"))
    )
    (net (code "221") (name "RELAY1") (class "Default")
      (node (ref "JP15") (pin "1") (pinfunction "1_1") (pintype "passive"))
      (node (ref "R4") (pin "1") (pinfunction "1_1") (pintype "passive"))
      (node (ref "U2") (pin "52") (pinfunction "52_52") (pintype "bidirectional"))
    )
    (net (code "222") (name "RELAY1FB") (class "Default")
      (node (ref "JP16") (pin "1") (pinfunction "1_1") (pintype "passive"))
      (node (ref "R4") (pin "3") (pinfunction "1_3") (pintype "passive"))
      (node (ref "U2") (pin "53") (pinfunction "53_53") (pintype "bidirectional"))
    )
    (net (code "223") (name "RELAY2") (class "Default")
      (node (ref "JP16") (pin "2") (pinfunction "2_2") (pintype "passive"))
      (node (ref "R5") (pin "3") (pinfunction "1_3") (pintype "passive"))
      (node (ref "U2") (pin "51") (pinfunction "51_51") (pintype "bidirectional"))
    )
    (net (code "224") (name "RELAY2FB") (class "Default")
      (node (ref "JP15") (pin "2") (pinfunction "2_2") (pintype "passive"))
      (node (ref "R5") (pin "1") (pinfunction "1_1") (pintype "passive"))
      (node (ref "U2") (pin "50") (pinfunction "50_50") (pintype "bidirectional"))
    )
    (net (code "225") (name "RELAY3") (class "Default")
      (node (ref "JP15") (pin "3") (pinfunction "3_3") (pintype "passive"))
      (node (ref "R5") (pin "5") (pinfunction "1_5") (pintype "passive"))
      (node (ref "U2") (pin "48") (pinfunction "48_48") (pintype "bidirectional"))
    )
    (net (code "226") (name "RELAY3FB") (class "Default")
      (node (ref "JP16") (pin "3") (pinfunction "3_3") (pintype "passive"))
      (node (ref "R5") (pin "7") (pinfunction "1_7") (pintype "passive"))
      (node (ref "U2") (pin "49") (pinfunction "49_49") (pintype "bidirectional"))
    )
    (net (code "227") (name "RELAY4") (class "Default")
      (node (ref "JP16") (pin "4") (pinfunction "4_4") (pintype "passive"))
      (node (ref "R3") (pin "7") (pinfunction "1_7") (pintype "passive"))
      (node (ref "U2") (pin "47") (pinfunction "47_47") (pintype "bidirectional"))
    )
    (net (code "228") (name "RELAY4FB") (class "Default")
      (node (ref "JP15") (pin "4") (pinfunction "4_4") (pintype "passive"))
      (node (ref "R3") (pin "5") (pinfunction "1_5") (pintype "passive"))
      (node (ref "U2") (pin "46") (pinfunction "46_46") (pintype "bidirectional"))
    )
    (net (code "229") (name "RELAY5") (class "Default")
      (node (ref "JP15") (pin "5") (pinfunction "5_5") (pintype "passive"))
      (node (ref "R6") (pin "1") (pinfunction "1_1") (pintype "passive"))
      (node (ref "U2") (pin "44") (pinfunction "44_44") (pintype "bidirectional"))
    )
    (net (code "230") (name "RELAY5FB") (class "Default")
      (node (ref "JP16") (pin "5") (pinfunction "5_5") (pintype "passive"))
      (node (ref "R6") (pin "3") (pinfunction "1_3") (pintype "passive"))
      (node (ref "U2") (pin "45") (pinfunction "45_45") (pintype "bidirectional"))
    )
    (net (code "231") (name "RELAY6") (class "Default")
      (node (ref "JP16") (pin "6") (pinfunction "6_6") (pintype "passive"))
      (node (ref "R7") (pin "3") (pinfunction "1_3") (pintype "passive"))
      (node (ref "U2") (pin "43") (pinfunction "43_43") (pintype "bidirectional"))
    )
    (net (code "232") (name "RELAY6FB") (class "Default")
      (node (ref "JP15") (pin "6") (pinfunction "6_6") (pintype "passive"))
      (node (ref "R6") (pin "7") (pinfunction "1_7") (pintype "passive"))
      (node (ref "U2") (pin "42") (pinfunction "42_42") (pintype "bidirectional"))
    )
    (net (code "233") (name "RELAY7") (class "Default")
      (node (ref "JP15") (pin "7") (pinfunction "7_7") (pintype "passive"))
      (node (ref "R7") (pin "5") (pinfunction "1_5") (pintype "passive"))
      (node (ref "U2") (pin "40") (pinfunction "40_40") (pintype "bidirectional"))
    )
    (net (code "234") (name "RELAY7FB") (class "Default")
      (node (ref "JP16") (pin "7") (pinfunction "7_7") (pintype "passive"))
      (node (ref "R7") (pin "7") (pinfunction "1_7") (pintype "passive"))
      (node (ref "U2") (pin "41") (pinfunction "41_41") (pintype "bidirectional"))
    )
    (net (code "235") (name "RELAY8") (class "Default")
      (node (ref "JP16") (pin "8") (pinfunction "8_8") (pintype "passive"))
      (node (ref "R8") (pin "7") (pinfunction "1_7") (pintype "passive"))
      (node (ref "U2") (pin "39") (pinfunction "39_39") (pintype "bidirectional"))
    )
    (net (code "236") (name "RELAY8FB") (class "Default")
      (node (ref "JP15") (pin "8") (pinfunction "8_8") (pintype "passive"))
      (node (ref "R8") (pin "5") (pinfunction "1_5") (pintype "passive"))
      (node (ref "U2") (pin "38") (pinfunction "38_38") (pintype "bidirectional"))
    )
    (net (code "237") (name "RX0") (class "Default")
      (node (ref "JP10") (pin "8") (pinfunction "8_8") (pintype "passive"))
      (node (ref "U$1") (pin "70") (pinfunction "UART1_TXD_70") (pintype "passive"))
      (node (ref "U$2") (pin "14") (pinfunction "14_14") (pintype "passive"))
      (node (ref "U2") (pin "0") (pinfunction "0(RX0)_0") (pintype "bidirectional"))
    )
    (net (code "238") (name "RX1") (class "Default")
      (node (ref "JP13") (pin "3") (pinfunction "3_3") (pintype "passive"))
      (node (ref "U$1") (pin "67") (pinfunction "UART2_TXD_67") (pintype "passive"))
      (node (ref "U$5") (pin "15") (pinfunction "15_15") (pintype "passive"))
      (node (ref "U2") (pin "19") (pinfunction "19(RX1)_19") (pintype "bidirectional"))
    )
    (net (code "239") (name "SCL") (class "Default")
      (node (ref "HTU21D") (pin "SCL") (pinfunction "4_SCL") (pintype "passive"))
      (node (ref "IMU") (pin "SCL") (pinfunction "4_SCL") (pintype "passive"))
      (node (ref "JP13") (pin "1") (pinfunction "1_1") (pintype "passive"))
      (node (ref "R19") (pin "1") (pinfunction "1_1") (pintype "passive"))
      (node (ref "U2") (pin "21") (pinfunction "21(SCL)_21") (pintype "bidirectional"))
    )
    (net (code "240") (name "SDA") (class "Default")
      (node (ref "HTU21D") (pin "SDA") (pinfunction "3_SDA") (pintype "passive"))
      (node (ref "IMU") (pin "SDA") (pinfunction "5_SDA") (pintype "passive"))
      (node (ref "JP13") (pin "2") (pinfunction "2_2") (pintype "passive"))
      (node (ref "R20") (pin "1") (pinfunction "1_1") (pintype "passive"))
      (node (ref "U2") (pin "20") (pinfunction "20(SDA)_20") (pintype "bidirectional"))
    )
    (net (code "241") (name "SERVO_AUX1") (class "Default")
      (node (ref "JP10") (pin "4") (pinfunction "4_4") (pintype "passive"))
      (node (ref "SERVO_AUX1") (pin "3") (pinfunction "3_3") (pintype "passive"))
      (node (ref "U2") (pin "4") (pinfunction "4_4") (pintype "bidirectional"))
    )
    (net (code "242") (name "SERVO_AUX2") (class "Default")
      (node (ref "JP10") (pin "3") (pinfunction "3_3") (pintype "passive"))
      (node (ref "SERVO_AUX2") (pin "3") (pinfunction "3_3") (pintype "passive"))
      (node (ref "U2") (pin "5") (pinfunction "5_5") (pintype "bidirectional"))
    )
    (net (code "243") (name "SERVO_EN") (class "Default")
      (node (ref "JP10") (pin "6") (pinfunction "6_6") (pintype "passive"))
      (node (ref "U15") (pin "3") (pinfunction "EN_3") (pintype "bidirectional"))
      (node (ref "U2") (pin "2") (pinfunction "2_2") (pintype "bidirectional"))
    )
    (net (code "244") (name "STEERING") (class "Default")
      (node (ref "JP10") (pin "5") (pinfunction "5_5") (pintype "passive"))
      (node (ref "STEERING") (pin "3") (pinfunction "3_3") (pintype "passive"))
      (node (ref "U2") (pin "3") (pinfunction "3_3") (pintype "bidirectional"))
    )
    (net (code "245") (name "TX0") (class "Default")
      (node (ref "D2") (pin "C") (pinfunction "C_C") (pintype "passive"))
      (node (ref "R2") (pin "1") (pinfunction "1_1") (pintype "passive"))
      (node (ref "U$1") (pin "72") (pinfunction "UART1_RXD_72") (pintype "passive"))
      (node (ref "U$2") (pin "13") (pinfunction "13_13") (pintype "passive"))
    )
    (net (code "246") (name "TX1") (class "Default")
      (node (ref "D1") (pin "C") (pinfunction "C_C") (pintype "passive"))
      (node (ref "R1") (pin "2") (pinfunction "2_2") (pintype "passive"))
      (node (ref "U$1") (pin "68") (pinfunction "UART2_RXD_68") (pintype "passive"))
      (node (ref "U$2") (pin "15") (pinfunction "15_15") (pintype "passive"))
    )
    (net (code "247") (name "V2") (class "Default")
      (node (ref "I1/V2") (pin "3") (pinfunction "3_3") (pintype "passive"))
      (node (ref "JP11") (pin "7") (pinfunction "7_7") (pintype "passive"))
      (node (ref "U2") (pin "A1") (pinfunction "A1_A1") (pintype "bidirectional"))
    )
    (net (code "248") (name "V3") (class "Default")
      (node (ref "I2/V3") (pin "3") (pinfunction "3_3") (pintype "passive"))
      (node (ref "JP12") (pin "1") (pinfunction "1_1") (pintype "passive"))
      (node (ref "U2") (pin "A15") (pinfunction "A15_A15") (pintype "bidirectional"))
    )
    (net (code "249") (name "V4") (class "Default")
      (node (ref "I3/V4") (pin "3") (pinfunction "3_3") (pintype "passive"))
      (node (ref "JP12") (pin "2") (pinfunction "2_2") (pintype "passive"))
      (node (ref "U2") (pin "A14") (pinfunction "A14_A14") (pintype "bidirectional"))
    )
    (net (code "250") (name "unconnected-(GPSA-1-PadPPS)") (class "Default")
      (node (ref "GPS") (pin "PPS") (pinfunction "1_PPS") (pintype "passive"))
    )
    (net (code "251") (name "unconnected-(GPSA-4-PadVBAT)") (class "Default")
      (node (ref "GPS") (pin "VBAT") (pinfunction "4_VBAT") (pintype "passive"))
    )
    (net (code "252") (name "unconnected-(GPSA-7-PadFIX)") (class "Default")
      (node (ref "GPS") (pin "FIX") (pinfunction "7_FIX") (pintype "passive"))
    )
    (net (code "253") (name "unconnected-(GPSA-8-PadEN)") (class "Default")
      (node (ref "GPS") (pin "EN") (pinfunction "8_EN") (pintype "passive"))
    )
    (net (code "254") (name "unconnected-(GPSA-9-Pad3V3)") (class "Default")
      (node (ref "GPS") (pin "3V3") (pinfunction "9_3V3") (pintype "passive"))
    )
    (net (code "255") (name "unconnected-(I4-Pad3)") (class "Default")
      (node (ref "I4") (pin "3") (pinfunction "3_3") (pintype "passive"))
    )
    (net (code "256") (name "unconnected-(IMUA-2-Pad3VO)") (class "Default")
      (node (ref "IMU") (pin "3VO") (pinfunction "2_3VO") (pintype "passive"))
    )
    (net (code "257") (name "unconnected-(IMUA-6-PadGINT)") (class "Default")
      (node (ref "IMU") (pin "GINT") (pinfunction "6_GINT") (pintype "passive"))
    )
    (net (code "258") (name "unconnected-(IMUA-7-PadGRDY)") (class "Default")
      (node (ref "IMU") (pin "GRDY") (pinfunction "7_GRDY") (pintype "passive"))
    )
    (net (code "259") (name "unconnected-(IMUA-8-PadLIN1)") (class "Default")
      (node (ref "IMU") (pin "LIN1") (pinfunction "8_LIN1") (pintype "passive"))
    )
    (net (code "260") (name "unconnected-(IMUA-9-PadLIN2)") (class "Default")
      (node (ref "IMU") (pin "LIN2") (pinfunction "9_LIN2") (pintype "passive"))
    )
    (net (code "261") (name "unconnected-(IMUA-10-PadLRDY)") (class "Default")
      (node (ref "IMU") (pin "LRDY") (pinfunction "10_LRDY") (pintype "passive"))
    )
    (net (code "262") (name "unconnected-(JP14-Pad1)") (class "Default")
      (node (ref "JP14") (pin "1") (pinfunction "1_1") (pintype "passive"))
    )
    (net (code "263") (name "unconnected-(JP14-Pad2)") (class "Default")
      (node (ref "JP14") (pin "2") (pinfunction "2_2") (pintype "passive"))
    )
    (net (code "264") (name "unconnected-(JP17-Pad1)") (class "Default")
      (node (ref "JP17") (pin "1") (pinfunction "1_1") (pintype "passive"))
    )
    (net (code "265") (name "unconnected-(U$2-Pad2)") (class "Default")
      (node (ref "U$2") (pin "2") (pinfunction "2_2") (pintype "passive"))
    )
    (net (code "266") (name "unconnected-(U$3-Pad25)") (class "Default")
      (node (ref "U$3") (pin "25") (pinfunction "25_25") (pintype "passive"))
    )
    (net (code "267") (name "unconnected-(U$4-Pad25)") (class "Default")
      (node (ref "U$4") (pin "25") (pinfunction "25_25") (pintype "passive"))
    )
    (net (code "268") (name "unconnected-(U$5-Pad2)") (class "Default")
      (node (ref "U$5") (pin "2") (pinfunction "2_2") (pintype "passive"))
    )
    (net (code "269") (name "unconnected-(U2-PadAREF)") (class "Default")
      (node (ref "U2") (pin "AREF") (pinfunction "AREF_AREF") (pintype "bidirectional"))
    )
    (net (code "270") (name "unconnected-(U2-PadRESET)") (class "Default")
      (node (ref "U2") (pin "RESET") (pinfunction "RESET_RESET") (pintype "bidirectional"))
    )
    (net (code "271") (name "unconnected-(U14-EN-Pad3)") (class "Default")
      (node (ref "U14") (pin "3") (pinfunction "EN_3") (pintype "bidirectional"))
    )
  )
)
